# SCH_PSG4-v0_52_2026-07-15.net
KiCad netlist of a schematic drawn in EasyEDA
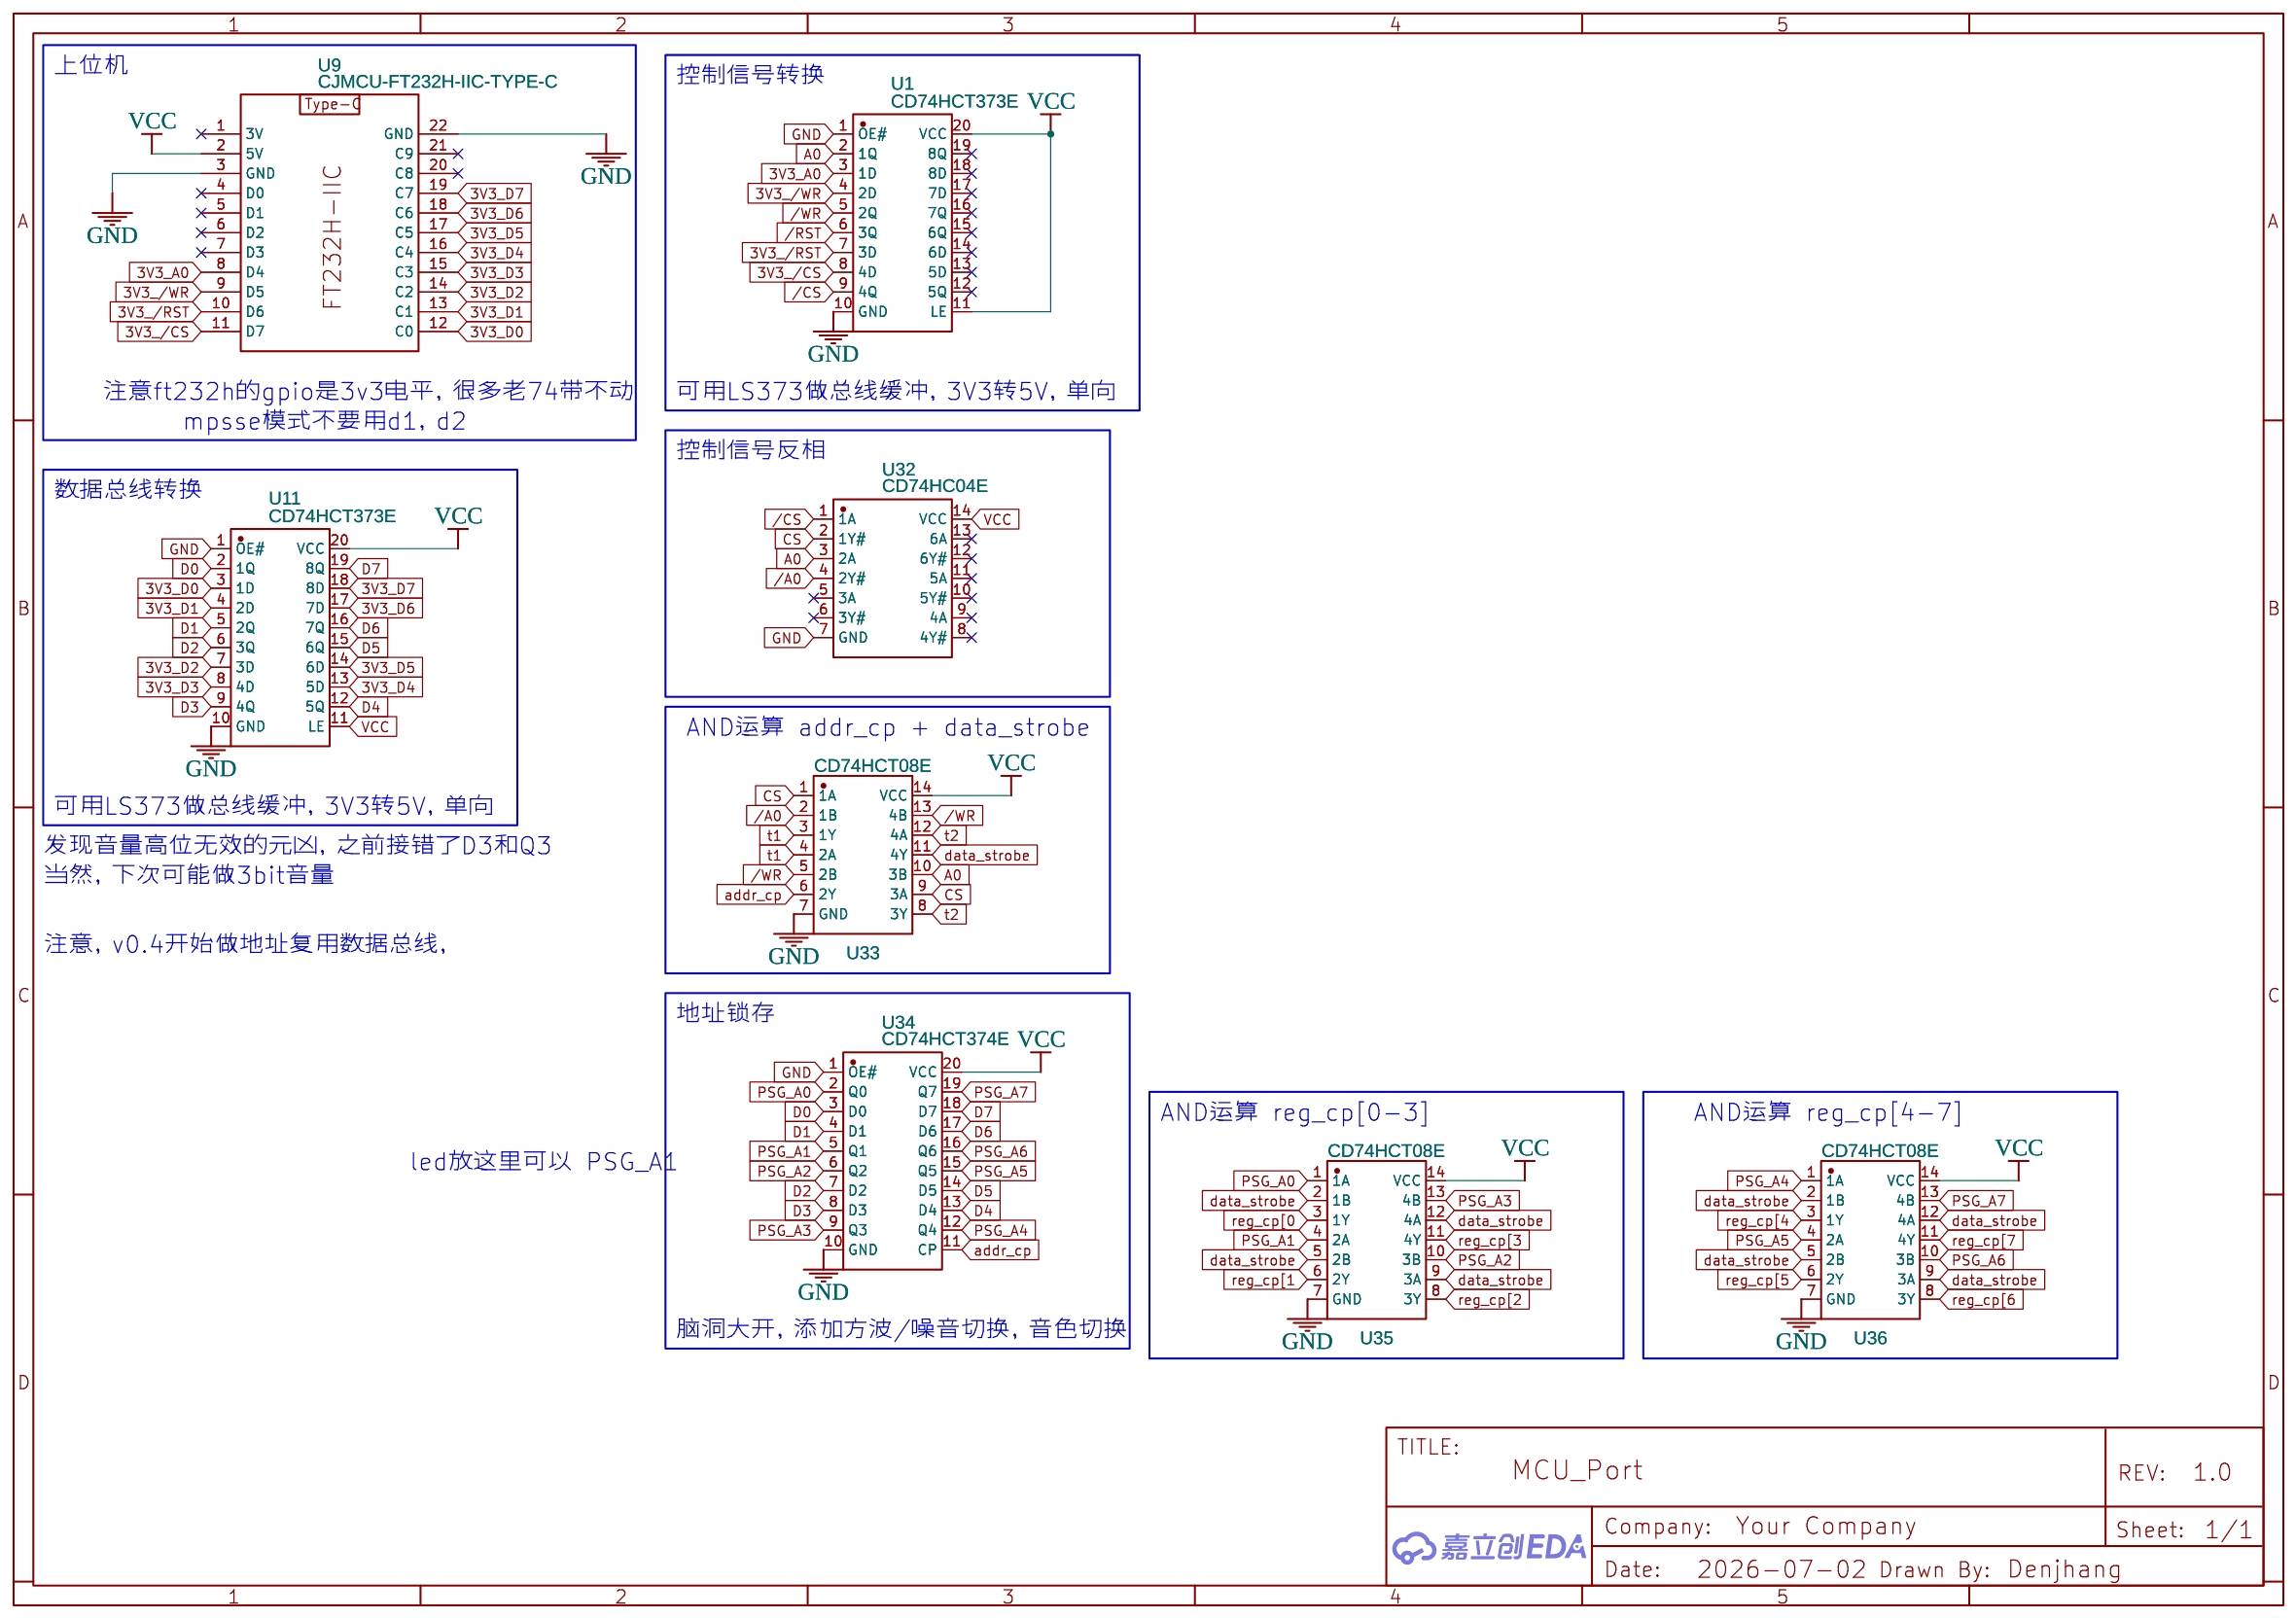
[diagram p0: MCU_Port]
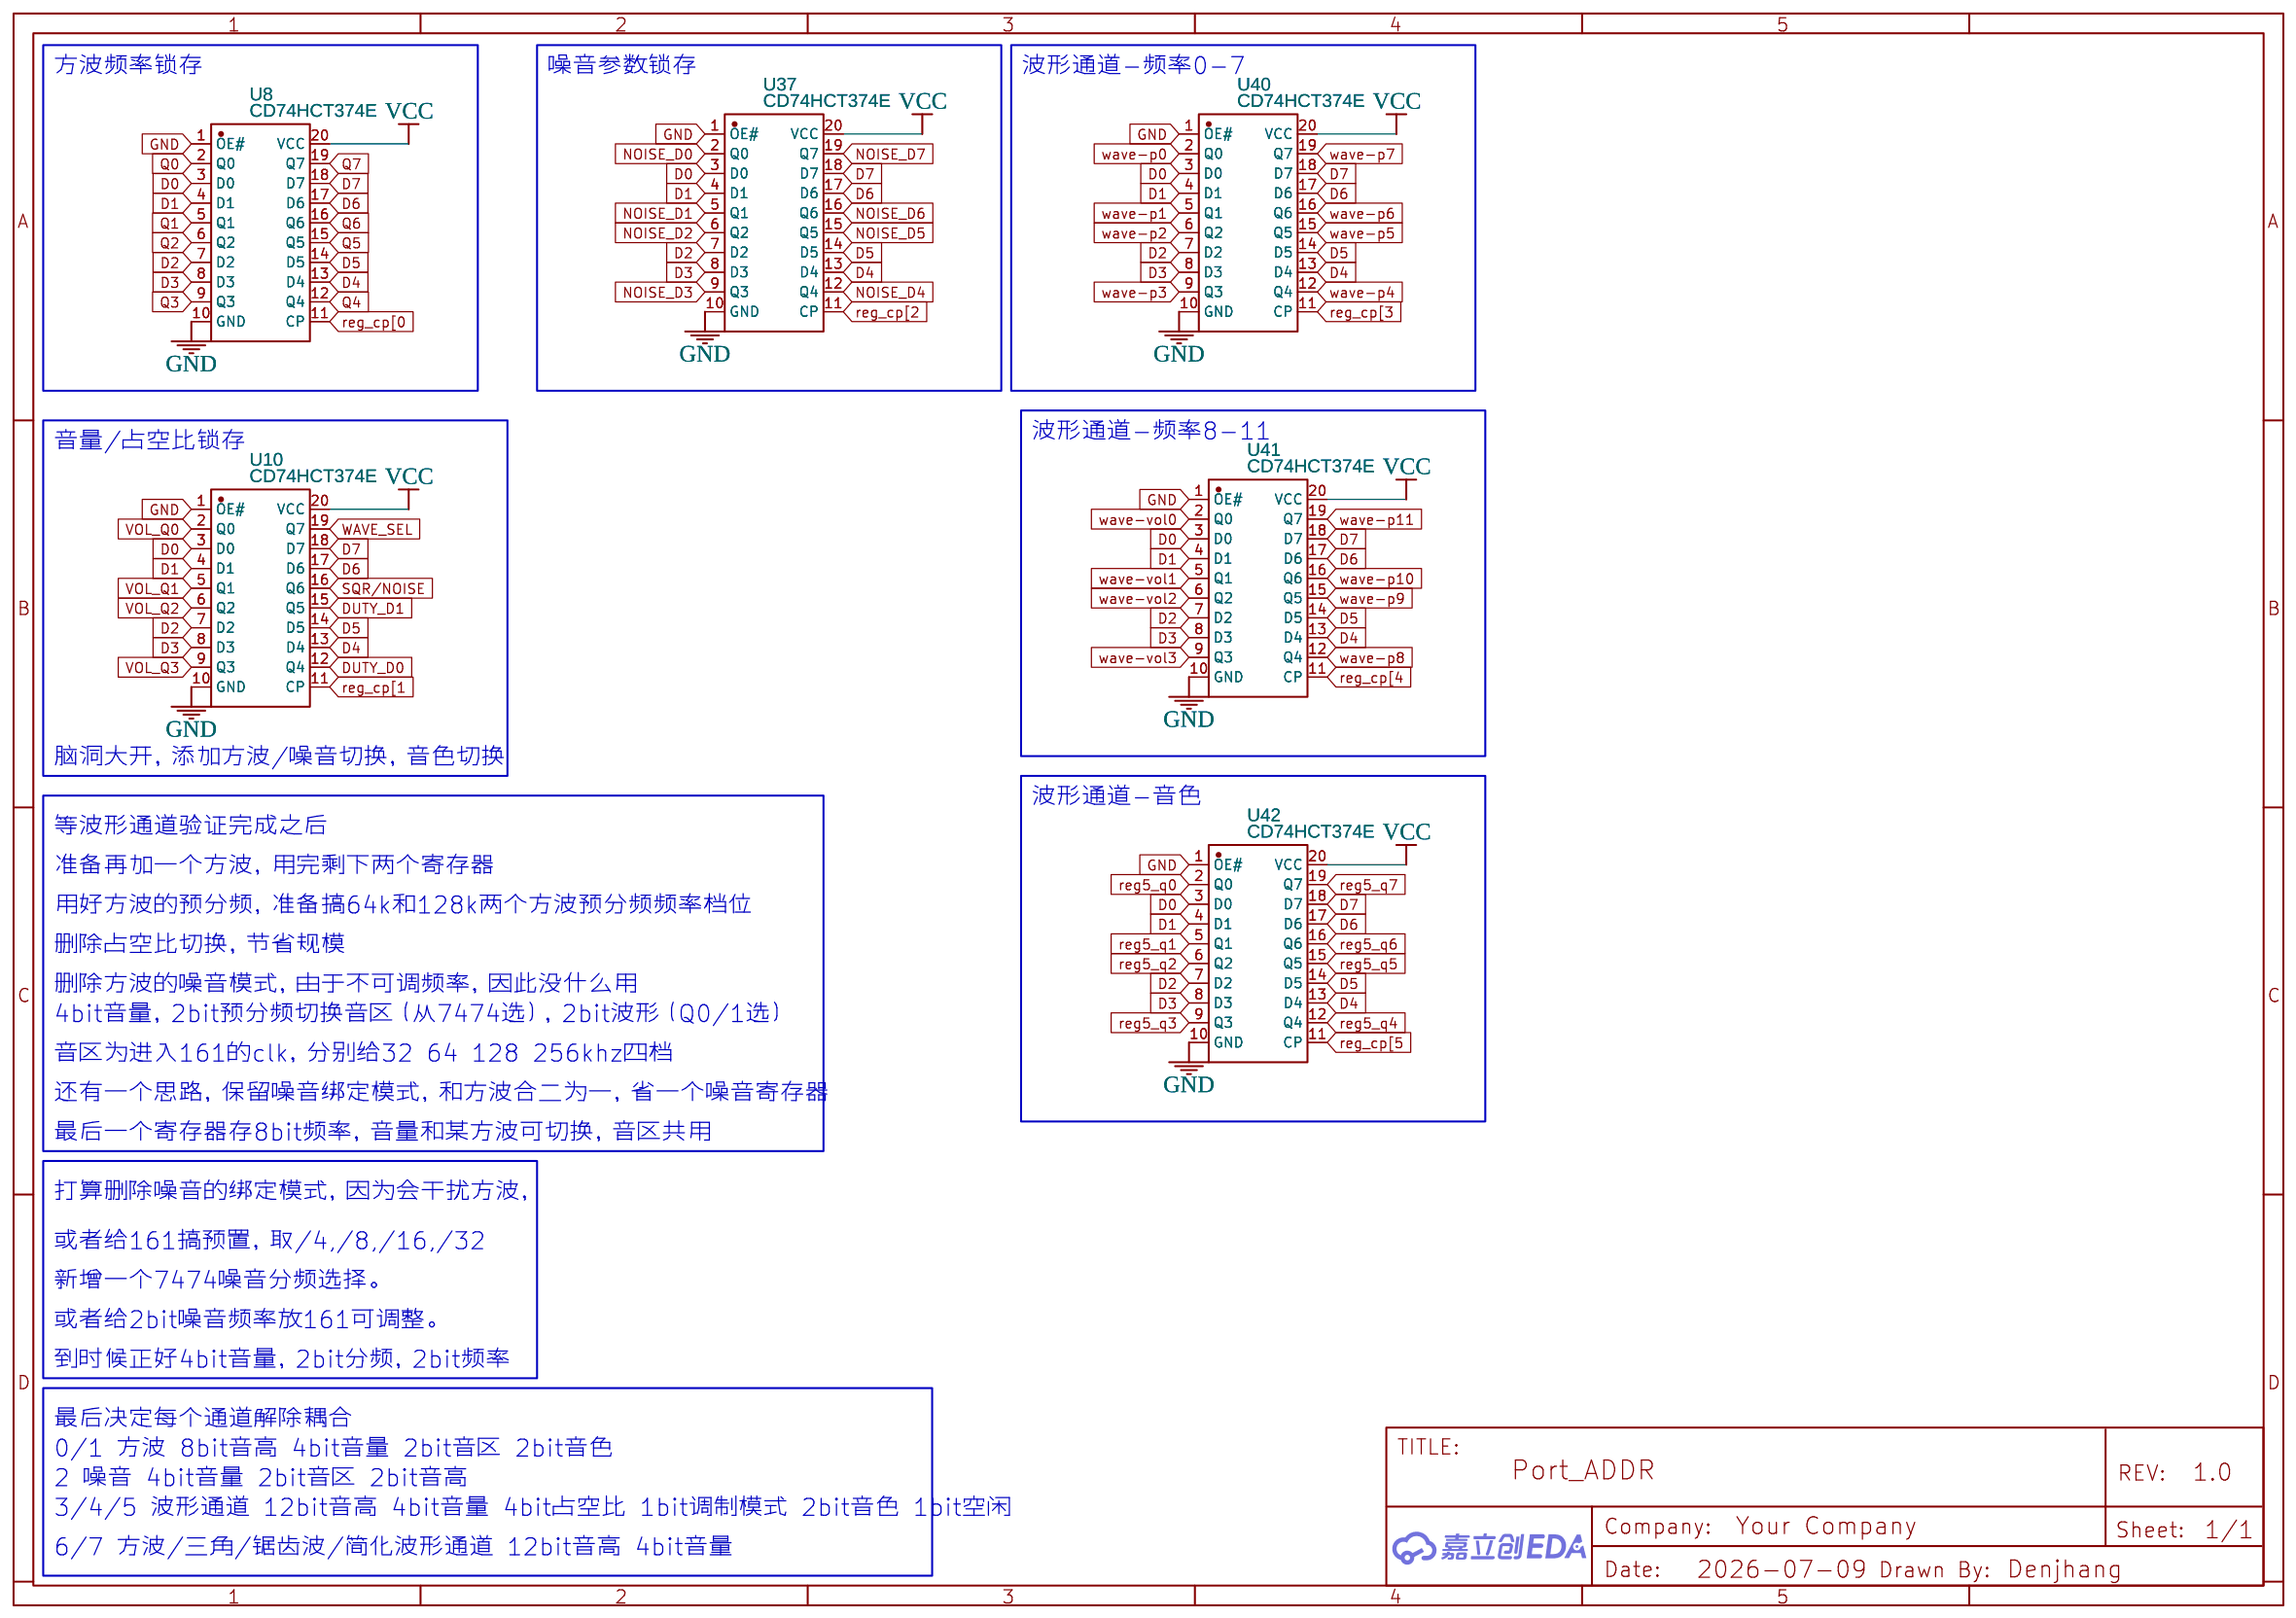
[diagram p1: Port_ADDR]
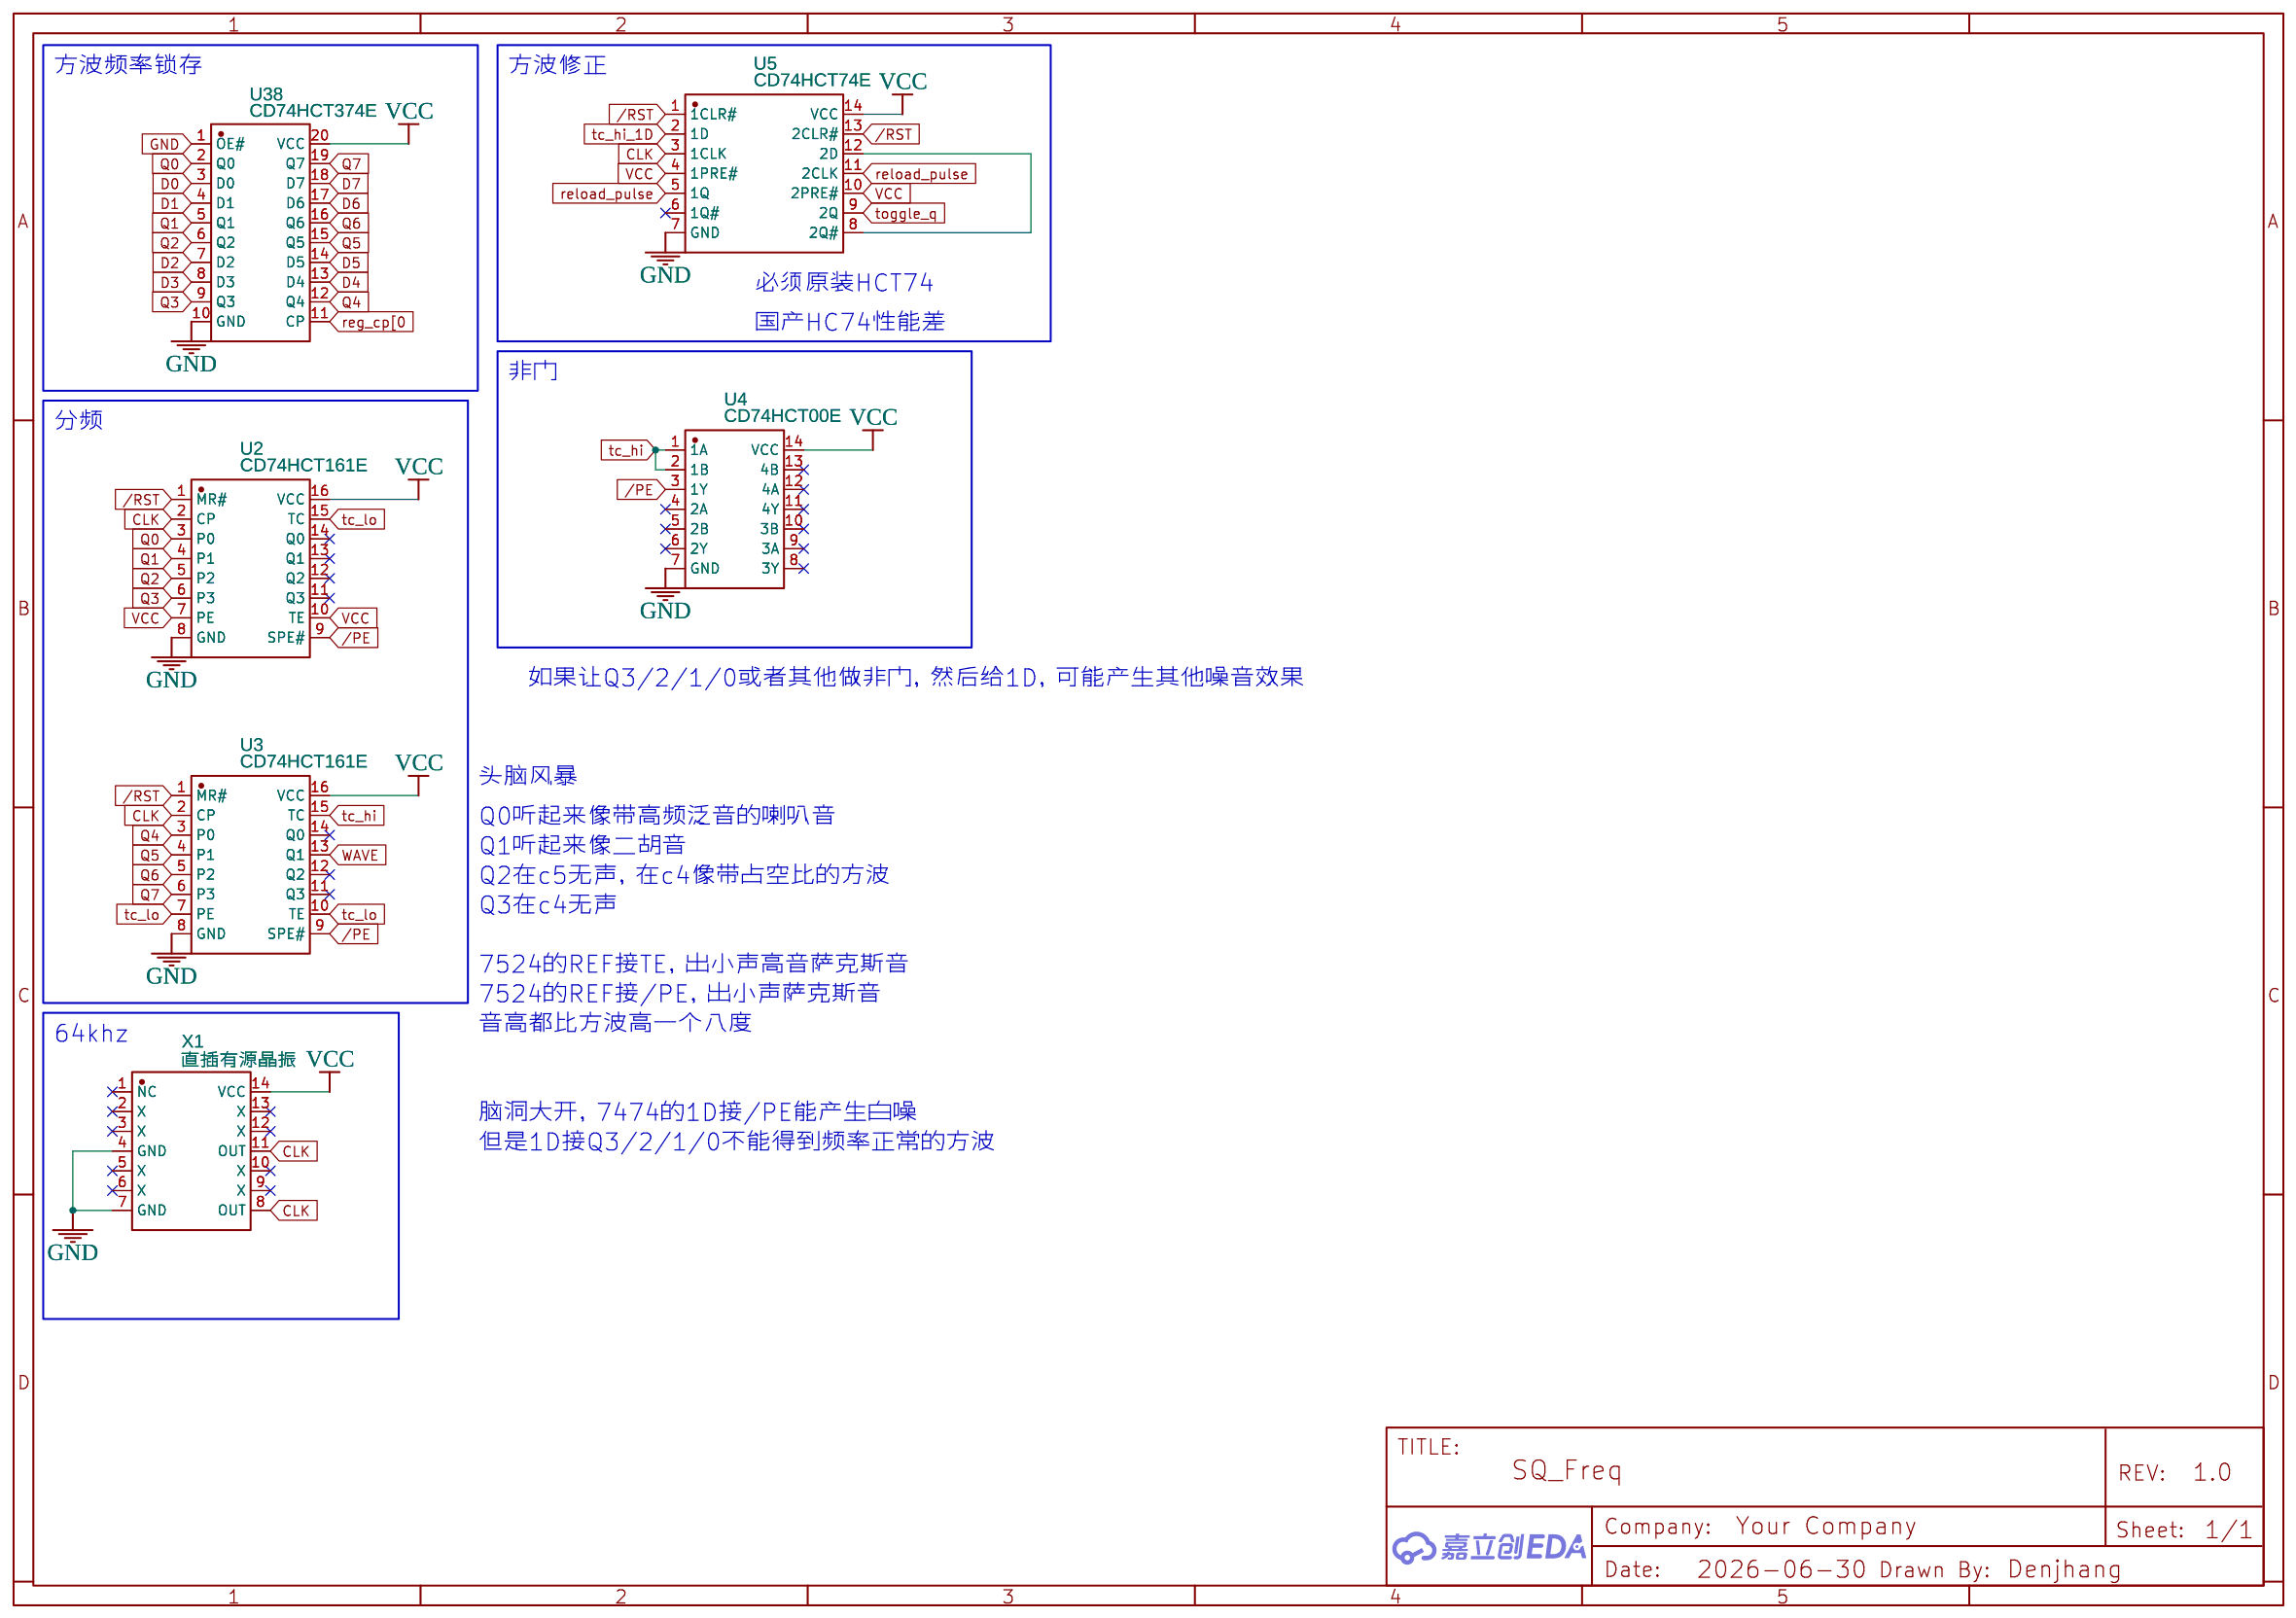
[diagram p2: SQ_Ferq]
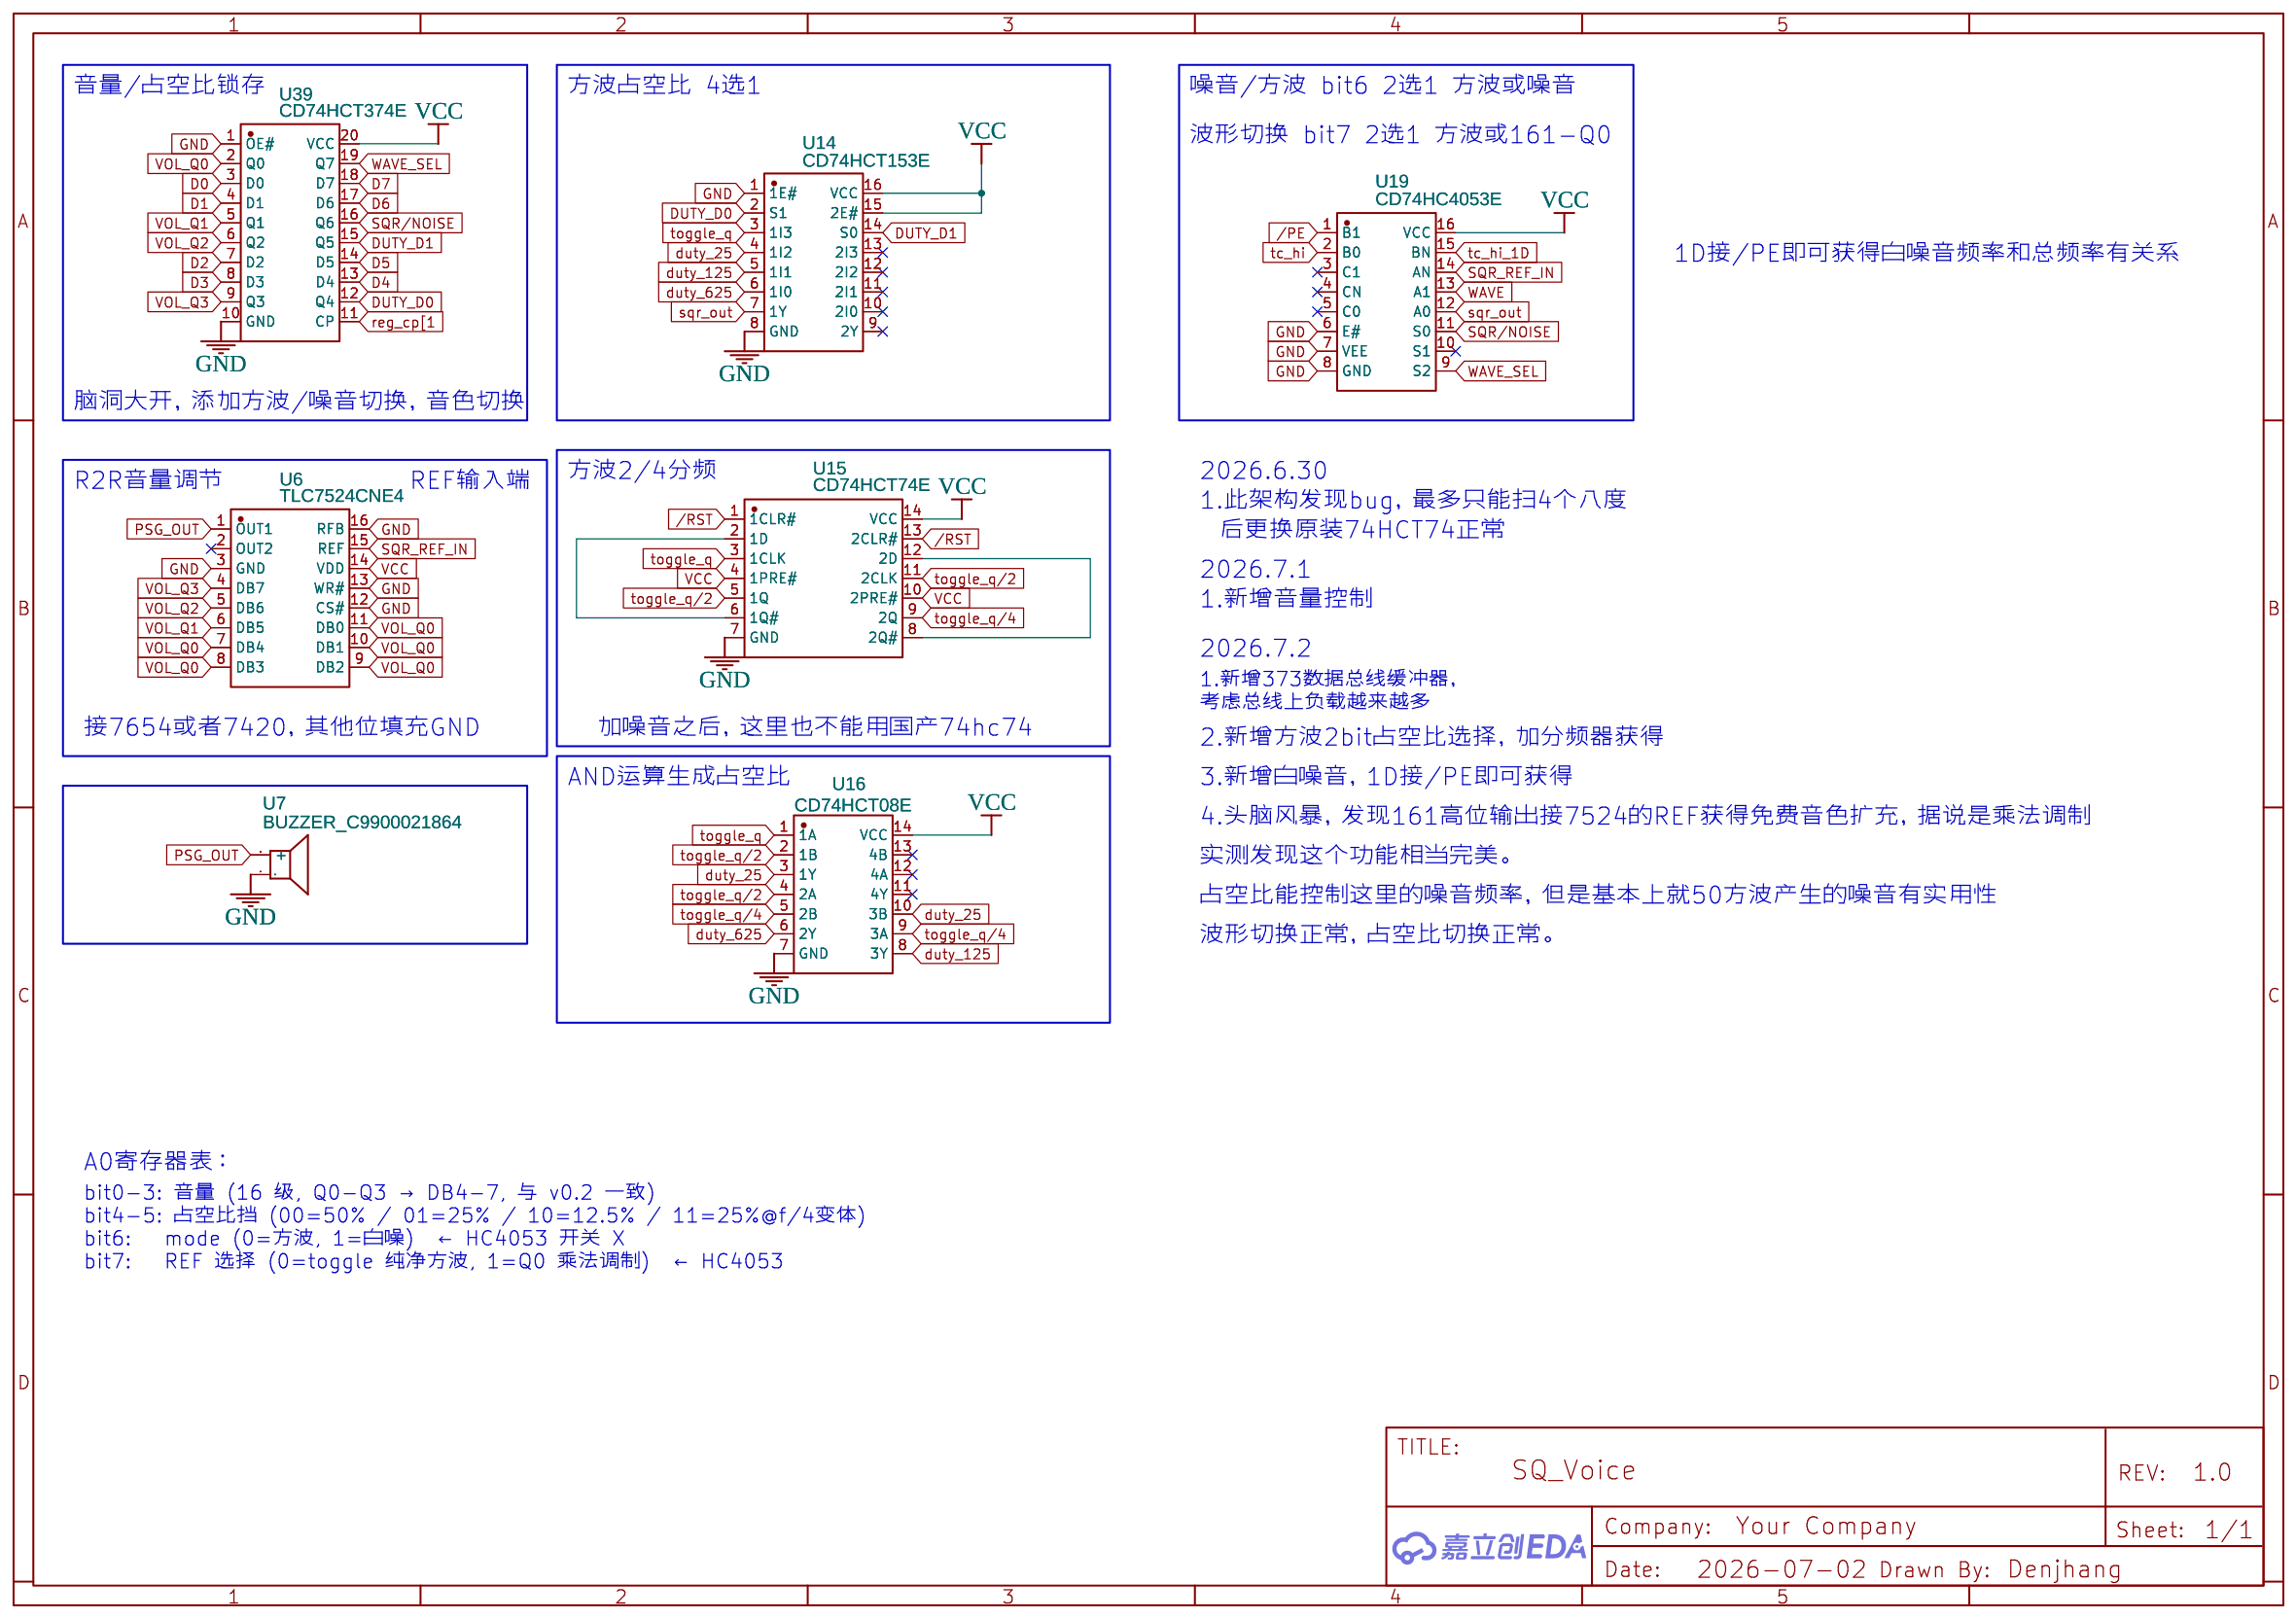
[diagram p3: SQ_Voice]
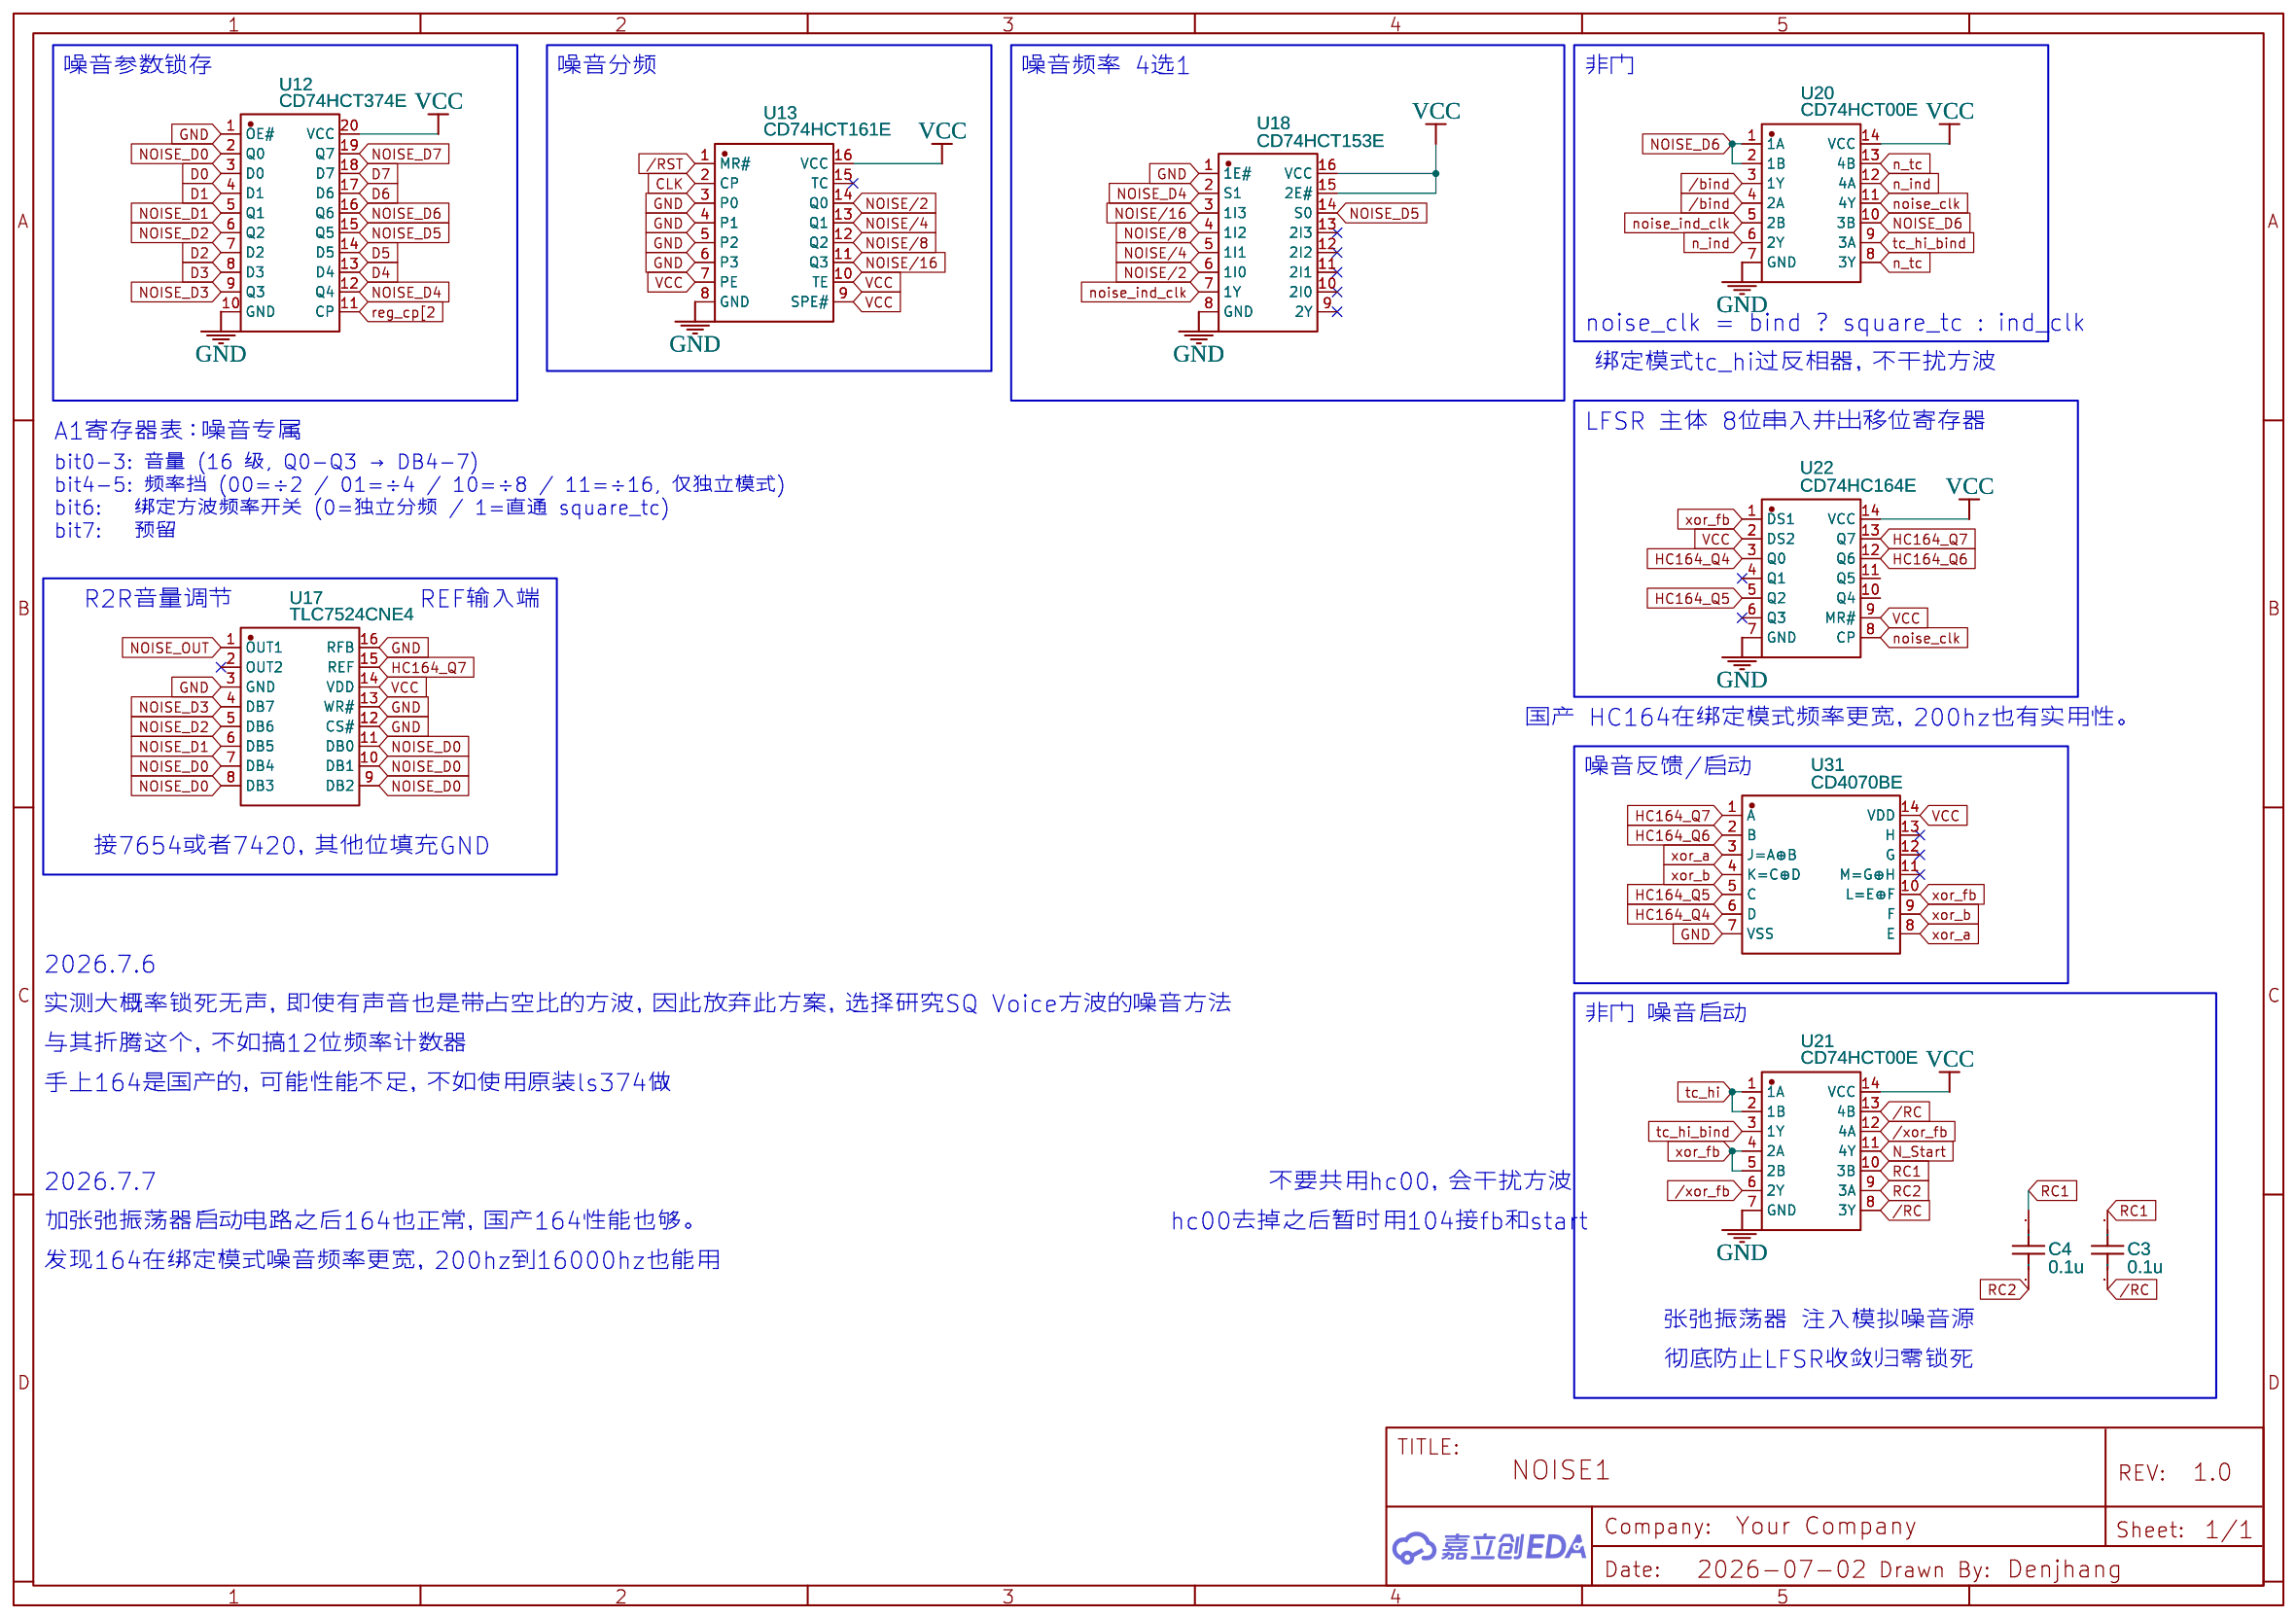
[diagram p4: Noise]
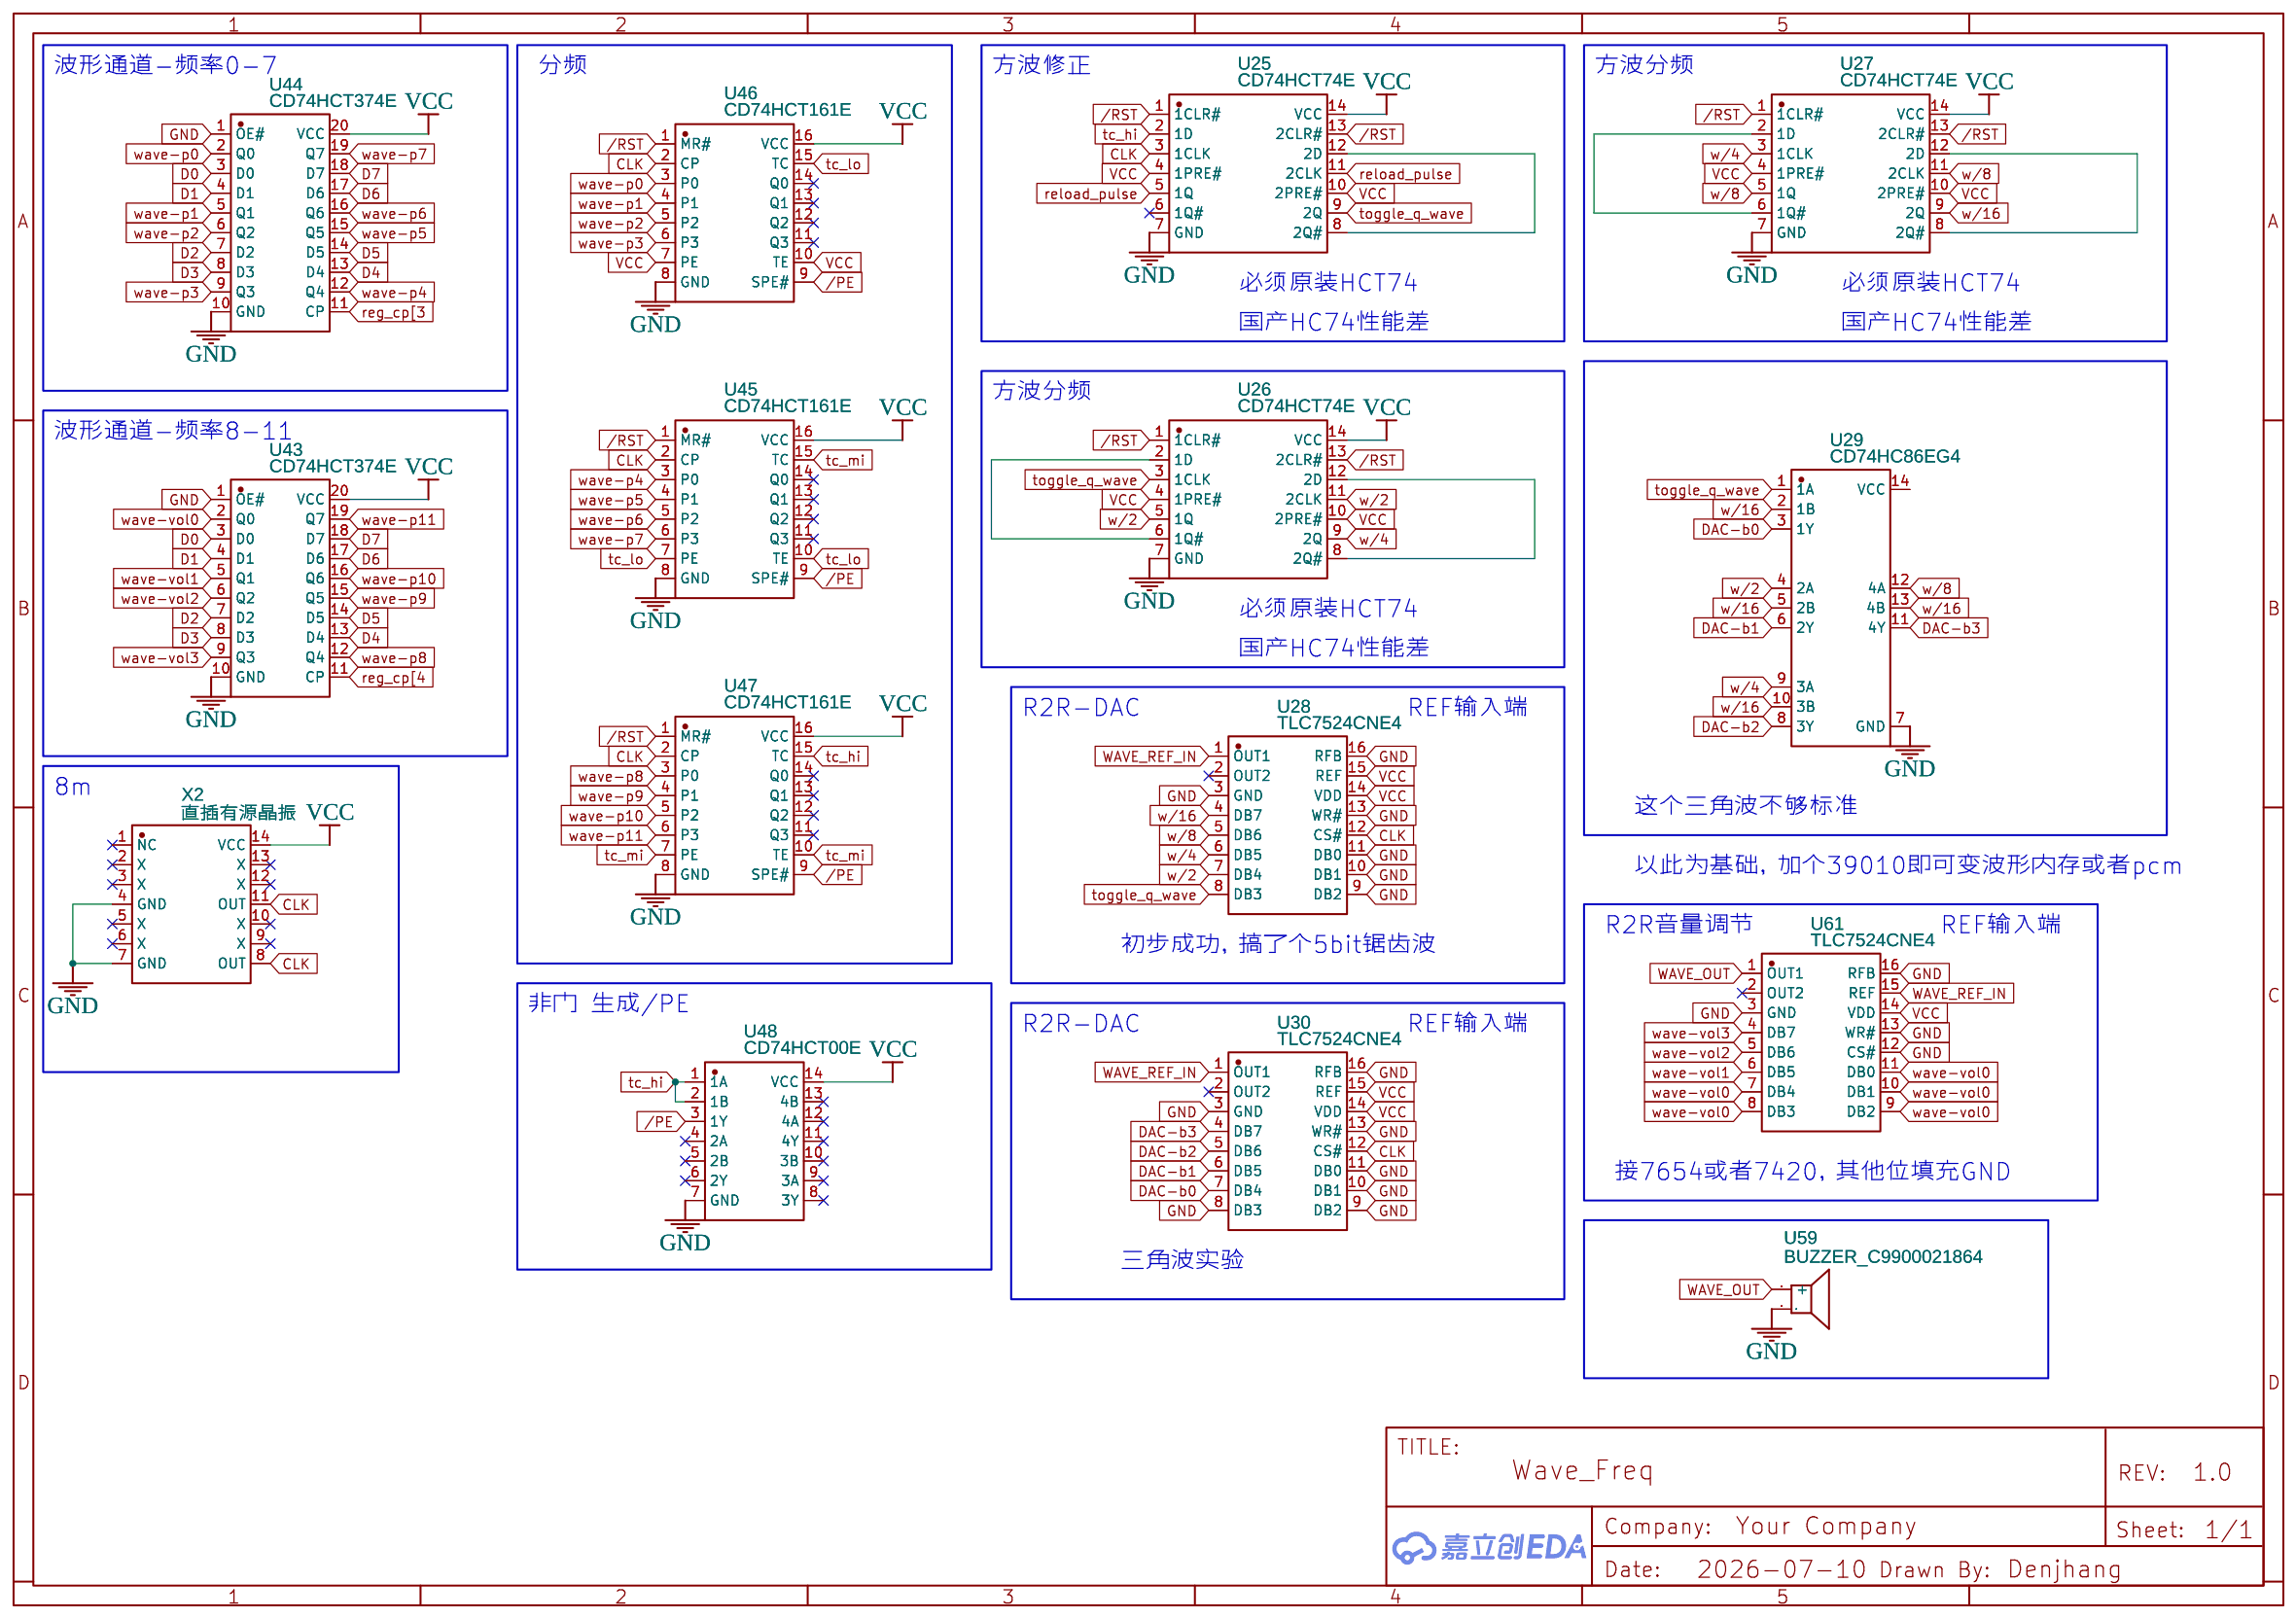
[diagram p5: Wave_Freq]
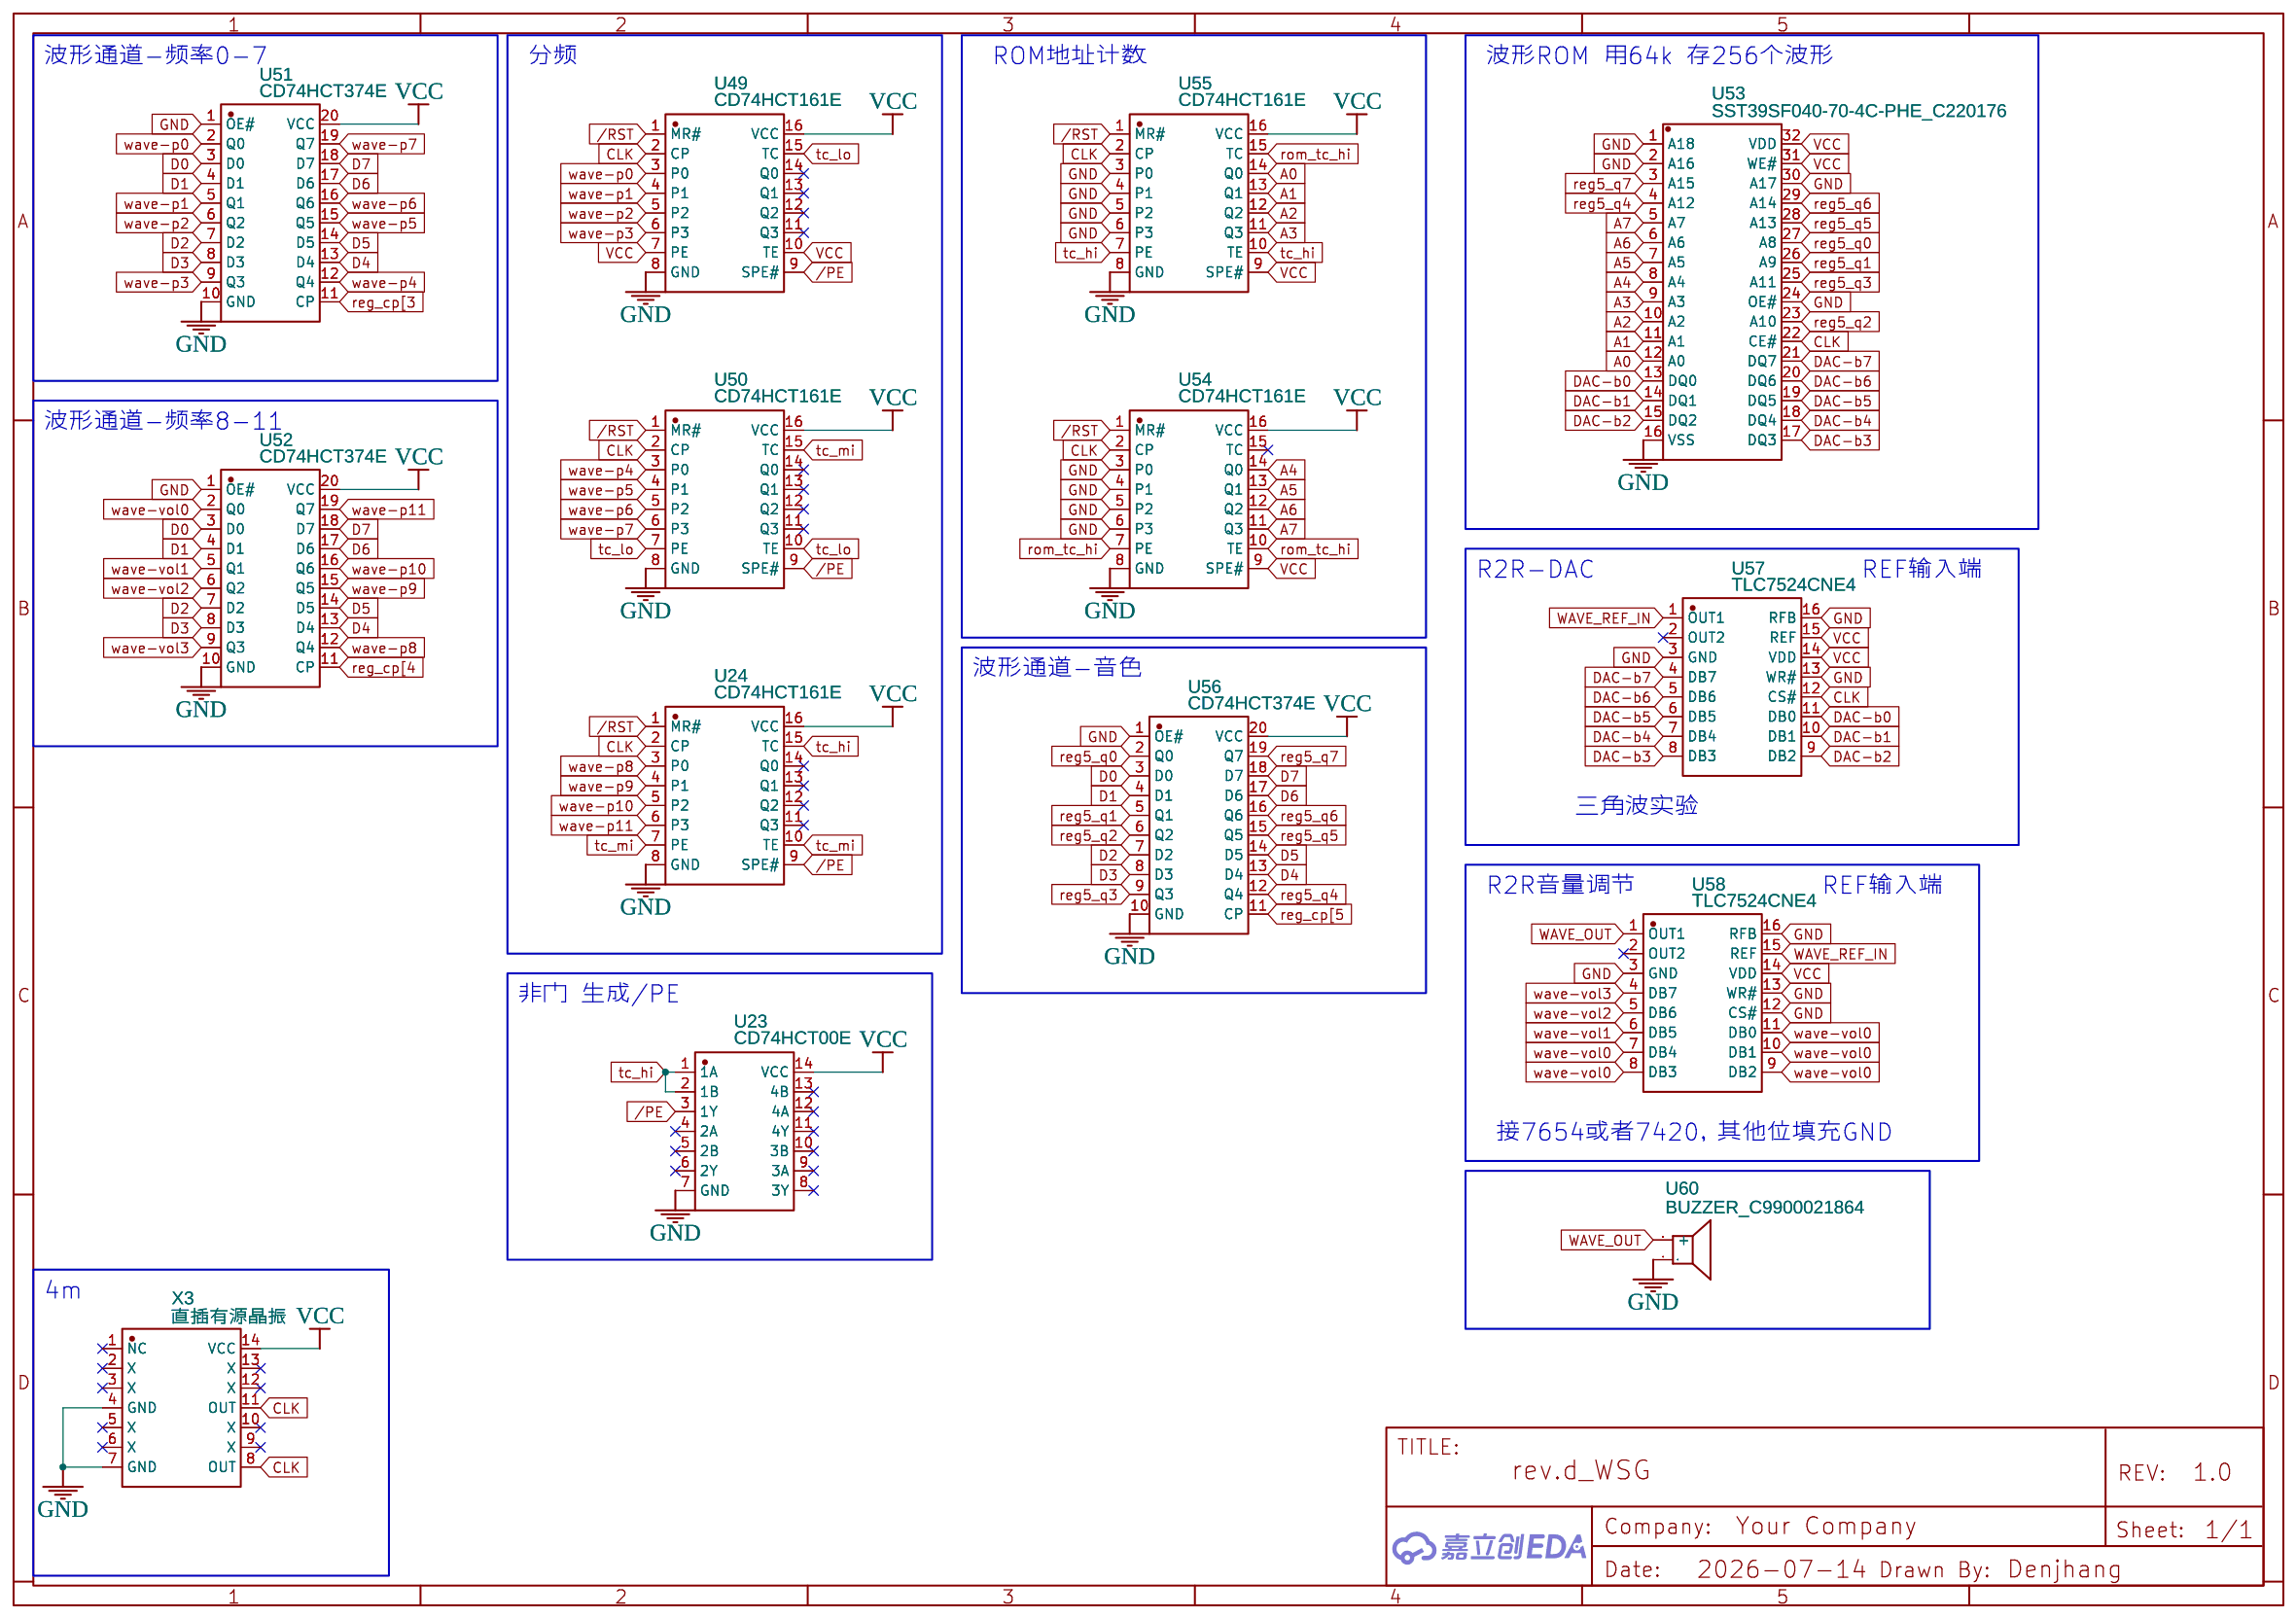
[diagram p6: rev.d_WSG]
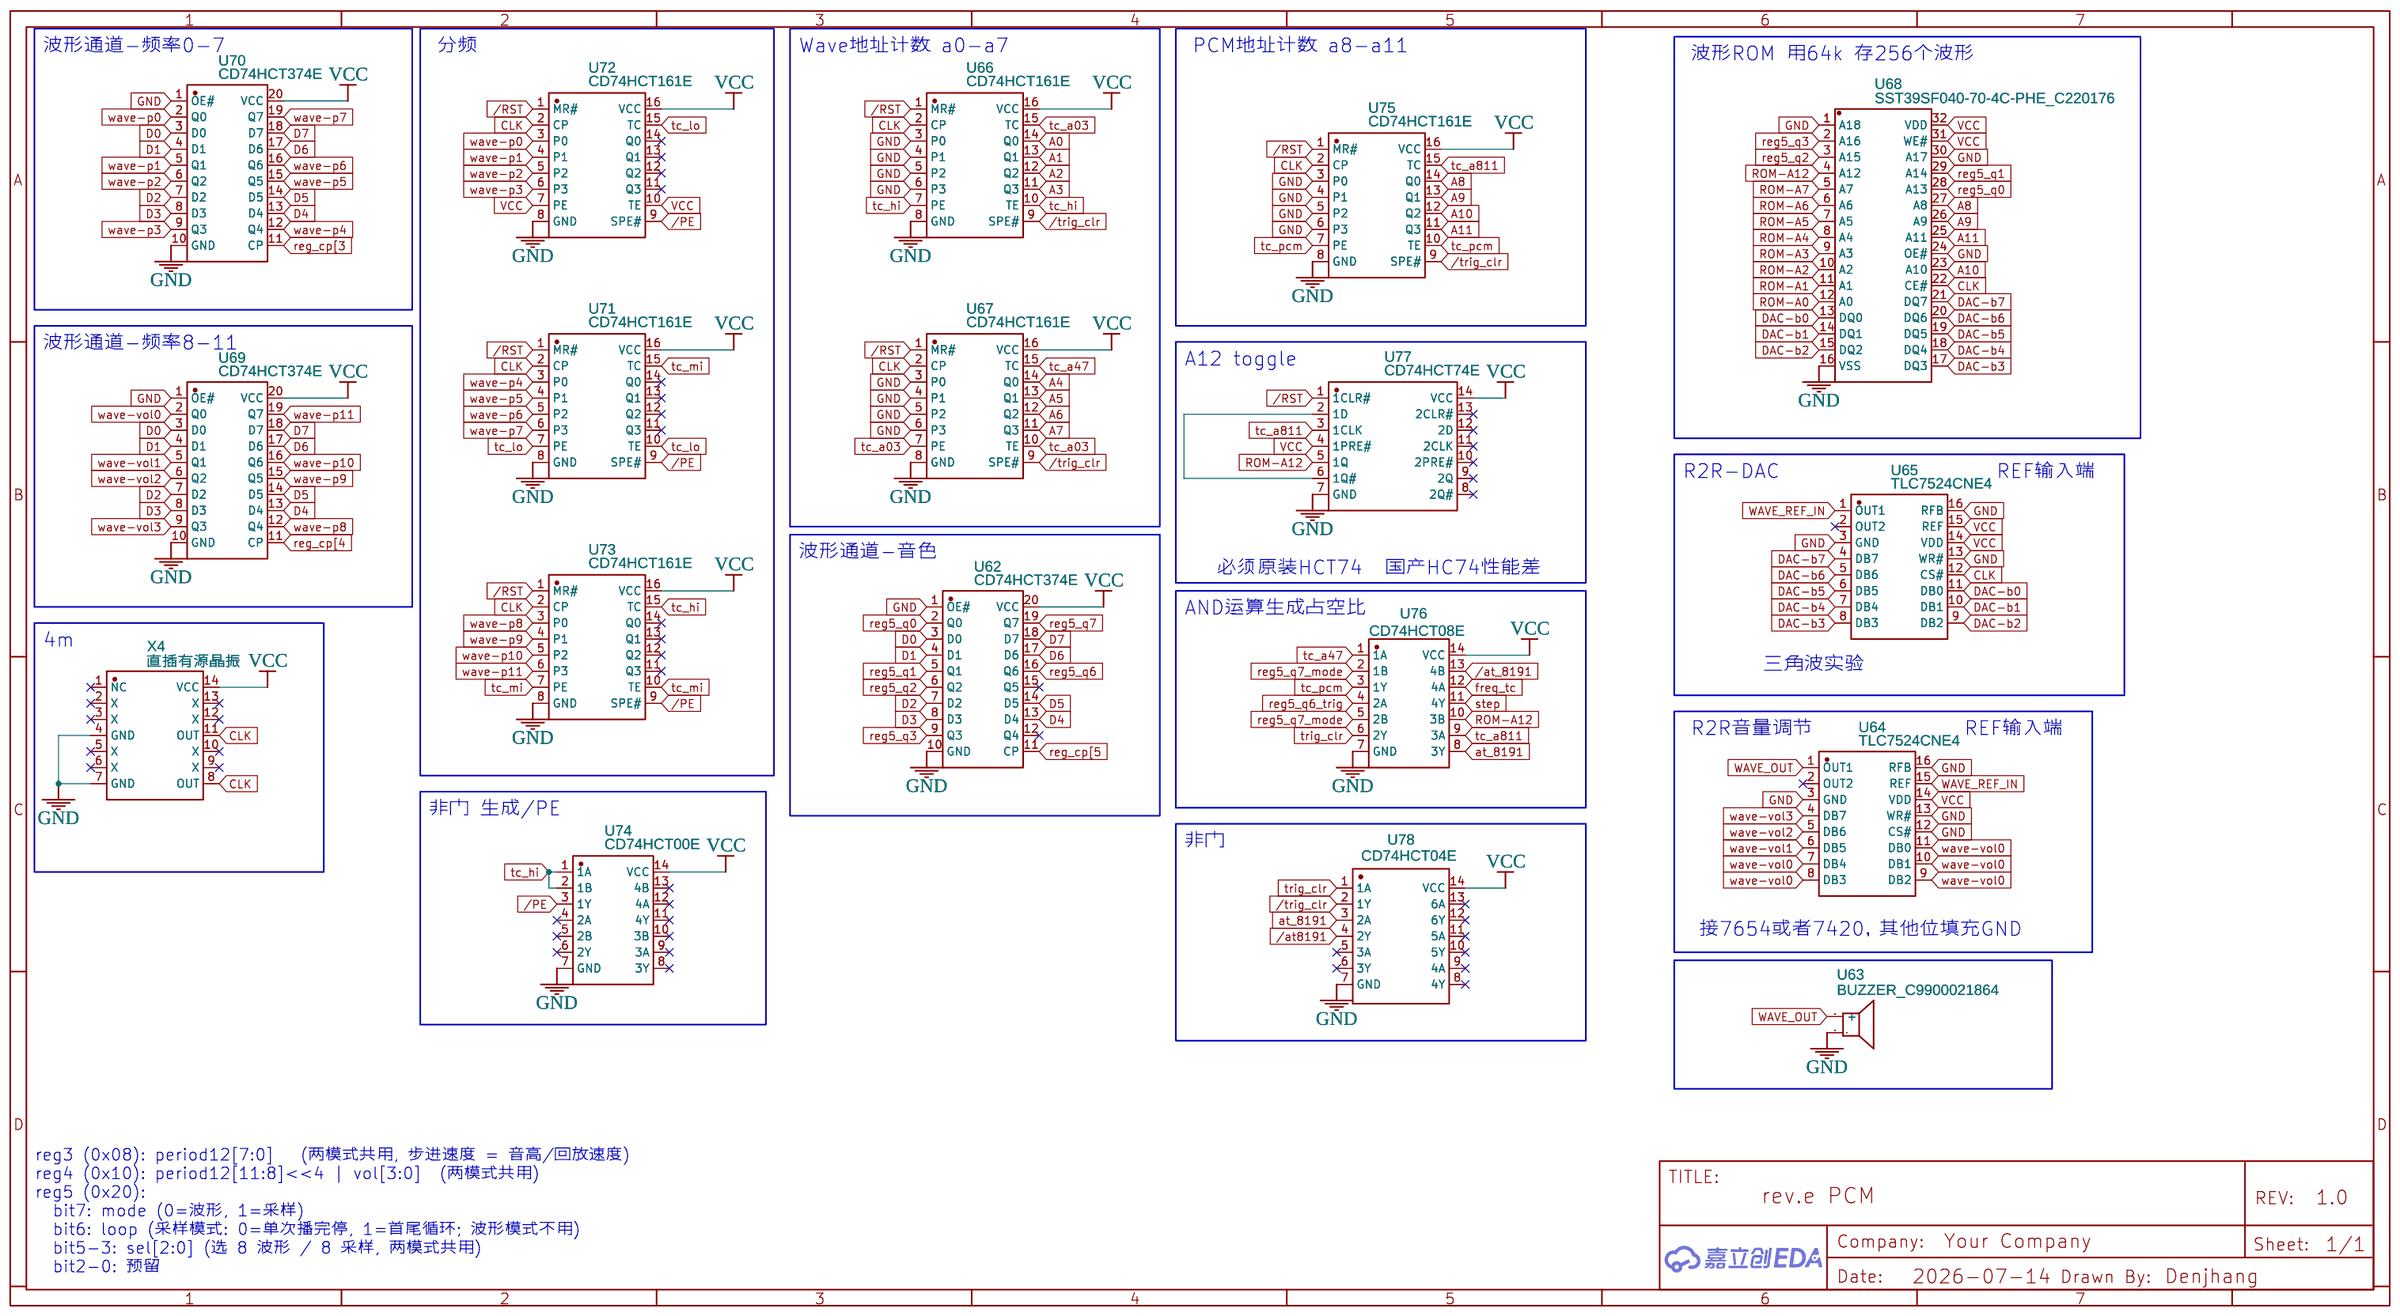
[diagram p7: rev.e PCM]

(export (version "E")
  (design (tool "Eeschema 10.0.6"))
  (components
    (comp (ref "U1")
      (value "CD74HCT373E")
      (fields (field (name "Manufacturer") "TI(德州仪器)"))
      (libsource (lib "") (part "CD74HCT373E"))
    )
    (comp (ref "U9") (value "CJMCU-FT232H-IIC-TYPE-C") (libsource (lib "") (part "CJMCU-FT232H-IIC-TYPE-C")))
    (comp (ref "U11")
      (value "CD74HCT373E")
      (fields (field (name "Manufacturer") "TI(德州仪器)"))
      (libsource (lib "") (part "CD74HCT373E"))
    )
    (comp (ref "U32")
      (value "CD74HC04E")
      (fields (field (name "Manufacturer") "TI(德州仪器)"))
      (libsource (lib "") (part "CD74HC04E"))
    )
    (comp (ref "U33")
      (value "CD74HCT08E")
      (fields (field (name "Manufacturer") "TI(德州仪器)"))
      (libsource (lib "") (part "CD74HCT08E"))
    )
    (comp (ref "U34")
      (value "CD74HCT374E")
      (fields (field (name "Manufacturer") "TI(德州仪器)"))
      (libsource (lib "") (part "CD74HCT374E"))
    )
    (comp (ref "U35")
      (value "CD74HCT08E")
      (fields (field (name "Manufacturer") "TI(德州仪器)"))
      (libsource (lib "") (part "CD74HCT08E"))
    )
    (comp (ref "U36")
      (value "CD74HCT08E")
      (fields (field (name "Manufacturer") "TI(德州仪器)"))
      (libsource (lib "") (part "CD74HCT08E"))
    )
    (comp (ref "U8")
      (value "CD74HCT374E")
      (fields (field (name "Manufacturer") "TI(德州仪器)"))
      (libsource (lib "") (part "CD74HCT374E"))
    )
    (comp (ref "U10")
      (value "CD74HCT374E")
      (fields (field (name "Manufacturer") "TI(德州仪器)"))
      (libsource (lib "") (part "CD74HCT374E"))
    )
    (comp (ref "U37")
      (value "CD74HCT374E")
      (fields (field (name "Manufacturer") "TI(德州仪器)"))
      (libsource (lib "") (part "CD74HCT374E"))
    )
    (comp (ref "U40")
      (value "CD74HCT374E")
      (fields (field (name "Manufacturer") "TI(德州仪器)"))
      (libsource (lib "") (part "CD74HCT374E"))
    )
    (comp (ref "U41")
      (value "CD74HCT374E")
      (fields (field (name "Manufacturer") "TI(德州仪器)"))
      (libsource (lib "") (part "CD74HCT374E"))
    )
    (comp (ref "U42")
      (value "CD74HCT374E")
      (fields (field (name "Manufacturer") "TI(德州仪器)"))
      (libsource (lib "") (part "CD74HCT374E"))
    )
    (comp (ref "U2")
      (value "CD74HCT161E")
      (fields (field (name "Manufacturer") "TI(德州仪器)"))
      (libsource (lib "") (part "CD74HCT161E"))
    )
    (comp (ref "U3")
      (value "CD74HCT161E")
      (fields (field (name "Manufacturer") "TI(德州仪器)"))
      (libsource (lib "") (part "CD74HCT161E"))
    )
    (comp (ref "U4")
      (value "CD74HCT00E")
      (fields (field (name "Manufacturer") "TI(德州仪器)"))
      (libsource (lib "") (part "CD74HCT00E"))
    )
    (comp (ref "U5")
      (value "CD74HCT74E")
      (fields (field (name "Manufacturer") "TI(德州仪器)"))
      (libsource (lib "") (part "CD74HCT74E"))
    )
    (comp (ref "U38")
      (value "CD74HCT374E")
      (fields (field (name "Manufacturer") "TI(德州仪器)"))
      (libsource (lib "") (part "CD74HCT374E"))
    )
    (comp (ref "X1") (value "直插有源晶振") (libsource (lib "") (part "直插有源晶振")))
    (comp (ref "U6")
      (value "TLC7524CNE4")
      (fields (field (name "Manufacturer") "TI(德州仪器)"))
      (libsource (lib "") (part "TLC7524CNE4"))
    )
    (comp (ref "U7")
      (value "BUZZER_C9900021864")
      (fields (field (name "Manufacturer Part") "BUZZER"))
      (libsource (lib "") (part "BUZZER_C9900021864"))
    )
    (comp (ref "U14")
      (value "CD74HCT153E")
      (fields (field (name "Manufacturer") "TI(德州仪器)"))
      (libsource (lib "") (part "CD74HCT153E"))
    )
    (comp (ref "U15")
      (value "CD74HCT74E")
      (fields (field (name "Manufacturer") "TI(德州仪器)"))
      (libsource (lib "") (part "CD74HCT74E"))
    )
    (comp (ref "U16")
      (value "CD74HCT08E")
      (fields (field (name "Manufacturer") "TI(德州仪器)"))
      (libsource (lib "") (part "CD74HCT08E"))
    )
    (comp (ref "U19")
      (value "CD74HC4053E")
      (fields (field (name "Manufacturer") "TI(德州仪器)"))
      (libsource (lib "") (part "CD74HC4053E"))
    )
    (comp (ref "U39")
      (value "CD74HCT374E")
      (fields (field (name "Manufacturer") "TI(德州仪器)"))
      (libsource (lib "") (part "CD74HCT374E"))
    )
    (comp (ref "C3") (value "0.1u") (libsource (lib "") (part "C_0603_US")))
    (comp (ref "C4") (value "0.1u") (libsource (lib "") (part "C_0603_US")))
    (comp (ref "U12")
      (value "CD74HCT374E")
      (fields (field (name "Manufacturer") "TI(德州仪器)"))
      (libsource (lib "") (part "CD74HCT374E"))
    )
    (comp (ref "U13")
      (value "CD74HCT161E")
      (fields (field (name "Manufacturer") "TI(德州仪器)"))
      (libsource (lib "") (part "CD74HCT161E"))
    )
    (comp (ref "U17")
      (value "TLC7524CNE4")
      (fields (field (name "Manufacturer") "TI(德州仪器)"))
      (libsource (lib "") (part "TLC7524CNE4"))
    )
    (comp (ref "U18")
      (value "CD74HCT153E")
      (fields (field (name "Manufacturer") "TI(德州仪器)"))
      (libsource (lib "") (part "CD74HCT153E"))
    )
    (comp (ref "U20")
      (value "CD74HCT00E")
      (fields (field (name "Manufacturer") "TI(德州仪器)"))
      (libsource (lib "") (part "CD74HCT00E"))
    )
    (comp (ref "U21")
      (value "CD74HCT00E")
      (fields (field (name "Manufacturer") "TI(德州仪器)"))
      (libsource (lib "") (part "CD74HCT00E"))
    )
    (comp (ref "U22")
      (value "CD74HC164E")
      (fields (field (name "Manufacturer") "TI(德州仪器)"))
      (libsource (lib "") (part "CD74HC164E"))
    )
    (comp (ref "U31")
      (value "CD4070BE")
      (fields (field (name "Manufacturer") "HGSEMI(华冠)"))
      (libsource (lib "") (part "CD4070BE"))
    )
    (comp (ref "U25")
      (value "CD74HCT74E")
      (fields (field (name "Manufacturer") "TI(德州仪器)"))
      (libsource (lib "") (part "CD74HCT74E"))
    )
    (comp (ref "U26")
      (value "CD74HCT74E")
      (fields (field (name "Manufacturer") "TI(德州仪器)"))
      (libsource (lib "") (part "CD74HCT74E"))
    )
    (comp (ref "U27")
      (value "CD74HCT74E")
      (fields (field (name "Manufacturer") "TI(德州仪器)"))
      (libsource (lib "") (part "CD74HCT74E"))
    )
    (comp (ref "U28")
      (value "TLC7524CNE4")
      (fields (field (name "Manufacturer") "TI(德州仪器)"))
      (libsource (lib "") (part "TLC7524CNE4"))
    )
    (comp (ref "U29") (value "CD74HC86EG4") (libsource (lib "") (part "CD74HC86EG4")))
    (comp (ref "U30")
      (value "TLC7524CNE4")
      (fields (field (name "Manufacturer") "TI(德州仪器)"))
      (libsource (lib "") (part "TLC7524CNE4"))
    )
    (comp (ref "U43")
      (value "CD74HCT374E")
      (fields (field (name "Manufacturer") "TI(德州仪器)"))
      (libsource (lib "") (part "CD74HCT374E"))
    )
    (comp (ref "U44")
      (value "CD74HCT374E")
      (fields (field (name "Manufacturer") "TI(德州仪器)"))
      (libsource (lib "") (part "CD74HCT374E"))
    )
    (comp (ref "U45")
      (value "CD74HCT161E")
      (fields (field (name "Manufacturer") "TI(德州仪器)"))
      (libsource (lib "") (part "CD74HCT161E"))
    )
    (comp (ref "U46")
      (value "CD74HCT161E")
      (fields (field (name "Manufacturer") "TI(德州仪器)"))
      (libsource (lib "") (part "CD74HCT161E"))
    )
    (comp (ref "U47")
      (value "CD74HCT161E")
      (fields (field (name "Manufacturer") "TI(德州仪器)"))
      (libsource (lib "") (part "CD74HCT161E"))
    )
    (comp (ref "U48")
      (value "CD74HCT00E")
      (fields (field (name "Manufacturer") "TI(德州仪器)"))
      (libsource (lib "") (part "CD74HCT00E"))
    )
    (comp (ref "U59")
      (value "BUZZER_C9900021864")
      (fields (field (name "Manufacturer Part") "BUZZER"))
      (libsource (lib "") (part "BUZZER_C9900021864"))
    )
    (comp (ref "U61")
      (value "TLC7524CNE4")
      (fields (field (name "Manufacturer") "TI(德州仪器)"))
      (libsource (lib "") (part "TLC7524CNE4"))
    )
    (comp (ref "X2") (value "直插有源晶振") (libsource (lib "") (part "直插有源晶振")))
    (comp (ref "U23")
      (value "CD74HCT00E")
      (fields (field (name "Manufacturer") "TI(德州仪器)"))
      (libsource (lib "") (part "CD74HCT00E"))
    )
    (comp (ref "U24")
      (value "CD74HCT161E")
      (fields (field (name "Manufacturer") "TI(德州仪器)"))
      (libsource (lib "") (part "CD74HCT161E"))
    )
    (comp (ref "U49")
      (value "CD74HCT161E")
      (fields (field (name "Manufacturer") "TI(德州仪器)"))
      (libsource (lib "") (part "CD74HCT161E"))
    )
    (comp (ref "U50")
      (value "CD74HCT161E")
      (fields (field (name "Manufacturer") "TI(德州仪器)"))
      (libsource (lib "") (part "CD74HCT161E"))
    )
    (comp (ref "U51")
      (value "CD74HCT374E")
      (fields (field (name "Manufacturer") "TI(德州仪器)"))
      (libsource (lib "") (part "CD74HCT374E"))
    )
    (comp (ref "U52")
      (value "CD74HCT374E")
      (fields (field (name "Manufacturer") "TI(德州仪器)"))
      (libsource (lib "") (part "CD74HCT374E"))
    )
    (comp (ref "U53")
      (value "SST39SF040-70-4C-PHE_C220176")
      (fields
        (field (name "Manufacturer Part") "SST39SF040-70-4C-PHE")
        (field (name "Manufacturer") "MICROCHIP(美国微芯)")
      )
      (libsource (lib "") (part "SST39SF040-70-4C-PHE_C220176"))
    )
    (comp (ref "U54")
      (value "CD74HCT161E")
      (fields (field (name "Manufacturer") "TI(德州仪器)"))
      (libsource (lib "") (part "CD74HCT161E"))
    )
    (comp (ref "U55")
      (value "CD74HCT161E")
      (fields (field (name "Manufacturer") "TI(德州仪器)"))
      (libsource (lib "") (part "CD74HCT161E"))
    )
    (comp (ref "U56")
      (value "CD74HCT374E")
      (fields (field (name "Manufacturer") "TI(德州仪器)"))
      (libsource (lib "") (part "CD74HCT374E"))
    )
    (comp (ref "U57")
      (value "TLC7524CNE4")
      (fields (field (name "Manufacturer") "TI(德州仪器)"))
      (libsource (lib "") (part "TLC7524CNE4"))
    )
    (comp (ref "U58")
      (value "TLC7524CNE4")
      (fields (field (name "Manufacturer") "TI(德州仪器)"))
      (libsource (lib "") (part "TLC7524CNE4"))
    )
    (comp (ref "U60")
      (value "BUZZER_C9900021864")
      (fields (field (name "Manufacturer Part") "BUZZER"))
      (libsource (lib "") (part "BUZZER_C9900021864"))
    )
    (comp (ref "X3") (value "直插有源晶振") (libsource (lib "") (part "直插有源晶振")))
    (comp (ref "U62")
      (value "CD74HCT374E")
      (fields (field (name "Manufacturer") "TI(德州仪器)"))
      (libsource (lib "") (part "CD74HCT374E"))
    )
    (comp (ref "U63")
      (value "BUZZER_C9900021864")
      (fields (field (name "Manufacturer Part") "BUZZER"))
      (libsource (lib "") (part "BUZZER_C9900021864"))
    )
    (comp (ref "U64")
      (value "TLC7524CNE4")
      (fields (field (name "Manufacturer") "TI(德州仪器)"))
      (libsource (lib "") (part "TLC7524CNE4"))
    )
    (comp (ref "U65")
      (value "TLC7524CNE4")
      (fields (field (name "Manufacturer") "TI(德州仪器)"))
      (libsource (lib "") (part "TLC7524CNE4"))
    )
    (comp (ref "U66")
      (value "CD74HCT161E")
      (fields (field (name "Manufacturer") "TI(德州仪器)"))
      (libsource (lib "") (part "CD74HCT161E"))
    )
    (comp (ref "U67")
      (value "CD74HCT161E")
      (fields (field (name "Manufacturer") "TI(德州仪器)"))
      (libsource (lib "") (part "CD74HCT161E"))
    )
    (comp (ref "U68")
      (value "SST39SF040-70-4C-PHE_C220176")
      (fields
        (field (name "Manufacturer Part") "SST39SF040-70-4C-PHE")
        (field (name "Manufacturer") "MICROCHIP(美国微芯)")
      )
      (libsource (lib "") (part "SST39SF040-70-4C-PHE_C220176"))
    )
    (comp (ref "U69")
      (value "CD74HCT374E")
      (fields (field (name "Manufacturer") "TI(德州仪器)"))
      (libsource (lib "") (part "CD74HCT374E"))
    )
    (comp (ref "U70")
      (value "CD74HCT374E")
      (fields (field (name "Manufacturer") "TI(德州仪器)"))
      (libsource (lib "") (part "CD74HCT374E"))
    )
    (comp (ref "U71")
      (value "CD74HCT161E")
      (fields (field (name "Manufacturer") "TI(德州仪器)"))
      (libsource (lib "") (part "CD74HCT161E"))
    )
    (comp (ref "U72")
      (value "CD74HCT161E")
      (fields (field (name "Manufacturer") "TI(德州仪器)"))
      (libsource (lib "") (part "CD74HCT161E"))
    )
    (comp (ref "U73")
      (value "CD74HCT161E")
      (fields (field (name "Manufacturer") "TI(德州仪器)"))
      (libsource (lib "") (part "CD74HCT161E"))
    )
    (comp (ref "U74")
      (value "CD74HCT00E")
      (fields (field (name "Manufacturer") "TI(德州仪器)"))
      (libsource (lib "") (part "CD74HCT00E"))
    )
    (comp (ref "U75")
      (value "CD74HCT161E")
      (fields (field (name "Manufacturer") "TI(德州仪器)"))
      (libsource (lib "") (part "CD74HCT161E"))
    )
    (comp (ref "U76")
      (value "CD74HCT08E")
      (fields (field (name "Manufacturer") "TI(德州仪器)"))
      (libsource (lib "") (part "CD74HCT08E"))
    )
    (comp (ref "U77")
      (value "CD74HCT74E")
      (fields (field (name "Manufacturer") "TI(德州仪器)"))
      (libsource (lib "") (part "CD74HCT74E"))
    )
    (comp (ref "U78") (value "CD74HCT04E") (libsource (lib "") (part "CD74HCT04E")))
    (comp (ref "X4") (value "直插有源晶振") (libsource (lib "") (part "直插有源晶振")))
  )
  (nets
    (net (code "1") (name "3V3_A0") (class "Default")
      (node (ref "U1") (pin "3") (pinfunction "1D_3") (pintype "unspecified"))
      (node (ref "U9") (pin "8") (pinfunction "D4_8") (pintype "unspecified"))
    )
    (net (code "2") (name "3V3_D0") (class "Default")
      (node (ref "U11") (pin "3") (pinfunction "1D_3") (pintype "unspecified"))
      (node (ref "U9") (pin "12") (pinfunction "C0_12") (pintype "unspecified"))
    )
    (net (code "3") (name "3V3_D1") (class "Default")
      (node (ref "U11") (pin "4") (pinfunction "2D_4") (pintype "unspecified"))
      (node (ref "U9") (pin "13") (pinfunction "C1_13") (pintype "unspecified"))
    )
    (net (code "4") (name "3V3_D2") (class "Default")
      (node (ref "U11") (pin "7") (pinfunction "3D_7") (pintype "unspecified"))
      (node (ref "U9") (pin "14") (pinfunction "C2_14") (pintype "unspecified"))
    )
    (net (code "5") (name "3V3_D3") (class "Default")
      (node (ref "U11") (pin "8") (pinfunction "4D_8") (pintype "unspecified"))
      (node (ref "U9") (pin "15") (pinfunction "C3_15") (pintype "unspecified"))
    )
    (net (code "6") (name "3V3_D4") (class "Default")
      (node (ref "U11") (pin "13") (pinfunction "5D_13") (pintype "unspecified"))
      (node (ref "U9") (pin "16") (pinfunction "C4_16") (pintype "unspecified"))
    )
    (net (code "7") (name "3V3_D5") (class "Default")
      (node (ref "U11") (pin "14") (pinfunction "6D_14") (pintype "unspecified"))
      (node (ref "U9") (pin "17") (pinfunction "C5_17") (pintype "unspecified"))
    )
    (net (code "8") (name "3V3_D6") (class "Default")
      (node (ref "U11") (pin "17") (pinfunction "7D_17") (pintype "unspecified"))
      (node (ref "U9") (pin "18") (pinfunction "C6_18") (pintype "unspecified"))
    )
    (net (code "9") (name "3V3_D7") (class "Default")
      (node (ref "U11") (pin "18") (pinfunction "8D_18") (pintype "unspecified"))
      (node (ref "U9") (pin "19") (pinfunction "C7_19") (pintype "unspecified"))
    )
    (net (code "10") (name "3V3_{slash}CS") (class "Default")
      (node (ref "U1") (pin "8") (pinfunction "4D_8") (pintype "unspecified"))
      (node (ref "U9") (pin "11") (pinfunction "D7_11") (pintype "unspecified"))
    )
    (net (code "11") (name "3V3_{slash}RST") (class "Default")
      (node (ref "U1") (pin "7") (pinfunction "3D_7") (pintype "unspecified"))
      (node (ref "U9") (pin "10") (pinfunction "D6_10") (pintype "unspecified"))
    )
    (net (code "12") (name "3V3_{slash}WR") (class "Default")
      (node (ref "U1") (pin "4") (pinfunction "2D_4") (pintype "unspecified"))
      (node (ref "U9") (pin "9") (pinfunction "D5_9") (pintype "unspecified"))
    )
    (net (code "13") (name "A0") (class "Default")
      (node (ref "U1") (pin "2") (pinfunction "1Q_2") (pintype "unspecified"))
      (node (ref "U32") (pin "3") (pinfunction "2A_3") (pintype "unspecified"))
      (node (ref "U33") (pin "10") (pinfunction "3B_10") (pintype "unspecified"))
      (node (ref "U53") (pin "12") (pinfunction "A0_12") (pintype "unspecified"))
      (node (ref "U55") (pin "14") (pinfunction "Q0_14") (pintype "unspecified"))
      (node (ref "U66") (pin "14") (pinfunction "Q0_14") (pintype "unspecified"))
    )
    (net (code "14") (name "A1") (class "Default")
      (node (ref "U53") (pin "11") (pinfunction "A1_11") (pintype "unspecified"))
      (node (ref "U55") (pin "13") (pinfunction "Q1_13") (pintype "unspecified"))
      (node (ref "U66") (pin "13") (pinfunction "Q1_13") (pintype "unspecified"))
    )
    (net (code "15") (name "A2") (class "Default")
      (node (ref "U53") (pin "10") (pinfunction "A2_10") (pintype "unspecified"))
      (node (ref "U55") (pin "12") (pinfunction "Q2_12") (pintype "unspecified"))
      (node (ref "U66") (pin "12") (pinfunction "Q2_12") (pintype "unspecified"))
    )
    (net (code "16") (name "A3") (class "Default")
      (node (ref "U53") (pin "9") (pinfunction "A3_9") (pintype "unspecified"))
      (node (ref "U55") (pin "11") (pinfunction "Q3_11") (pintype "unspecified"))
      (node (ref "U66") (pin "11") (pinfunction "Q3_11") (pintype "unspecified"))
    )
    (net (code "17") (name "A4") (class "Default")
      (node (ref "U53") (pin "8") (pinfunction "A4_8") (pintype "unspecified"))
      (node (ref "U54") (pin "14") (pinfunction "Q0_14") (pintype "unspecified"))
      (node (ref "U67") (pin "14") (pinfunction "Q0_14") (pintype "unspecified"))
    )
    (net (code "18") (name "A5") (class "Default")
      (node (ref "U53") (pin "7") (pinfunction "A5_7") (pintype "unspecified"))
      (node (ref "U54") (pin "13") (pinfunction "Q1_13") (pintype "unspecified"))
      (node (ref "U67") (pin "13") (pinfunction "Q1_13") (pintype "unspecified"))
    )
    (net (code "19") (name "A6") (class "Default")
      (node (ref "U53") (pin "6") (pinfunction "A6_6") (pintype "unspecified"))
      (node (ref "U54") (pin "12") (pinfunction "Q2_12") (pintype "unspecified"))
      (node (ref "U67") (pin "12") (pinfunction "Q2_12") (pintype "unspecified"))
    )
    (net (code "20") (name "A7") (class "Default")
      (node (ref "U53") (pin "5") (pinfunction "A7_5") (pintype "unspecified"))
      (node (ref "U54") (pin "11") (pinfunction "Q3_11") (pintype "unspecified"))
      (node (ref "U67") (pin "11") (pinfunction "Q3_11") (pintype "unspecified"))
    )
    (net (code "21") (name "A8") (class "Default")
      (node (ref "U68") (pin "27") (pinfunction "A8_27") (pintype "unspecified"))
      (node (ref "U75") (pin "14") (pinfunction "Q0_14") (pintype "unspecified"))
    )
    (net (code "22") (name "A9") (class "Default")
      (node (ref "U68") (pin "26") (pinfunction "A9_26") (pintype "unspecified"))
      (node (ref "U75") (pin "13") (pinfunction "Q1_13") (pintype "unspecified"))
    )
    (net (code "23") (name "A10") (class "Default")
      (node (ref "U68") (pin "23") (pinfunction "A10_23") (pintype "unspecified"))
      (node (ref "U75") (pin "12") (pinfunction "Q2_12") (pintype "unspecified"))
    )
    (net (code "24") (name "A11") (class "Default")
      (node (ref "U68") (pin "25") (pinfunction "A11_25") (pintype "unspecified"))
      (node (ref "U75") (pin "11") (pinfunction "Q3_11") (pintype "unspecified"))
    )
    (net (code "25") (name "CLK") (class "Default")
      (node (ref "U13") (pin "2") (pinfunction "CP_2") (pintype "unspecified"))
      (node (ref "U2") (pin "2") (pinfunction "CP_2") (pintype "unspecified"))
      (node (ref "U24") (pin "2") (pinfunction "CP_2") (pintype "unspecified"))
      (node (ref "U25") (pin "3") (pinfunction "1CLK_3") (pintype "unspecified"))
      (node (ref "U28") (pin "12") (pinfunction "CS#_12") (pintype "unspecified"))
      (node (ref "U3") (pin "2") (pinfunction "CP_2") (pintype "unspecified"))
      (node (ref "U30") (pin "12") (pinfunction "CS#_12") (pintype "unspecified"))
      (node (ref "U45") (pin "2") (pinfunction "CP_2") (pintype "unspecified"))
      (node (ref "U46") (pin "2") (pinfunction "CP_2") (pintype "unspecified"))
      (node (ref "U47") (pin "2") (pinfunction "CP_2") (pintype "unspecified"))
      (node (ref "U49") (pin "2") (pinfunction "CP_2") (pintype "unspecified"))
      (node (ref "U5") (pin "3") (pinfunction "1CLK_3") (pintype "unspecified"))
      (node (ref "U50") (pin "2") (pinfunction "CP_2") (pintype "unspecified"))
      (node (ref "U53") (pin "22") (pinfunction "CE#_22") (pintype "unspecified"))
      (node (ref "U54") (pin "2") (pinfunction "CP_2") (pintype "unspecified"))
      (node (ref "U55") (pin "2") (pinfunction "CP_2") (pintype "unspecified"))
      (node (ref "U57") (pin "12") (pinfunction "CS#_12") (pintype "unspecified"))
      (node (ref "U65") (pin "12") (pinfunction "CS#_12") (pintype "unspecified"))
      (node (ref "U66") (pin "2") (pinfunction "CP_2") (pintype "unspecified"))
      (node (ref "U67") (pin "2") (pinfunction "CP_2") (pintype "unspecified"))
      (node (ref "U68") (pin "22") (pinfunction "CE#_22") (pintype "unspecified"))
      (node (ref "U71") (pin "2") (pinfunction "CP_2") (pintype "unspecified"))
      (node (ref "U72") (pin "2") (pinfunction "CP_2") (pintype "unspecified"))
      (node (ref "U73") (pin "2") (pinfunction "CP_2") (pintype "unspecified"))
      (node (ref "U75") (pin "2") (pinfunction "CP_2") (pintype "unspecified"))
      (node (ref "X1") (pin "11") (pinfunction "OUT_11") (pintype "unspecified"))
      (node (ref "X1") (pin "8") (pinfunction "OUT_8") (pintype "unspecified"))
      (node (ref "X2") (pin "11") (pinfunction "OUT_11") (pintype "unspecified"))
      (node (ref "X2") (pin "8") (pinfunction "OUT_8") (pintype "unspecified"))
      (node (ref "X3") (pin "11") (pinfunction "OUT_11") (pintype "unspecified"))
      (node (ref "X3") (pin "8") (pinfunction "OUT_8") (pintype "unspecified"))
      (node (ref "X4") (pin "11") (pinfunction "OUT_11") (pintype "unspecified"))
      (node (ref "X4") (pin "8") (pinfunction "OUT_8") (pintype "unspecified"))
    )
    (net (code "26") (name "CS") (class "Default")
      (node (ref "U32") (pin "2") (pinfunction "1Y#_2") (pintype "unspecified"))
      (node (ref "U33") (pin "1") (pinfunction "1A_1") (pintype "unspecified"))
      (node (ref "U33") (pin "9") (pinfunction "3A_9") (pintype "unspecified"))
    )
    (net (code "27") (name "D0") (class "Default")
      (node (ref "U10") (pin "3") (pinfunction "D0_3") (pintype "unspecified"))
      (node (ref "U11") (pin "2") (pinfunction "1Q_2") (pintype "unspecified"))
      (node (ref "U12") (pin "3") (pinfunction "D0_3") (pintype "unspecified"))
      (node (ref "U34") (pin "3") (pinfunction "D0_3") (pintype "unspecified"))
      (node (ref "U37") (pin "3") (pinfunction "D0_3") (pintype "unspecified"))
      (node (ref "U38") (pin "3") (pinfunction "D0_3") (pintype "unspecified"))
      (node (ref "U39") (pin "3") (pinfunction "D0_3") (pintype "unspecified"))
      (node (ref "U40") (pin "3") (pinfunction "D0_3") (pintype "unspecified"))
      (node (ref "U41") (pin "3") (pinfunction "D0_3") (pintype "unspecified"))
      (node (ref "U42") (pin "3") (pinfunction "D0_3") (pintype "unspecified"))
      (node (ref "U43") (pin "3") (pinfunction "D0_3") (pintype "unspecified"))
      (node (ref "U44") (pin "3") (pinfunction "D0_3") (pintype "unspecified"))
      (node (ref "U51") (pin "3") (pinfunction "D0_3") (pintype "unspecified"))
      (node (ref "U52") (pin "3") (pinfunction "D0_3") (pintype "unspecified"))
      (node (ref "U56") (pin "3") (pinfunction "D0_3") (pintype "unspecified"))
      (node (ref "U62") (pin "3") (pinfunction "D0_3") (pintype "unspecified"))
      (node (ref "U69") (pin "3") (pinfunction "D0_3") (pintype "unspecified"))
      (node (ref "U70") (pin "3") (pinfunction "D0_3") (pintype "unspecified"))
      (node (ref "U8") (pin "3") (pinfunction "D0_3") (pintype "unspecified"))
    )
    (net (code "28") (name "D1") (class "Default")
      (node (ref "U10") (pin "4") (pinfunction "D1_4") (pintype "unspecified"))
      (node (ref "U11") (pin "5") (pinfunction "2Q_5") (pintype "unspecified"))
      (node (ref "U12") (pin "4") (pinfunction "D1_4") (pintype "unspecified"))
      (node (ref "U34") (pin "4") (pinfunction "D1_4") (pintype "unspecified"))
      (node (ref "U37") (pin "4") (pinfunction "D1_4") (pintype "unspecified"))
      (node (ref "U38") (pin "4") (pinfunction "D1_4") (pintype "unspecified"))
      (node (ref "U39") (pin "4") (pinfunction "D1_4") (pintype "unspecified"))
      (node (ref "U40") (pin "4") (pinfunction "D1_4") (pintype "unspecified"))
      (node (ref "U41") (pin "4") (pinfunction "D1_4") (pintype "unspecified"))
      (node (ref "U42") (pin "4") (pinfunction "D1_4") (pintype "unspecified"))
      (node (ref "U43") (pin "4") (pinfunction "D1_4") (pintype "unspecified"))
      (node (ref "U44") (pin "4") (pinfunction "D1_4") (pintype "unspecified"))
      (node (ref "U51") (pin "4") (pinfunction "D1_4") (pintype "unspecified"))
      (node (ref "U52") (pin "4") (pinfunction "D1_4") (pintype "unspecified"))
      (node (ref "U56") (pin "4") (pinfunction "D1_4") (pintype "unspecified"))
      (node (ref "U62") (pin "4") (pinfunction "D1_4") (pintype "unspecified"))
      (node (ref "U69") (pin "4") (pinfunction "D1_4") (pintype "unspecified"))
      (node (ref "U70") (pin "4") (pinfunction "D1_4") (pintype "unspecified"))
      (node (ref "U8") (pin "4") (pinfunction "D1_4") (pintype "unspecified"))
    )
    (net (code "29") (name "D2") (class "Default")
      (node (ref "U10") (pin "7") (pinfunction "D2_7") (pintype "unspecified"))
      (node (ref "U11") (pin "6") (pinfunction "3Q_6") (pintype "unspecified"))
      (node (ref "U12") (pin "7") (pinfunction "D2_7") (pintype "unspecified"))
      (node (ref "U34") (pin "7") (pinfunction "D2_7") (pintype "unspecified"))
      (node (ref "U37") (pin "7") (pinfunction "D2_7") (pintype "unspecified"))
      (node (ref "U38") (pin "7") (pinfunction "D2_7") (pintype "unspecified"))
      (node (ref "U39") (pin "7") (pinfunction "D2_7") (pintype "unspecified"))
      (node (ref "U40") (pin "7") (pinfunction "D2_7") (pintype "unspecified"))
      (node (ref "U41") (pin "7") (pinfunction "D2_7") (pintype "unspecified"))
      (node (ref "U42") (pin "7") (pinfunction "D2_7") (pintype "unspecified"))
      (node (ref "U43") (pin "7") (pinfunction "D2_7") (pintype "unspecified"))
      (node (ref "U44") (pin "7") (pinfunction "D2_7") (pintype "unspecified"))
      (node (ref "U51") (pin "7") (pinfunction "D2_7") (pintype "unspecified"))
      (node (ref "U52") (pin "7") (pinfunction "D2_7") (pintype "unspecified"))
      (node (ref "U56") (pin "7") (pinfunction "D2_7") (pintype "unspecified"))
      (node (ref "U62") (pin "7") (pinfunction "D2_7") (pintype "unspecified"))
      (node (ref "U69") (pin "7") (pinfunction "D2_7") (pintype "unspecified"))
      (node (ref "U70") (pin "7") (pinfunction "D2_7") (pintype "unspecified"))
      (node (ref "U8") (pin "7") (pinfunction "D2_7") (pintype "unspecified"))
    )
    (net (code "30") (name "D3") (class "Default")
      (node (ref "U10") (pin "8") (pinfunction "D3_8") (pintype "unspecified"))
      (node (ref "U11") (pin "9") (pinfunction "4Q_9") (pintype "unspecified"))
      (node (ref "U12") (pin "8") (pinfunction "D3_8") (pintype "unspecified"))
      (node (ref "U34") (pin "8") (pinfunction "D3_8") (pintype "unspecified"))
      (node (ref "U37") (pin "8") (pinfunction "D3_8") (pintype "unspecified"))
      (node (ref "U38") (pin "8") (pinfunction "D3_8") (pintype "unspecified"))
      (node (ref "U39") (pin "8") (pinfunction "D3_8") (pintype "unspecified"))
      (node (ref "U40") (pin "8") (pinfunction "D3_8") (pintype "unspecified"))
      (node (ref "U41") (pin "8") (pinfunction "D3_8") (pintype "unspecified"))
      (node (ref "U42") (pin "8") (pinfunction "D3_8") (pintype "unspecified"))
      (node (ref "U43") (pin "8") (pinfunction "D3_8") (pintype "unspecified"))
      (node (ref "U44") (pin "8") (pinfunction "D3_8") (pintype "unspecified"))
      (node (ref "U51") (pin "8") (pinfunction "D3_8") (pintype "unspecified"))
      (node (ref "U52") (pin "8") (pinfunction "D3_8") (pintype "unspecified"))
      (node (ref "U56") (pin "8") (pinfunction "D3_8") (pintype "unspecified"))
      (node (ref "U62") (pin "8") (pinfunction "D3_8") (pintype "unspecified"))
      (node (ref "U69") (pin "8") (pinfunction "D3_8") (pintype "unspecified"))
      (node (ref "U70") (pin "8") (pinfunction "D3_8") (pintype "unspecified"))
      (node (ref "U8") (pin "8") (pinfunction "D3_8") (pintype "unspecified"))
    )
    (net (code "31") (name "D4") (class "Default")
      (node (ref "U10") (pin "13") (pinfunction "D4_13") (pintype "unspecified"))
      (node (ref "U11") (pin "12") (pinfunction "5Q_12") (pintype "unspecified"))
      (node (ref "U12") (pin "13") (pinfunction "D4_13") (pintype "unspecified"))
      (node (ref "U34") (pin "13") (pinfunction "D4_13") (pintype "unspecified"))
      (node (ref "U37") (pin "13") (pinfunction "D4_13") (pintype "unspecified"))
      (node (ref "U38") (pin "13") (pinfunction "D4_13") (pintype "unspecified"))
      (node (ref "U39") (pin "13") (pinfunction "D4_13") (pintype "unspecified"))
      (node (ref "U40") (pin "13") (pinfunction "D4_13") (pintype "unspecified"))
      (node (ref "U41") (pin "13") (pinfunction "D4_13") (pintype "unspecified"))
      (node (ref "U42") (pin "13") (pinfunction "D4_13") (pintype "unspecified"))
      (node (ref "U43") (pin "13") (pinfunction "D4_13") (pintype "unspecified"))
      (node (ref "U44") (pin "13") (pinfunction "D4_13") (pintype "unspecified"))
      (node (ref "U51") (pin "13") (pinfunction "D4_13") (pintype "unspecified"))
      (node (ref "U52") (pin "13") (pinfunction "D4_13") (pintype "unspecified"))
      (node (ref "U56") (pin "13") (pinfunction "D4_13") (pintype "unspecified"))
      (node (ref "U62") (pin "13") (pinfunction "D4_13") (pintype "unspecified"))
      (node (ref "U69") (pin "13") (pinfunction "D4_13") (pintype "unspecified"))
      (node (ref "U70") (pin "13") (pinfunction "D4_13") (pintype "unspecified"))
      (node (ref "U8") (pin "13") (pinfunction "D4_13") (pintype "unspecified"))
    )
    (net (code "32") (name "D5") (class "Default")
      (node (ref "U10") (pin "14") (pinfunction "D5_14") (pintype "unspecified"))
      (node (ref "U11") (pin "15") (pinfunction "6Q_15") (pintype "unspecified"))
      (node (ref "U12") (pin "14") (pinfunction "D5_14") (pintype "unspecified"))
      (node (ref "U34") (pin "14") (pinfunction "D5_14") (pintype "unspecified"))
      (node (ref "U37") (pin "14") (pinfunction "D5_14") (pintype "unspecified"))
      (node (ref "U38") (pin "14") (pinfunction "D5_14") (pintype "unspecified"))
      (node (ref "U39") (pin "14") (pinfunction "D5_14") (pintype "unspecified"))
      (node (ref "U40") (pin "14") (pinfunction "D5_14") (pintype "unspecified"))
      (node (ref "U41") (pin "14") (pinfunction "D5_14") (pintype "unspecified"))
      (node (ref "U42") (pin "14") (pinfunction "D5_14") (pintype "unspecified"))
      (node (ref "U43") (pin "14") (pinfunction "D5_14") (pintype "unspecified"))
      (node (ref "U44") (pin "14") (pinfunction "D5_14") (pintype "unspecified"))
      (node (ref "U51") (pin "14") (pinfunction "D5_14") (pintype "unspecified"))
      (node (ref "U52") (pin "14") (pinfunction "D5_14") (pintype "unspecified"))
      (node (ref "U56") (pin "14") (pinfunction "D5_14") (pintype "unspecified"))
      (node (ref "U62") (pin "14") (pinfunction "D5_14") (pintype "unspecified"))
      (node (ref "U69") (pin "14") (pinfunction "D5_14") (pintype "unspecified"))
      (node (ref "U70") (pin "14") (pinfunction "D5_14") (pintype "unspecified"))
      (node (ref "U8") (pin "14") (pinfunction "D5_14") (pintype "unspecified"))
    )
    (net (code "33") (name "D6") (class "Default")
      (node (ref "U10") (pin "17") (pinfunction "D6_17") (pintype "unspecified"))
      (node (ref "U11") (pin "16") (pinfunction "7Q_16") (pintype "unspecified"))
      (node (ref "U12") (pin "17") (pinfunction "D6_17") (pintype "unspecified"))
      (node (ref "U34") (pin "17") (pinfunction "D6_17") (pintype "unspecified"))
      (node (ref "U37") (pin "17") (pinfunction "D6_17") (pintype "unspecified"))
      (node (ref "U38") (pin "17") (pinfunction "D6_17") (pintype "unspecified"))
      (node (ref "U39") (pin "17") (pinfunction "D6_17") (pintype "unspecified"))
      (node (ref "U40") (pin "17") (pinfunction "D6_17") (pintype "unspecified"))
      (node (ref "U41") (pin "17") (pinfunction "D6_17") (pintype "unspecified"))
      (node (ref "U42") (pin "17") (pinfunction "D6_17") (pintype "unspecified"))
      (node (ref "U43") (pin "17") (pinfunction "D6_17") (pintype "unspecified"))
      (node (ref "U44") (pin "17") (pinfunction "D6_17") (pintype "unspecified"))
      (node (ref "U51") (pin "17") (pinfunction "D6_17") (pintype "unspecified"))
      (node (ref "U52") (pin "17") (pinfunction "D6_17") (pintype "unspecified"))
      (node (ref "U56") (pin "17") (pinfunction "D6_17") (pintype "unspecified"))
      (node (ref "U62") (pin "17") (pinfunction "D6_17") (pintype "unspecified"))
      (node (ref "U69") (pin "17") (pinfunction "D6_17") (pintype "unspecified"))
      (node (ref "U70") (pin "17") (pinfunction "D6_17") (pintype "unspecified"))
      (node (ref "U8") (pin "17") (pinfunction "D6_17") (pintype "unspecified"))
    )
    (net (code "34") (name "D7") (class "Default")
      (node (ref "U10") (pin "18") (pinfunction "D7_18") (pintype "unspecified"))
      (node (ref "U11") (pin "19") (pinfunction "8Q_19") (pintype "unspecified"))
      (node (ref "U12") (pin "18") (pinfunction "D7_18") (pintype "unspecified"))
      (node (ref "U34") (pin "18") (pinfunction "D7_18") (pintype "unspecified"))
      (node (ref "U37") (pin "18") (pinfunction "D7_18") (pintype "unspecified"))
      (node (ref "U38") (pin "18") (pinfunction "D7_18") (pintype "unspecified"))
      (node (ref "U39") (pin "18") (pinfunction "D7_18") (pintype "unspecified"))
      (node (ref "U40") (pin "18") (pinfunction "D7_18") (pintype "unspecified"))
      (node (ref "U41") (pin "18") (pinfunction "D7_18") (pintype "unspecified"))
      (node (ref "U42") (pin "18") (pinfunction "D7_18") (pintype "unspecified"))
      (node (ref "U43") (pin "18") (pinfunction "D7_18") (pintype "unspecified"))
      (node (ref "U44") (pin "18") (pinfunction "D7_18") (pintype "unspecified"))
      (node (ref "U51") (pin "18") (pinfunction "D7_18") (pintype "unspecified"))
      (node (ref "U52") (pin "18") (pinfunction "D7_18") (pintype "unspecified"))
      (node (ref "U56") (pin "18") (pinfunction "D7_18") (pintype "unspecified"))
      (node (ref "U62") (pin "18") (pinfunction "D7_18") (pintype "unspecified"))
      (node (ref "U69") (pin "18") (pinfunction "D7_18") (pintype "unspecified"))
      (node (ref "U70") (pin "18") (pinfunction "D7_18") (pintype "unspecified"))
      (node (ref "U8") (pin "18") (pinfunction "D7_18") (pintype "unspecified"))
    )
    (net (code "35") (name "DAC-b0") (class "Default")
      (node (ref "U29") (pin "3") (pinfunction "1Y_3") (pintype "unspecified"))
      (node (ref "U30") (pin "7") (pinfunction "DB4_7") (pintype "unspecified"))
      (node (ref "U53") (pin "13") (pinfunction "DQ0_13") (pintype "unspecified"))
      (node (ref "U57") (pin "11") (pinfunction "DB0_11") (pintype "unspecified"))
      (node (ref "U65") (pin "11") (pinfunction "DB0_11") (pintype "unspecified"))
      (node (ref "U68") (pin "13") (pinfunction "DQ0_13") (pintype "unspecified"))
    )
    (net (code "36") (name "DAC-b1") (class "Default")
      (node (ref "U29") (pin "6") (pinfunction "2Y_6") (pintype "unspecified"))
      (node (ref "U30") (pin "6") (pinfunction "DB5_6") (pintype "unspecified"))
      (node (ref "U53") (pin "14") (pinfunction "DQ1_14") (pintype "unspecified"))
      (node (ref "U57") (pin "10") (pinfunction "DB1_10") (pintype "unspecified"))
      (node (ref "U65") (pin "10") (pinfunction "DB1_10") (pintype "unspecified"))
      (node (ref "U68") (pin "14") (pinfunction "DQ1_14") (pintype "unspecified"))
    )
    (net (code "37") (name "DAC-b2") (class "Default")
      (node (ref "U29") (pin "8") (pinfunction "3Y_8") (pintype "unspecified"))
      (node (ref "U30") (pin "5") (pinfunction "DB6_5") (pintype "unspecified"))
      (node (ref "U53") (pin "15") (pinfunction "DQ2_15") (pintype "unspecified"))
      (node (ref "U57") (pin "9") (pinfunction "DB2_9") (pintype "unspecified"))
      (node (ref "U65") (pin "9") (pinfunction "DB2_9") (pintype "unspecified"))
      (node (ref "U68") (pin "15") (pinfunction "DQ2_15") (pintype "unspecified"))
    )
    (net (code "38") (name "DAC-b3") (class "Default")
      (node (ref "U29") (pin "11") (pinfunction "4Y_11") (pintype "unspecified"))
      (node (ref "U30") (pin "4") (pinfunction "DB7_4") (pintype "unspecified"))
      (node (ref "U53") (pin "17") (pinfunction "DQ3_17") (pintype "unspecified"))
      (node (ref "U57") (pin "8") (pinfunction "DB3_8") (pintype "unspecified"))
      (node (ref "U65") (pin "8") (pinfunction "DB3_8") (pintype "unspecified"))
      (node (ref "U68") (pin "17") (pinfunction "DQ3_17") (pintype "unspecified"))
    )
    (net (code "39") (name "DAC-b4") (class "Default")
      (node (ref "U53") (pin "18") (pinfunction "DQ4_18") (pintype "unspecified"))
      (node (ref "U57") (pin "7") (pinfunction "DB4_7") (pintype "unspecified"))
      (node (ref "U65") (pin "7") (pinfunction "DB4_7") (pintype "unspecified"))
      (node (ref "U68") (pin "18") (pinfunction "DQ4_18") (pintype "unspecified"))
    )
    (net (code "40") (name "DAC-b5") (class "Default")
      (node (ref "U53") (pin "19") (pinfunction "DQ5_19") (pintype "unspecified"))
      (node (ref "U57") (pin "6") (pinfunction "DB5_6") (pintype "unspecified"))
      (node (ref "U65") (pin "6") (pinfunction "DB5_6") (pintype "unspecified"))
      (node (ref "U68") (pin "19") (pinfunction "DQ5_19") (pintype "unspecified"))
    )
    (net (code "41") (name "DAC-b6") (class "Default")
      (node (ref "U53") (pin "20") (pinfunction "DQ6_20") (pintype "unspecified"))
      (node (ref "U57") (pin "5") (pinfunction "DB6_5") (pintype "unspecified"))
      (node (ref "U65") (pin "5") (pinfunction "DB6_5") (pintype "unspecified"))
      (node (ref "U68") (pin "20") (pinfunction "DQ6_20") (pintype "unspecified"))
    )
    (net (code "42") (name "DAC-b7") (class "Default")
      (node (ref "U53") (pin "21") (pinfunction "DQ7_21") (pintype "unspecified"))
      (node (ref "U57") (pin "4") (pinfunction "DB7_4") (pintype "unspecified"))
      (node (ref "U65") (pin "4") (pinfunction "DB7_4") (pintype "unspecified"))
      (node (ref "U68") (pin "21") (pinfunction "DQ7_21") (pintype "unspecified"))
    )
    (net (code "43") (name "DUTY_D0") (class "Default")
      (node (ref "U10") (pin "12") (pinfunction "Q4_12") (pintype "unspecified"))
      (node (ref "U14") (pin "2") (pinfunction "S1_2") (pintype "unspecified"))
      (node (ref "U39") (pin "12") (pinfunction "Q4_12") (pintype "unspecified"))
    )
    (net (code "44") (name "DUTY_D1") (class "Default")
      (node (ref "U10") (pin "15") (pinfunction "Q5_15") (pintype "unspecified"))
      (node (ref "U14") (pin "14") (pinfunction "S0_14") (pintype "unspecified"))
      (node (ref "U39") (pin "15") (pinfunction "Q5_15") (pintype "unspecified"))
    )
    (net (code "45") (name "GND") (class "Default")
      (node (ref "U1") (pin "1") (pinfunction "OE#_1") (pintype "unspecified"))
      (node (ref "U1") (pin "10") (pinfunction "GND_10") (pintype "unspecified"))
      (node (ref "U10") (pin "1") (pinfunction "OE#_1") (pintype "unspecified"))
      (node (ref "U10") (pin "10") (pinfunction "GND_10") (pintype "unspecified"))
      (node (ref "U11") (pin "1") (pinfunction "OE#_1") (pintype "unspecified"))
      (node (ref "U11") (pin "10") (pinfunction "GND_10") (pintype "unspecified"))
      (node (ref "U12") (pin "1") (pinfunction "OE#_1") (pintype "unspecified"))
      (node (ref "U12") (pin "10") (pinfunction "GND_10") (pintype "unspecified"))
      (node (ref "U13") (pin "3") (pinfunction "P0_3") (pintype "unspecified"))
      (node (ref "U13") (pin "4") (pinfunction "P1_4") (pintype "unspecified"))
      (node (ref "U13") (pin "5") (pinfunction "P2_5") (pintype "unspecified"))
      (node (ref "U13") (pin "6") (pinfunction "P3_6") (pintype "unspecified"))
      (node (ref "U13") (pin "8") (pinfunction "GND_8") (pintype "unspecified"))
      (node (ref "U14") (pin "1") (pinfunction "1E#_1") (pintype "unspecified"))
      (node (ref "U14") (pin "8") (pinfunction "GND_8") (pintype "unspecified"))
      (node (ref "U15") (pin "7") (pinfunction "GND_7") (pintype "unspecified"))
      (node (ref "U16") (pin "7") (pinfunction "GND_7") (pintype "unspecified"))
      (node (ref "U17") (pin "12") (pinfunction "CS#_12") (pintype "unspecified"))
      (node (ref "U17") (pin "13") (pinfunction "WR#_13") (pintype "unspecified"))
      (node (ref "U17") (pin "16") (pinfunction "RFB_16") (pintype "unspecified"))
      (node (ref "U17") (pin "3") (pinfunction "GND_3") (pintype "unspecified"))
      (node (ref "U18") (pin "1") (pinfunction "1E#_1") (pintype "unspecified"))
      (node (ref "U18") (pin "8") (pinfunction "GND_8") (pintype "unspecified"))
      (node (ref "U19") (pin "6") (pinfunction "E#_6") (pintype "unspecified"))
      (node (ref "U19") (pin "7") (pinfunction "VEE_7") (pintype "unspecified"))
      (node (ref "U19") (pin "8") (pinfunction "GND_8") (pintype "unspecified"))
      (node (ref "U2") (pin "8") (pinfunction "GND_8") (pintype "unspecified"))
      (node (ref "U20") (pin "7") (pinfunction "GND_7") (pintype "unspecified"))
      (node (ref "U21") (pin "7") (pinfunction "GND_7") (pintype "unspecified"))
      (node (ref "U22") (pin "7") (pinfunction "GND_7") (pintype "unspecified"))
      (node (ref "U23") (pin "7") (pinfunction "GND_7") (pintype "unspecified"))
      (node (ref "U24") (pin "8") (pinfunction "GND_8") (pintype "unspecified"))
      (node (ref "U25") (pin "7") (pinfunction "GND_7") (pintype "unspecified"))
      (node (ref "U26") (pin "7") (pinfunction "GND_7") (pintype "unspecified"))
      (node (ref "U27") (pin "7") (pinfunction "GND_7") (pintype "unspecified"))
      (node (ref "U28") (pin "10") (pinfunction "DB1_10") (pintype "unspecified"))
      (node (ref "U28") (pin "11") (pinfunction "DB0_11") (pintype "unspecified"))
      (node (ref "U28") (pin "13") (pinfunction "WR#_13") (pintype "unspecified"))
      (node (ref "U28") (pin "16") (pinfunction "RFB_16") (pintype "unspecified"))
      (node (ref "U28") (pin "3") (pinfunction "GND_3") (pintype "unspecified"))
      (node (ref "U28") (pin "9") (pinfunction "DB2_9") (pintype "unspecified"))
      (node (ref "U29") (pin "7") (pinfunction "GND_7") (pintype "unspecified"))
      (node (ref "U3") (pin "8") (pinfunction "GND_8") (pintype "unspecified"))
      (node (ref "U30") (pin "10") (pinfunction "DB1_10") (pintype "unspecified"))
      (node (ref "U30") (pin "11") (pinfunction "DB0_11") (pintype "unspecified"))
      (node (ref "U30") (pin "13") (pinfunction "WR#_13") (pintype "unspecified"))
      (node (ref "U30") (pin "16") (pinfunction "RFB_16") (pintype "unspecified"))
      (node (ref "U30") (pin "3") (pinfunction "GND_3") (pintype "unspecified"))
      (node (ref "U30") (pin "8") (pinfunction "DB3_8") (pintype "unspecified"))
      (node (ref "U30") (pin "9") (pinfunction "DB2_9") (pintype "unspecified"))
      (node (ref "U31") (pin "7") (pinfunction "VSS_7") (pintype "unspecified"))
      (node (ref "U32") (pin "7") (pinfunction "GND_7") (pintype "unspecified"))
      (node (ref "U33") (pin "7") (pinfunction "GND_7") (pintype "unspecified"))
      (node (ref "U34") (pin "1") (pinfunction "OE#_1") (pintype "unspecified"))
      (node (ref "U34") (pin "10") (pinfunction "GND_10") (pintype "unspecified"))
      (node (ref "U35") (pin "7") (pinfunction "GND_7") (pintype "unspecified"))
      (node (ref "U36") (pin "7") (pinfunction "GND_7") (pintype "unspecified"))
      (node (ref "U37") (pin "1") (pinfunction "OE#_1") (pintype "unspecified"))
      (node (ref "U37") (pin "10") (pinfunction "GND_10") (pintype "unspecified"))
      (node (ref "U38") (pin "1") (pinfunction "OE#_1") (pintype "unspecified"))
      (node (ref "U38") (pin "10") (pinfunction "GND_10") (pintype "unspecified"))
      (node (ref "U39") (pin "1") (pinfunction "OE#_1") (pintype "unspecified"))
      (node (ref "U39") (pin "10") (pinfunction "GND_10") (pintype "unspecified"))
      (node (ref "U4") (pin "7") (pinfunction "GND_7") (pintype "unspecified"))
      (node (ref "U40") (pin "1") (pinfunction "OE#_1") (pintype "unspecified"))
      (node (ref "U40") (pin "10") (pinfunction "GND_10") (pintype "unspecified"))
      (node (ref "U41") (pin "1") (pinfunction "OE#_1") (pintype "unspecified"))
      (node (ref "U41") (pin "10") (pinfunction "GND_10") (pintype "unspecified"))
      (node (ref "U42") (pin "1") (pinfunction "OE#_1") (pintype "unspecified"))
      (node (ref "U42") (pin "10") (pinfunction "GND_10") (pintype "unspecified"))
      (node (ref "U43") (pin "1") (pinfunction "OE#_1") (pintype "unspecified"))
      (node (ref "U43") (pin "10") (pinfunction "GND_10") (pintype "unspecified"))
      (node (ref "U44") (pin "1") (pinfunction "OE#_1") (pintype "unspecified"))
      (node (ref "U44") (pin "10") (pinfunction "GND_10") (pintype "unspecified"))
      (node (ref "U45") (pin "8") (pinfunction "GND_8") (pintype "unspecified"))
      (node (ref "U46") (pin "8") (pinfunction "GND_8") (pintype "unspecified"))
      (node (ref "U47") (pin "8") (pinfunction "GND_8") (pintype "unspecified"))
      (node (ref "U48") (pin "7") (pinfunction "GND_7") (pintype "unspecified"))
      (node (ref "U49") (pin "8") (pinfunction "GND_8") (pintype "unspecified"))
      (node (ref "U5") (pin "7") (pinfunction "GND_7") (pintype "unspecified"))
      (node (ref "U50") (pin "8") (pinfunction "GND_8") (pintype "unspecified"))
      (node (ref "U51") (pin "1") (pinfunction "OE#_1") (pintype "unspecified"))
      (node (ref "U51") (pin "10") (pinfunction "GND_10") (pintype "unspecified"))
      (node (ref "U52") (pin "1") (pinfunction "OE#_1") (pintype "unspecified"))
      (node (ref "U52") (pin "10") (pinfunction "GND_10") (pintype "unspecified"))
      (node (ref "U53") (pin "1") (pinfunction "A18_1") (pintype "unspecified"))
      (node (ref "U53") (pin "16") (pinfunction "VSS_16") (pintype "unspecified"))
      (node (ref "U53") (pin "2") (pinfunction "A16_2") (pintype "unspecified"))
      (node (ref "U53") (pin "24") (pinfunction "OE#_24") (pintype "unspecified"))
      (node (ref "U53") (pin "30") (pinfunction "A17_30") (pintype "unspecified"))
      (node (ref "U54") (pin "3") (pinfunction "P0_3") (pintype "unspecified"))
      (node (ref "U54") (pin "4") (pinfunction "P1_4") (pintype "unspecified"))
      (node (ref "U54") (pin "5") (pinfunction "P2_5") (pintype "unspecified"))
      (node (ref "U54") (pin "6") (pinfunction "P3_6") (pintype "unspecified"))
      (node (ref "U54") (pin "8") (pinfunction "GND_8") (pintype "unspecified"))
      (node (ref "U55") (pin "3") (pinfunction "P0_3") (pintype "unspecified"))
      (node (ref "U55") (pin "4") (pinfunction "P1_4") (pintype "unspecified"))
      (node (ref "U55") (pin "5") (pinfunction "P2_5") (pintype "unspecified"))
      (node (ref "U55") (pin "6") (pinfunction "P3_6") (pintype "unspecified"))
      (node (ref "U55") (pin "8") (pinfunction "GND_8") (pintype "unspecified"))
      (node (ref "U56") (pin "1") (pinfunction "OE#_1") (pintype "unspecified"))
      (node (ref "U56") (pin "10") (pinfunction "GND_10") (pintype "unspecified"))
      (node (ref "U57") (pin "13") (pinfunction "WR#_13") (pintype "unspecified"))
      (node (ref "U57") (pin "16") (pinfunction "RFB_16") (pintype "unspecified"))
      (node (ref "U57") (pin "3") (pinfunction "GND_3") (pintype "unspecified"))
      (node (ref "U58") (pin "12") (pinfunction "CS#_12") (pintype "unspecified"))
      (node (ref "U58") (pin "13") (pinfunction "WR#_13") (pintype "unspecified"))
      (node (ref "U58") (pin "16") (pinfunction "RFB_16") (pintype "unspecified"))
      (node (ref "U58") (pin "3") (pinfunction "GND_3") (pintype "unspecified"))
      (node (ref "U59") (pin "1") (pinfunction "1_1") (pintype "unspecified"))
      (node (ref "U6") (pin "12") (pinfunction "CS#_12") (pintype "unspecified"))
      (node (ref "U6") (pin "13") (pinfunction "WR#_13") (pintype "unspecified"))
      (node (ref "U6") (pin "16") (pinfunction "RFB_16") (pintype "unspecified"))
      (node (ref "U6") (pin "3") (pinfunction "GND_3") (pintype "unspecified"))
      (node (ref "U60") (pin "1") (pinfunction "1_1") (pintype "unspecified"))
      (node (ref "U61") (pin "12") (pinfunction "CS#_12") (pintype "unspecified"))
      (node (ref "U61") (pin "13") (pinfunction "WR#_13") (pintype "unspecified"))
      (node (ref "U61") (pin "16") (pinfunction "RFB_16") (pintype "unspecified"))
      (node (ref "U61") (pin "3") (pinfunction "GND_3") (pintype "unspecified"))
      (node (ref "U62") (pin "1") (pinfunction "OE#_1") (pintype "unspecified"))
      (node (ref "U62") (pin "10") (pinfunction "GND_10") (pintype "unspecified"))
      (node (ref "U63") (pin "1") (pinfunction "1_1") (pintype "unspecified"))
      (node (ref "U64") (pin "12") (pinfunction "CS#_12") (pintype "unspecified"))
      (node (ref "U64") (pin "13") (pinfunction "WR#_13") (pintype "unspecified"))
      (node (ref "U64") (pin "16") (pinfunction "RFB_16") (pintype "unspecified"))
      (node (ref "U64") (pin "3") (pinfunction "GND_3") (pintype "unspecified"))
      (node (ref "U65") (pin "13") (pinfunction "WR#_13") (pintype "unspecified"))
      (node (ref "U65") (pin "16") (pinfunction "RFB_16") (pintype "unspecified"))
      (node (ref "U65") (pin "3") (pinfunction "GND_3") (pintype "unspecified"))
      (node (ref "U66") (pin "3") (pinfunction "P0_3") (pintype "unspecified"))
      (node (ref "U66") (pin "4") (pinfunction "P1_4") (pintype "unspecified"))
      (node (ref "U66") (pin "5") (pinfunction "P2_5") (pintype "unspecified"))
      (node (ref "U66") (pin "6") (pinfunction "P3_6") (pintype "unspecified"))
      (node (ref "U66") (pin "8") (pinfunction "GND_8") (pintype "unspecified"))
      (node (ref "U67") (pin "3") (pinfunction "P0_3") (pintype "unspecified"))
      (node (ref "U67") (pin "4") (pinfunction "P1_4") (pintype "unspecified"))
      (node (ref "U67") (pin "5") (pinfunction "P2_5") (pintype "unspecified"))
      (node (ref "U67") (pin "6") (pinfunction "P3_6") (pintype "unspecified"))
      (node (ref "U67") (pin "8") (pinfunction "GND_8") (pintype "unspecified"))
      (node (ref "U68") (pin "1") (pinfunction "A18_1") (pintype "unspecified"))
      (node (ref "U68") (pin "16") (pinfunction "VSS_16") (pintype "unspecified"))
      (node (ref "U68") (pin "24") (pinfunction "OE#_24") (pintype "unspecified"))
      (node (ref "U68") (pin "30") (pinfunction "A17_30") (pintype "unspecified"))
      (node (ref "U69") (pin "1") (pinfunction "OE#_1") (pintype "unspecified"))
      (node (ref "U69") (pin "10") (pinfunction "GND_10") (pintype "unspecified"))
      (node (ref "U7") (pin "1") (pinfunction "1_1") (pintype "unspecified"))
      (node (ref "U70") (pin "1") (pinfunction "OE#_1") (pintype "unspecified"))
      (node (ref "U70") (pin "10") (pinfunction "GND_10") (pintype "unspecified"))
      (node (ref "U71") (pin "8") (pinfunction "GND_8") (pintype "unspecified"))
      (node (ref "U72") (pin "8") (pinfunction "GND_8") (pintype "unspecified"))
      (node (ref "U73") (pin "8") (pinfunction "GND_8") (pintype "unspecified"))
      (node (ref "U74") (pin "7") (pinfunction "GND_7") (pintype "unspecified"))
      (node (ref "U75") (pin "3") (pinfunction "P0_3") (pintype "unspecified"))
      (node (ref "U75") (pin "4") (pinfunction "P1_4") (pintype "unspecified"))
      (node (ref "U75") (pin "5") (pinfunction "P2_5") (pintype "unspecified"))
      (node (ref "U75") (pin "6") (pinfunction "P3_6") (pintype "unspecified"))
      (node (ref "U75") (pin "8") (pinfunction "GND_8") (pintype "unspecified"))
      (node (ref "U76") (pin "7") (pinfunction "GND_7") (pintype "unspecified"))
      (node (ref "U77") (pin "7") (pinfunction "GND_7") (pintype "unspecified"))
      (node (ref "U78") (pin "7") (pinfunction "GND_7") (pintype "unspecified"))
      (node (ref "U8") (pin "1") (pinfunction "OE#_1") (pintype "unspecified"))
      (node (ref "U8") (pin "10") (pinfunction "GND_10") (pintype "unspecified"))
      (node (ref "U9") (pin "22") (pinfunction "GND_22") (pintype "unspecified"))
      (node (ref "U9") (pin "3") (pinfunction "GND_3") (pintype "unspecified"))
      (node (ref "X1") (pin "4") (pinfunction "GND_4") (pintype "unspecified"))
      (node (ref "X1") (pin "7") (pinfunction "GND_7") (pintype "unspecified"))
      (node (ref "X2") (pin "4") (pinfunction "GND_4") (pintype "unspecified"))
      (node (ref "X2") (pin "7") (pinfunction "GND_7") (pintype "unspecified"))
      (node (ref "X3") (pin "4") (pinfunction "GND_4") (pintype "unspecified"))
      (node (ref "X3") (pin "7") (pinfunction "GND_7") (pintype "unspecified"))
      (node (ref "X4") (pin "4") (pinfunction "GND_4") (pintype "unspecified"))
      (node (ref "X4") (pin "7") (pinfunction "GND_7") (pintype "unspecified"))
    )
    (net (code "46") (name "HC164_Q4") (class "Default")
      (node (ref "U22") (pin "3") (pinfunction "Q0_3") (pintype "unspecified"))
      (node (ref "U31") (pin "6") (pinfunction "D_6") (pintype "unspecified"))
    )
    (net (code "47") (name "HC164_Q5") (class "Default")
      (node (ref "U22") (pin "5") (pinfunction "Q2_5") (pintype "unspecified"))
      (node (ref "U31") (pin "5") (pinfunction "C_5") (pintype "unspecified"))
    )
    (net (code "48") (name "HC164_Q6") (class "Default")
      (node (ref "U22") (pin "12") (pinfunction "Q6_12") (pintype "unspecified"))
      (node (ref "U31") (pin "2") (pinfunction "B_2") (pintype "unspecified"))
    )
    (net (code "49") (name "HC164_Q7") (class "Default")
      (node (ref "U17") (pin "15") (pinfunction "REF_15") (pintype "unspecified"))
      (node (ref "U22") (pin "13") (pinfunction "Q7_13") (pintype "unspecified"))
      (node (ref "U31") (pin "1") (pinfunction "A_1") (pintype "unspecified"))
    )
    (net (code "50") (name "NOISE_D0") (class "Default")
      (node (ref "U12") (pin "2") (pinfunction "Q0_2") (pintype "unspecified"))
      (node (ref "U17") (pin "10") (pinfunction "DB1_10") (pintype "unspecified"))
      (node (ref "U17") (pin "11") (pinfunction "DB0_11") (pintype "unspecified"))
      (node (ref "U17") (pin "7") (pinfunction "DB4_7") (pintype "unspecified"))
      (node (ref "U17") (pin "8") (pinfunction "DB3_8") (pintype "unspecified"))
      (node (ref "U17") (pin "9") (pinfunction "DB2_9") (pintype "unspecified"))
      (node (ref "U37") (pin "2") (pinfunction "Q0_2") (pintype "unspecified"))
    )
    (net (code "51") (name "NOISE_D1") (class "Default")
      (node (ref "U12") (pin "5") (pinfunction "Q1_5") (pintype "unspecified"))
      (node (ref "U17") (pin "6") (pinfunction "DB5_6") (pintype "unspecified"))
      (node (ref "U37") (pin "5") (pinfunction "Q1_5") (pintype "unspecified"))
    )
    (net (code "52") (name "NOISE_D2") (class "Default")
      (node (ref "U12") (pin "6") (pinfunction "Q2_6") (pintype "unspecified"))
      (node (ref "U17") (pin "5") (pinfunction "DB6_5") (pintype "unspecified"))
      (node (ref "U37") (pin "6") (pinfunction "Q2_6") (pintype "unspecified"))
    )
    (net (code "53") (name "NOISE_D3") (class "Default")
      (node (ref "U12") (pin "9") (pinfunction "Q3_9") (pintype "unspecified"))
      (node (ref "U17") (pin "4") (pinfunction "DB7_4") (pintype "unspecified"))
      (node (ref "U37") (pin "9") (pinfunction "Q3_9") (pintype "unspecified"))
    )
    (net (code "54") (name "NOISE_D4") (class "Default")
      (node (ref "U12") (pin "12") (pinfunction "Q4_12") (pintype "unspecified"))
      (node (ref "U18") (pin "2") (pinfunction "S1_2") (pintype "unspecified"))
      (node (ref "U37") (pin "12") (pinfunction "Q4_12") (pintype "unspecified"))
    )
    (net (code "55") (name "NOISE_D5") (class "Default")
      (node (ref "U12") (pin "15") (pinfunction "Q5_15") (pintype "unspecified"))
      (node (ref "U18") (pin "14") (pinfunction "S0_14") (pintype "unspecified"))
      (node (ref "U37") (pin "15") (pinfunction "Q5_15") (pintype "unspecified"))
    )
    (net (code "56") (name "NOISE_D6") (class "Default")
      (node (ref "U12") (pin "16") (pinfunction "Q6_16") (pintype "unspecified"))
      (node (ref "U20") (pin "1") (pinfunction "1A_1") (pintype "unspecified"))
      (node (ref "U20") (pin "10") (pinfunction "3B_10") (pintype "unspecified"))
      (node (ref "U20") (pin "2") (pinfunction "1B_2") (pintype "unspecified"))
      (node (ref "U37") (pin "16") (pinfunction "Q6_16") (pintype "unspecified"))
    )
    (net (code "57") (name "NOISE_D7") (class "Default")
      (node (ref "U12") (pin "19") (pinfunction "Q7_19") (pintype "unspecified"))
      (node (ref "U37") (pin "19") (pinfunction "Q7_19") (pintype "unspecified"))
    )
    (net (code "58") (name "NOISE_OUT") (class "Default")
      (node (ref "U17") (pin "1") (pinfunction "OUT1_1") (pintype "unspecified"))
    )
    (net (code "59") (name "NOISE{slash}2") (class "Default")
      (node (ref "U13") (pin "14") (pinfunction "Q0_14") (pintype "unspecified"))
      (node (ref "U18") (pin "6") (pinfunction "1I0_6") (pintype "unspecified"))
    )
    (net (code "60") (name "NOISE{slash}4") (class "Default")
      (node (ref "U13") (pin "13") (pinfunction "Q1_13") (pintype "unspecified"))
      (node (ref "U18") (pin "5") (pinfunction "1I1_5") (pintype "unspecified"))
    )
    (net (code "61") (name "NOISE{slash}8") (class "Default")
      (node (ref "U13") (pin "12") (pinfunction "Q2_12") (pintype "unspecified"))
      (node (ref "U18") (pin "4") (pinfunction "1I2_4") (pintype "unspecified"))
    )
    (net (code "62") (name "NOISE{slash}16") (class "Default")
      (node (ref "U13") (pin "11") (pinfunction "Q3_11") (pintype "unspecified"))
      (node (ref "U18") (pin "3") (pinfunction "1I3_3") (pintype "unspecified"))
    )
    (net (code "63") (name "N_Start") (class "Default")
      (node (ref "U21") (pin "11") (pinfunction "4Y_11") (pintype "unspecified"))
    )
    (net (code "64") (name "Net-(U5-2D)") (class "Default")
      (node (ref "U5") (pin "12") (pinfunction "2D_12") (pintype "unspecified"))
      (node (ref "U5") (pin "8") (pinfunction "2Q#_8") (pintype "unspecified"))
    )
    (net (code "65") (name "Net-(U15-1D)") (class "Default")
      (node (ref "U15") (pin "2") (pinfunction "1D_2") (pintype "unspecified"))
      (node (ref "U15") (pin "6") (pinfunction "1Q#_6") (pintype "unspecified"))
    )
    (net (code "66") (name "Net-(U15-2D)") (class "Default")
      (node (ref "U15") (pin "12") (pinfunction "2D_12") (pintype "unspecified"))
      (node (ref "U15") (pin "8") (pinfunction "2Q#_8") (pintype "unspecified"))
    )
    (net (code "67") (name "Net-(U25-2D)") (class "Default")
      (node (ref "U25") (pin "12") (pinfunction "2D_12") (pintype "unspecified"))
      (node (ref "U25") (pin "8") (pinfunction "2Q#_8") (pintype "unspecified"))
    )
    (net (code "68") (name "Net-(U26-1D)") (class "Default")
      (node (ref "U26") (pin "2") (pinfunction "1D_2") (pintype "unspecified"))
      (node (ref "U26") (pin "6") (pinfunction "1Q#_6") (pintype "unspecified"))
    )
    (net (code "69") (name "Net-(U26-2D)") (class "Default")
      (node (ref "U26") (pin "12") (pinfunction "2D_12") (pintype "unspecified"))
      (node (ref "U26") (pin "8") (pinfunction "2Q#_8") (pintype "unspecified"))
    )
    (net (code "70") (name "Net-(U27-1D)") (class "Default")
      (node (ref "U27") (pin "2") (pinfunction "1D_2") (pintype "unspecified"))
      (node (ref "U27") (pin "6") (pinfunction "1Q#_6") (pintype "unspecified"))
    )
    (net (code "71") (name "Net-(U27-2D)") (class "Default")
      (node (ref "U27") (pin "12") (pinfunction "2D_12") (pintype "unspecified"))
      (node (ref "U27") (pin "8") (pinfunction "2Q#_8") (pintype "unspecified"))
    )
    (net (code "72") (name "Net-(U77-1D)") (class "Default")
      (node (ref "U77") (pin "2") (pinfunction "1D_2") (pintype "unspecified"))
      (node (ref "U77") (pin "6") (pinfunction "1Q#_6") (pintype "unspecified"))
    )
    (net (code "73") (name "PSG_A0") (class "Default")
      (node (ref "U34") (pin "2") (pinfunction "Q0_2") (pintype "unspecified"))
      (node (ref "U35") (pin "1") (pinfunction "1A_1") (pintype "unspecified"))
    )
    (net (code "74") (name "PSG_A1") (class "Default")
      (node (ref "U34") (pin "5") (pinfunction "Q1_5") (pintype "unspecified"))
      (node (ref "U35") (pin "4") (pinfunction "2A_4") (pintype "unspecified"))
    )
    (net (code "75") (name "PSG_A2") (class "Default")
      (node (ref "U34") (pin "6") (pinfunction "Q2_6") (pintype "unspecified"))
      (node (ref "U35") (pin "10") (pinfunction "3B_10") (pintype "unspecified"))
    )
    (net (code "76") (name "PSG_A3") (class "Default")
      (node (ref "U34") (pin "9") (pinfunction "Q3_9") (pintype "unspecified"))
      (node (ref "U35") (pin "13") (pinfunction "4B_13") (pintype "unspecified"))
    )
    (net (code "77") (name "PSG_A4") (class "Default")
      (node (ref "U34") (pin "12") (pinfunction "Q4_12") (pintype "unspecified"))
      (node (ref "U36") (pin "1") (pinfunction "1A_1") (pintype "unspecified"))
    )
    (net (code "78") (name "PSG_A5") (class "Default")
      (node (ref "U34") (pin "15") (pinfunction "Q5_15") (pintype "unspecified"))
      (node (ref "U36") (pin "4") (pinfunction "2A_4") (pintype "unspecified"))
    )
    (net (code "79") (name "PSG_A6") (class "Default")
      (node (ref "U34") (pin "16") (pinfunction "Q6_16") (pintype "unspecified"))
      (node (ref "U36") (pin "10") (pinfunction "3B_10") (pintype "unspecified"))
    )
    (net (code "80") (name "PSG_A7") (class "Default")
      (node (ref "U34") (pin "19") (pinfunction "Q7_19") (pintype "unspecified"))
      (node (ref "U36") (pin "13") (pinfunction "4B_13") (pintype "unspecified"))
    )
    (net (code "81") (name "PSG_OUT") (class "Default")
      (node (ref "U6") (pin "1") (pinfunction "OUT1_1") (pintype "unspecified"))
      (node (ref "U7") (pin "2") (pinfunction "+_2") (pintype "unspecified"))
    )
    (net (code "82") (name "Q0") (class "Default")
      (node (ref "U2") (pin "3") (pinfunction "P0_3") (pintype "unspecified"))
      (node (ref "U38") (pin "2") (pinfunction "Q0_2") (pintype "unspecified"))
      (node (ref "U8") (pin "2") (pinfunction "Q0_2") (pintype "unspecified"))
    )
    (net (code "83") (name "Q1") (class "Default")
      (node (ref "U2") (pin "4") (pinfunction "P1_4") (pintype "unspecified"))
      (node (ref "U38") (pin "5") (pinfunction "Q1_5") (pintype "unspecified"))
      (node (ref "U8") (pin "5") (pinfunction "Q1_5") (pintype "unspecified"))
    )
    (net (code "84") (name "Q2") (class "Default")
      (node (ref "U2") (pin "5") (pinfunction "P2_5") (pintype "unspecified"))
      (node (ref "U38") (pin "6") (pinfunction "Q2_6") (pintype "unspecified"))
      (node (ref "U8") (pin "6") (pinfunction "Q2_6") (pintype "unspecified"))
    )
    (net (code "85") (name "Q3") (class "Default")
      (node (ref "U2") (pin "6") (pinfunction "P3_6") (pintype "unspecified"))
      (node (ref "U38") (pin "9") (pinfunction "Q3_9") (pintype "unspecified"))
      (node (ref "U8") (pin "9") (pinfunction "Q3_9") (pintype "unspecified"))
    )
    (net (code "86") (name "Q4") (class "Default")
      (node (ref "U3") (pin "3") (pinfunction "P0_3") (pintype "unspecified"))
      (node (ref "U38") (pin "12") (pinfunction "Q4_12") (pintype "unspecified"))
      (node (ref "U8") (pin "12") (pinfunction "Q4_12") (pintype "unspecified"))
    )
    (net (code "87") (name "Q5") (class "Default")
      (node (ref "U3") (pin "4") (pinfunction "P1_4") (pintype "unspecified"))
      (node (ref "U38") (pin "15") (pinfunction "Q5_15") (pintype "unspecified"))
      (node (ref "U8") (pin "15") (pinfunction "Q5_15") (pintype "unspecified"))
    )
    (net (code "88") (name "Q6") (class "Default")
      (node (ref "U3") (pin "5") (pinfunction "P2_5") (pintype "unspecified"))
      (node (ref "U38") (pin "16") (pinfunction "Q6_16") (pintype "unspecified"))
      (node (ref "U8") (pin "16") (pinfunction "Q6_16") (pintype "unspecified"))
    )
    (net (code "89") (name "Q7") (class "Default")
      (node (ref "U3") (pin "6") (pinfunction "P3_6") (pintype "unspecified"))
      (node (ref "U38") (pin "19") (pinfunction "Q7_19") (pintype "unspecified"))
      (node (ref "U8") (pin "19") (pinfunction "Q7_19") (pintype "unspecified"))
    )
    (net (code "90") (name "RC1") (class "Default")
      (node (ref "C3") (pin "1") (pinfunction "1_1") (pintype "unspecified"))
      (node (ref "C4") (pin "1") (pinfunction "1_1") (pintype "unspecified"))
      (node (ref "U21") (pin "10") (pinfunction "3B_10") (pintype "unspecified"))
    )
    (net (code "91") (name "RC2") (class "Default")
      (node (ref "C4") (pin "2") (pinfunction "2_2") (pintype "unspecified"))
      (node (ref "U21") (pin "9") (pinfunction "3A_9") (pintype "unspecified"))
    )
    (net (code "92") (name "ROM-A0") (class "Default")
      (node (ref "U68") (pin "12") (pinfunction "A0_12") (pintype "unspecified"))
    )
    (net (code "93") (name "ROM-A1") (class "Default")
      (node (ref "U68") (pin "11") (pinfunction "A1_11") (pintype "unspecified"))
    )
    (net (code "94") (name "ROM-A2") (class "Default")
      (node (ref "U68") (pin "10") (pinfunction "A2_10") (pintype "unspecified"))
    )
    (net (code "95") (name "ROM-A3") (class "Default")
      (node (ref "U68") (pin "9") (pinfunction "A3_9") (pintype "unspecified"))
    )
    (net (code "96") (name "ROM-A4") (class "Default")
      (node (ref "U68") (pin "8") (pinfunction "A4_8") (pintype "unspecified"))
    )
    (net (code "97") (name "ROM-A5") (class "Default")
      (node (ref "U68") (pin "7") (pinfunction "A5_7") (pintype "unspecified"))
    )
    (net (code "98") (name "ROM-A6") (class "Default")
      (node (ref "U68") (pin "6") (pinfunction "A6_6") (pintype "unspecified"))
    )
    (net (code "99") (name "ROM-A7") (class "Default")
      (node (ref "U68") (pin "5") (pinfunction "A7_5") (pintype "unspecified"))
    )
    (net (code "100") (name "ROM-A12") (class "Default")
      (node (ref "U68") (pin "4") (pinfunction "A12_4") (pintype "unspecified"))
      (node (ref "U76") (pin "10") (pinfunction "3B_10") (pintype "unspecified"))
      (node (ref "U77") (pin "5") (pinfunction "1Q_5") (pintype "unspecified"))
    )
    (net (code "101") (name "SQR_REF_IN") (class "Default")
      (node (ref "U19") (pin "14") (pinfunction "AN_14") (pintype "unspecified"))
      (node (ref "U6") (pin "15") (pinfunction "REF_15") (pintype "unspecified"))
    )
    (net (code "102") (name "SQR{slash}NOISE") (class "Default")
      (node (ref "U10") (pin "16") (pinfunction "Q6_16") (pintype "unspecified"))
      (node (ref "U19") (pin "11") (pinfunction "S0_11") (pintype "unspecified"))
      (node (ref "U39") (pin "16") (pinfunction "Q6_16") (pintype "unspecified"))
    )
    (net (code "103") (name "VCC") (class "Default")
      (node (ref "U1") (pin "11") (pinfunction "LE_11") (pintype "unspecified"))
      (node (ref "U1") (pin "20") (pinfunction "VCC_20") (pintype "unspecified"))
      (node (ref "U10") (pin "20") (pinfunction "VCC_20") (pintype "unspecified"))
      (node (ref "U11") (pin "11") (pinfunction "LE_11") (pintype "unspecified"))
      (node (ref "U11") (pin "20") (pinfunction "VCC_20") (pintype "unspecified"))
      (node (ref "U12") (pin "20") (pinfunction "VCC_20") (pintype "unspecified"))
      (node (ref "U13") (pin "10") (pinfunction "TE_10") (pintype "unspecified"))
      (node (ref "U13") (pin "16") (pinfunction "VCC_16") (pintype "unspecified"))
      (node (ref "U13") (pin "7") (pinfunction "PE_7") (pintype "unspecified"))
      (node (ref "U13") (pin "9") (pinfunction "SPE#_9") (pintype "unspecified"))
      (node (ref "U14") (pin "15") (pinfunction "2E#_15") (pintype "unspecified"))
      (node (ref "U14") (pin "16") (pinfunction "VCC_16") (pintype "unspecified"))
      (node (ref "U15") (pin "10") (pinfunction "2PRE#_10") (pintype "unspecified"))
      (node (ref "U15") (pin "14") (pinfunction "VCC_14") (pintype "unspecified"))
      (node (ref "U15") (pin "4") (pinfunction "1PRE#_4") (pintype "unspecified"))
      (node (ref "U16") (pin "14") (pinfunction "VCC_14") (pintype "unspecified"))
      (node (ref "U17") (pin "14") (pinfunction "VDD_14") (pintype "unspecified"))
      (node (ref "U18") (pin "15") (pinfunction "2E#_15") (pintype "unspecified"))
      (node (ref "U18") (pin "16") (pinfunction "VCC_16") (pintype "unspecified"))
      (node (ref "U19") (pin "16") (pinfunction "VCC_16") (pintype "unspecified"))
      (node (ref "U2") (pin "10") (pinfunction "TE_10") (pintype "unspecified"))
      (node (ref "U2") (pin "16") (pinfunction "VCC_16") (pintype "unspecified"))
      (node (ref "U2") (pin "7") (pinfunction "PE_7") (pintype "unspecified"))
      (node (ref "U20") (pin "14") (pinfunction "VCC_14") (pintype "unspecified"))
      (node (ref "U21") (pin "14") (pinfunction "VCC_14") (pintype "unspecified"))
      (node (ref "U22") (pin "14") (pinfunction "VCC_14") (pintype "unspecified"))
      (node (ref "U22") (pin "2") (pinfunction "DS2_2") (pintype "unspecified"))
      (node (ref "U22") (pin "9") (pinfunction "MR#_9") (pintype "unspecified"))
      (node (ref "U23") (pin "14") (pinfunction "VCC_14") (pintype "unspecified"))
      (node (ref "U24") (pin "16") (pinfunction "VCC_16") (pintype "unspecified"))
      (node (ref "U25") (pin "10") (pinfunction "2PRE#_10") (pintype "unspecified"))
      (node (ref "U25") (pin "14") (pinfunction "VCC_14") (pintype "unspecified"))
      (node (ref "U25") (pin "4") (pinfunction "1PRE#_4") (pintype "unspecified"))
      (node (ref "U26") (pin "10") (pinfunction "2PRE#_10") (pintype "unspecified"))
      (node (ref "U26") (pin "14") (pinfunction "VCC_14") (pintype "unspecified"))
      (node (ref "U26") (pin "4") (pinfunction "1PRE#_4") (pintype "unspecified"))
      (node (ref "U27") (pin "10") (pinfunction "2PRE#_10") (pintype "unspecified"))
      (node (ref "U27") (pin "14") (pinfunction "VCC_14") (pintype "unspecified"))
      (node (ref "U27") (pin "4") (pinfunction "1PRE#_4") (pintype "unspecified"))
      (node (ref "U28") (pin "14") (pinfunction "VDD_14") (pintype "unspecified"))
      (node (ref "U28") (pin "15") (pinfunction "REF_15") (pintype "unspecified"))
      (node (ref "U3") (pin "16") (pinfunction "VCC_16") (pintype "unspecified"))
      (node (ref "U30") (pin "14") (pinfunction "VDD_14") (pintype "unspecified"))
      (node (ref "U30") (pin "15") (pinfunction "REF_15") (pintype "unspecified"))
      (node (ref "U31") (pin "14") (pinfunction "VDD_14") (pintype "unspecified"))
      (node (ref "U32") (pin "14") (pinfunction "VCC_14") (pintype "unspecified"))
      (node (ref "U33") (pin "14") (pinfunction "VCC_14") (pintype "unspecified"))
      (node (ref "U34") (pin "20") (pinfunction "VCC_20") (pintype "unspecified"))
      (node (ref "U35") (pin "14") (pinfunction "VCC_14") (pintype "unspecified"))
      (node (ref "U36") (pin "14") (pinfunction "VCC_14") (pintype "unspecified"))
      (node (ref "U37") (pin "20") (pinfunction "VCC_20") (pintype "unspecified"))
      (node (ref "U38") (pin "20") (pinfunction "VCC_20") (pintype "unspecified"))
      (node (ref "U39") (pin "20") (pinfunction "VCC_20") (pintype "unspecified"))
      (node (ref "U4") (pin "14") (pinfunction "VCC_14") (pintype "unspecified"))
      (node (ref "U40") (pin "20") (pinfunction "VCC_20") (pintype "unspecified"))
      (node (ref "U41") (pin "20") (pinfunction "VCC_20") (pintype "unspecified"))
      (node (ref "U42") (pin "20") (pinfunction "VCC_20") (pintype "unspecified"))
      (node (ref "U43") (pin "20") (pinfunction "VCC_20") (pintype "unspecified"))
      (node (ref "U44") (pin "20") (pinfunction "VCC_20") (pintype "unspecified"))
      (node (ref "U45") (pin "16") (pinfunction "VCC_16") (pintype "unspecified"))
      (node (ref "U46") (pin "10") (pinfunction "TE_10") (pintype "unspecified"))
      (node (ref "U46") (pin "16") (pinfunction "VCC_16") (pintype "unspecified"))
      (node (ref "U46") (pin "7") (pinfunction "PE_7") (pintype "unspecified"))
      (node (ref "U47") (pin "16") (pinfunction "VCC_16") (pintype "unspecified"))
      (node (ref "U48") (pin "14") (pinfunction "VCC_14") (pintype "unspecified"))
      (node (ref "U49") (pin "10") (pinfunction "TE_10") (pintype "unspecified"))
      (node (ref "U49") (pin "16") (pinfunction "VCC_16") (pintype "unspecified"))
      (node (ref "U49") (pin "7") (pinfunction "PE_7") (pintype "unspecified"))
      (node (ref "U5") (pin "10") (pinfunction "2PRE#_10") (pintype "unspecified"))
      (node (ref "U5") (pin "14") (pinfunction "VCC_14") (pintype "unspecified"))
      (node (ref "U5") (pin "4") (pinfunction "1PRE#_4") (pintype "unspecified"))
      (node (ref "U50") (pin "16") (pinfunction "VCC_16") (pintype "unspecified"))
      (node (ref "U51") (pin "20") (pinfunction "VCC_20") (pintype "unspecified"))
      (node (ref "U52") (pin "20") (pinfunction "VCC_20") (pintype "unspecified"))
      (node (ref "U53") (pin "31") (pinfunction "WE#_31") (pintype "unspecified"))
      (node (ref "U53") (pin "32") (pinfunction "VDD_32") (pintype "unspecified"))
      (node (ref "U54") (pin "16") (pinfunction "VCC_16") (pintype "unspecified"))
      (node (ref "U54") (pin "9") (pinfunction "SPE#_9") (pintype "unspecified"))
      (node (ref "U55") (pin "16") (pinfunction "VCC_16") (pintype "unspecified"))
      (node (ref "U55") (pin "9") (pinfunction "SPE#_9") (pintype "unspecified"))
      (node (ref "U56") (pin "20") (pinfunction "VCC_20") (pintype "unspecified"))
      (node (ref "U57") (pin "14") (pinfunction "VDD_14") (pintype "unspecified"))
      (node (ref "U57") (pin "15") (pinfunction "REF_15") (pintype "unspecified"))
      (node (ref "U58") (pin "14") (pinfunction "VDD_14") (pintype "unspecified"))
      (node (ref "U6") (pin "14") (pinfunction "VDD_14") (pintype "unspecified"))
      (node (ref "U61") (pin "14") (pinfunction "VDD_14") (pintype "unspecified"))
      (node (ref "U62") (pin "20") (pinfunction "VCC_20") (pintype "unspecified"))
      (node (ref "U64") (pin "14") (pinfunction "VDD_14") (pintype "unspecified"))
      (node (ref "U65") (pin "14") (pinfunction "VDD_14") (pintype "unspecified"))
      (node (ref "U65") (pin "15") (pinfunction "REF_15") (pintype "unspecified"))
      (node (ref "U66") (pin "16") (pinfunction "VCC_16") (pintype "unspecified"))
      (node (ref "U67") (pin "16") (pinfunction "VCC_16") (pintype "unspecified"))
      (node (ref "U68") (pin "31") (pinfunction "WE#_31") (pintype "unspecified"))
      (node (ref "U68") (pin "32") (pinfunction "VDD_32") (pintype "unspecified"))
      (node (ref "U69") (pin "20") (pinfunction "VCC_20") (pintype "unspecified"))
      (node (ref "U70") (pin "20") (pinfunction "VCC_20") (pintype "unspecified"))
      (node (ref "U71") (pin "16") (pinfunction "VCC_16") (pintype "unspecified"))
      (node (ref "U72") (pin "10") (pinfunction "TE_10") (pintype "unspecified"))
      (node (ref "U72") (pin "16") (pinfunction "VCC_16") (pintype "unspecified"))
      (node (ref "U72") (pin "7") (pinfunction "PE_7") (pintype "unspecified"))
      (node (ref "U73") (pin "16") (pinfunction "VCC_16") (pintype "unspecified"))
      (node (ref "U74") (pin "14") (pinfunction "VCC_14") (pintype "unspecified"))
      (node (ref "U75") (pin "16") (pinfunction "VCC_16") (pintype "unspecified"))
      (node (ref "U76") (pin "14") (pinfunction "VCC_14") (pintype "unspecified"))
      (node (ref "U77") (pin "14") (pinfunction "VCC_14") (pintype "unspecified"))
      (node (ref "U77") (pin "4") (pinfunction "1PRE#_4") (pintype "unspecified"))
      (node (ref "U78") (pin "14") (pinfunction "VCC_14") (pintype "unspecified"))
      (node (ref "U8") (pin "20") (pinfunction "VCC_20") (pintype "unspecified"))
      (node (ref "U9") (pin "2") (pinfunction "5V_2") (pintype "unspecified"))
      (node (ref "X1") (pin "14") (pinfunction "VCC_14") (pintype "unspecified"))
      (node (ref "X2") (pin "14") (pinfunction "VCC_14") (pintype "unspecified"))
      (node (ref "X3") (pin "14") (pinfunction "VCC_14") (pintype "unspecified"))
      (node (ref "X4") (pin "14") (pinfunction "VCC_14") (pintype "unspecified"))
    )
    (net (code "104") (name "VOL_Q0") (class "Default")
      (node (ref "U10") (pin "2") (pinfunction "Q0_2") (pintype "unspecified"))
      (node (ref "U39") (pin "2") (pinfunction "Q0_2") (pintype "unspecified"))
      (node (ref "U6") (pin "10") (pinfunction "DB1_10") (pintype "unspecified"))
      (node (ref "U6") (pin "11") (pinfunction "DB0_11") (pintype "unspecified"))
      (node (ref "U6") (pin "7") (pinfunction "DB4_7") (pintype "unspecified"))
      (node (ref "U6") (pin "8") (pinfunction "DB3_8") (pintype "unspecified"))
      (node (ref "U6") (pin "9") (pinfunction "DB2_9") (pintype "unspecified"))
    )
    (net (code "105") (name "VOL_Q1") (class "Default")
      (node (ref "U10") (pin "5") (pinfunction "Q1_5") (pintype "unspecified"))
      (node (ref "U39") (pin "5") (pinfunction "Q1_5") (pintype "unspecified"))
      (node (ref "U6") (pin "6") (pinfunction "DB5_6") (pintype "unspecified"))
    )
    (net (code "106") (name "VOL_Q2") (class "Default")
      (node (ref "U10") (pin "6") (pinfunction "Q2_6") (pintype "unspecified"))
      (node (ref "U39") (pin "6") (pinfunction "Q2_6") (pintype "unspecified"))
      (node (ref "U6") (pin "5") (pinfunction "DB6_5") (pintype "unspecified"))
    )
    (net (code "107") (name "VOL_Q3") (class "Default")
      (node (ref "U10") (pin "9") (pinfunction "Q3_9") (pintype "unspecified"))
      (node (ref "U39") (pin "9") (pinfunction "Q3_9") (pintype "unspecified"))
      (node (ref "U6") (pin "4") (pinfunction "DB7_4") (pintype "unspecified"))
    )
    (net (code "108") (name "WAVE") (class "Default")
      (node (ref "U19") (pin "13") (pinfunction "A1_13") (pintype "unspecified"))
      (node (ref "U3") (pin "13") (pinfunction "Q1_13") (pintype "unspecified"))
    )
    (net (code "109") (name "WAVE_OUT") (class "Default")
      (node (ref "U58") (pin "1") (pinfunction "OUT1_1") (pintype "unspecified"))
      (node (ref "U59") (pin "2") (pinfunction "+_2") (pintype "unspecified"))
      (node (ref "U60") (pin "2") (pinfunction "+_2") (pintype "unspecified"))
      (node (ref "U61") (pin "1") (pinfunction "OUT1_1") (pintype "unspecified"))
      (node (ref "U63") (pin "2") (pinfunction "+_2") (pintype "unspecified"))
      (node (ref "U64") (pin "1") (pinfunction "OUT1_1") (pintype "unspecified"))
    )
    (net (code "110") (name "WAVE_REF_IN") (class "Default")
      (node (ref "U28") (pin "1") (pinfunction "OUT1_1") (pintype "unspecified"))
      (node (ref "U30") (pin "1") (pinfunction "OUT1_1") (pintype "unspecified"))
      (node (ref "U57") (pin "1") (pinfunction "OUT1_1") (pintype "unspecified"))
      (node (ref "U58") (pin "15") (pinfunction "REF_15") (pintype "unspecified"))
      (node (ref "U61") (pin "15") (pinfunction "REF_15") (pintype "unspecified"))
      (node (ref "U64") (pin "15") (pinfunction "REF_15") (pintype "unspecified"))
      (node (ref "U65") (pin "1") (pinfunction "OUT1_1") (pintype "unspecified"))
    )
    (net (code "111") (name "WAVE_SEL") (class "Default")
      (node (ref "U10") (pin "19") (pinfunction "Q7_19") (pintype "unspecified"))
      (node (ref "U19") (pin "9") (pinfunction "S2_9") (pintype "unspecified"))
      (node (ref "U39") (pin "19") (pinfunction "Q7_19") (pintype "unspecified"))
    )
    (net (code "112") (name "addr_cp") (class "Default")
      (node (ref "U33") (pin "6") (pinfunction "2Y_6") (pintype "unspecified"))
      (node (ref "U34") (pin "11") (pinfunction "CP_11") (pintype "unspecified"))
    )
    (net (code "113") (name "at_8191") (class "Default")
      (node (ref "U76") (pin "8") (pinfunction "3Y_8") (pintype "unspecified"))
      (node (ref "U78") (pin "3") (pinfunction "2A_3") (pintype "unspecified"))
    )
    (net (code "114") (name "data_strobe") (class "Default")
      (node (ref "U33") (pin "11") (pinfunction "4Y_11") (pintype "unspecified"))
      (node (ref "U35") (pin "12") (pinfunction "4A_12") (pintype "unspecified"))
      (node (ref "U35") (pin "2") (pinfunction "1B_2") (pintype "unspecified"))
      (node (ref "U35") (pin "5") (pinfunction "2B_5") (pintype "unspecified"))
      (node (ref "U35") (pin "9") (pinfunction "3A_9") (pintype "unspecified"))
      (node (ref "U36") (pin "12") (pinfunction "4A_12") (pintype "unspecified"))
      (node (ref "U36") (pin "2") (pinfunction "1B_2") (pintype "unspecified"))
      (node (ref "U36") (pin "5") (pinfunction "2B_5") (pintype "unspecified"))
      (node (ref "U36") (pin "9") (pinfunction "3A_9") (pintype "unspecified"))
    )
    (net (code "115") (name "duty_25") (class "Default")
      (node (ref "U14") (pin "4") (pinfunction "1I2_4") (pintype "unspecified"))
      (node (ref "U16") (pin "10") (pinfunction "3B_10") (pintype "unspecified"))
      (node (ref "U16") (pin "3") (pinfunction "1Y_3") (pintype "unspecified"))
    )
    (net (code "116") (name "duty_125") (class "Default")
      (node (ref "U14") (pin "5") (pinfunction "1I1_5") (pintype "unspecified"))
      (node (ref "U16") (pin "8") (pinfunction "3Y_8") (pintype "unspecified"))
    )
    (net (code "117") (name "duty_625") (class "Default")
      (node (ref "U14") (pin "6") (pinfunction "1I0_6") (pintype "unspecified"))
      (node (ref "U16") (pin "6") (pinfunction "2Y_6") (pintype "unspecified"))
    )
    (net (code "118") (name "freq_tc") (class "Default")
      (node (ref "U76") (pin "12") (pinfunction "4A_12") (pintype "unspecified"))
    )
    (net (code "119") (name "n_ind") (class "Default")
      (node (ref "U20") (pin "12") (pinfunction "4A_12") (pintype "unspecified"))
      (node (ref "U20") (pin "6") (pinfunction "2Y_6") (pintype "unspecified"))
    )
    (net (code "120") (name "n_tc") (class "Default")
      (node (ref "U20") (pin "13") (pinfunction "4B_13") (pintype "unspecified"))
      (node (ref "U20") (pin "8") (pinfunction "3Y_8") (pintype "unspecified"))
    )
    (net (code "121") (name "noise_clk") (class "Default")
      (node (ref "U20") (pin "11") (pinfunction "4Y_11") (pintype "unspecified"))
      (node (ref "U22") (pin "8") (pinfunction "CP_8") (pintype "unspecified"))
    )
    (net (code "122") (name "noise_ind_clk") (class "Default")
      (node (ref "U18") (pin "7") (pinfunction "1Y_7") (pintype "unspecified"))
      (node (ref "U20") (pin "5") (pinfunction "2B_5") (pintype "unspecified"))
    )
    (net (code "123") (name "reg5_q0") (class "Default")
      (node (ref "U42") (pin "2") (pinfunction "Q0_2") (pintype "unspecified"))
      (node (ref "U53") (pin "27") (pinfunction "A8_27") (pintype "unspecified"))
      (node (ref "U56") (pin "2") (pinfunction "Q0_2") (pintype "unspecified"))
      (node (ref "U62") (pin "2") (pinfunction "Q0_2") (pintype "unspecified"))
      (node (ref "U68") (pin "28") (pinfunction "A13_28") (pintype "unspecified"))
    )
    (net (code "124") (name "reg5_q1") (class "Default")
      (node (ref "U42") (pin "5") (pinfunction "Q1_5") (pintype "unspecified"))
      (node (ref "U53") (pin "26") (pinfunction "A9_26") (pintype "unspecified"))
      (node (ref "U56") (pin "5") (pinfunction "Q1_5") (pintype "unspecified"))
      (node (ref "U62") (pin "5") (pinfunction "Q1_5") (pintype "unspecified"))
      (node (ref "U68") (pin "29") (pinfunction "A14_29") (pintype "unspecified"))
    )
    (net (code "125") (name "reg5_q2") (class "Default")
      (node (ref "U42") (pin "6") (pinfunction "Q2_6") (pintype "unspecified"))
      (node (ref "U53") (pin "23") (pinfunction "A10_23") (pintype "unspecified"))
      (node (ref "U56") (pin "6") (pinfunction "Q2_6") (pintype "unspecified"))
      (node (ref "U62") (pin "6") (pinfunction "Q2_6") (pintype "unspecified"))
      (node (ref "U68") (pin "3") (pinfunction "A15_3") (pintype "unspecified"))
    )
    (net (code "126") (name "reg5_q3") (class "Default")
      (node (ref "U42") (pin "9") (pinfunction "Q3_9") (pintype "unspecified"))
      (node (ref "U53") (pin "25") (pinfunction "A11_25") (pintype "unspecified"))
      (node (ref "U56") (pin "9") (pinfunction "Q3_9") (pintype "unspecified"))
      (node (ref "U62") (pin "9") (pinfunction "Q3_9") (pintype "unspecified"))
      (node (ref "U68") (pin "2") (pinfunction "A16_2") (pintype "unspecified"))
    )
    (net (code "127") (name "reg5_q4") (class "Default")
      (node (ref "U42") (pin "12") (pinfunction "Q4_12") (pintype "unspecified"))
      (node (ref "U53") (pin "4") (pinfunction "A12_4") (pintype "unspecified"))
      (node (ref "U56") (pin "12") (pinfunction "Q4_12") (pintype "unspecified"))
    )
    (net (code "128") (name "reg5_q5") (class "Default")
      (node (ref "U42") (pin "15") (pinfunction "Q5_15") (pintype "unspecified"))
      (node (ref "U53") (pin "28") (pinfunction "A13_28") (pintype "unspecified"))
      (node (ref "U56") (pin "15") (pinfunction "Q5_15") (pintype "unspecified"))
    )
    (net (code "129") (name "reg5_q6") (class "Default")
      (node (ref "U42") (pin "16") (pinfunction "Q6_16") (pintype "unspecified"))
      (node (ref "U53") (pin "29") (pinfunction "A14_29") (pintype "unspecified"))
      (node (ref "U56") (pin "16") (pinfunction "Q6_16") (pintype "unspecified"))
      (node (ref "U62") (pin "16") (pinfunction "Q6_16") (pintype "unspecified"))
    )
    (net (code "130") (name "reg5_q6_trig") (class "Default")
      (node (ref "U76") (pin "4") (pinfunction "2A_4") (pintype "unspecified"))
    )
    (net (code "131") (name "reg5_q7") (class "Default")
      (node (ref "U42") (pin "19") (pinfunction "Q7_19") (pintype "unspecified"))
      (node (ref "U53") (pin "3") (pinfunction "A15_3") (pintype "unspecified"))
      (node (ref "U56") (pin "19") (pinfunction "Q7_19") (pintype "unspecified"))
      (node (ref "U62") (pin "19") (pinfunction "Q7_19") (pintype "unspecified"))
    )
    (net (code "132") (name "reg5_q7_mode") (class "Default")
      (node (ref "U76") (pin "2") (pinfunction "1B_2") (pintype "unspecified"))
      (node (ref "U76") (pin "5") (pinfunction "2B_5") (pintype "unspecified"))
    )
    (net (code "133") (name "reg_cp[0") (class "Default")
      (node (ref "U35") (pin "3") (pinfunction "1Y_3") (pintype "unspecified"))
      (node (ref "U38") (pin "11") (pinfunction "CP_11") (pintype "unspecified"))
      (node (ref "U8") (pin "11") (pinfunction "CP_11") (pintype "unspecified"))
    )
    (net (code "134") (name "reg_cp[1") (class "Default")
      (node (ref "U10") (pin "11") (pinfunction "CP_11") (pintype "unspecified"))
      (node (ref "U35") (pin "6") (pinfunction "2Y_6") (pintype "unspecified"))
      (node (ref "U39") (pin "11") (pinfunction "CP_11") (pintype "unspecified"))
    )
    (net (code "135") (name "reg_cp[2") (class "Default")
      (node (ref "U12") (pin "11") (pinfunction "CP_11") (pintype "unspecified"))
      (node (ref "U35") (pin "8") (pinfunction "3Y_8") (pintype "unspecified"))
      (node (ref "U37") (pin "11") (pinfunction "CP_11") (pintype "unspecified"))
    )
    (net (code "136") (name "reg_cp[3") (class "Default")
      (node (ref "U35") (pin "11") (pinfunction "4Y_11") (pintype "unspecified"))
      (node (ref "U40") (pin "11") (pinfunction "CP_11") (pintype "unspecified"))
      (node (ref "U44") (pin "11") (pinfunction "CP_11") (pintype "unspecified"))
      (node (ref "U51") (pin "11") (pinfunction "CP_11") (pintype "unspecified"))
      (node (ref "U70") (pin "11") (pinfunction "CP_11") (pintype "unspecified"))
    )
    (net (code "137") (name "reg_cp[4") (class "Default")
      (node (ref "U36") (pin "3") (pinfunction "1Y_3") (pintype "unspecified"))
      (node (ref "U41") (pin "11") (pinfunction "CP_11") (pintype "unspecified"))
      (node (ref "U43") (pin "11") (pinfunction "CP_11") (pintype "unspecified"))
      (node (ref "U52") (pin "11") (pinfunction "CP_11") (pintype "unspecified"))
      (node (ref "U69") (pin "11") (pinfunction "CP_11") (pintype "unspecified"))
    )
    (net (code "138") (name "reg_cp[5") (class "Default")
      (node (ref "U36") (pin "6") (pinfunction "2Y_6") (pintype "unspecified"))
      (node (ref "U42") (pin "11") (pinfunction "CP_11") (pintype "unspecified"))
      (node (ref "U56") (pin "11") (pinfunction "CP_11") (pintype "unspecified"))
      (node (ref "U62") (pin "11") (pinfunction "CP_11") (pintype "unspecified"))
    )
    (net (code "139") (name "reg_cp[6") (class "Default")
      (node (ref "U36") (pin "8") (pinfunction "3Y_8") (pintype "unspecified"))
    )
    (net (code "140") (name "reg_cp[7") (class "Default")
      (node (ref "U36") (pin "11") (pinfunction "4Y_11") (pintype "unspecified"))
    )
    (net (code "141") (name "reload_pulse") (class "Default")
      (node (ref "U25") (pin "11") (pinfunction "2CLK_11") (pintype "unspecified"))
      (node (ref "U25") (pin "5") (pinfunction "1Q_5") (pintype "unspecified"))
      (node (ref "U5") (pin "11") (pinfunction "2CLK_11") (pintype "unspecified"))
      (node (ref "U5") (pin "5") (pinfunction "1Q_5") (pintype "unspecified"))
    )
    (net (code "142") (name "rom_tc_hi") (class "Default")
      (node (ref "U54") (pin "10") (pinfunction "TE_10") (pintype "unspecified"))
      (node (ref "U54") (pin "7") (pinfunction "PE_7") (pintype "unspecified"))
      (node (ref "U55") (pin "15") (pinfunction "TC_15") (pintype "unspecified"))
    )
    (net (code "143") (name "sqr_out") (class "Default")
      (node (ref "U14") (pin "7") (pinfunction "1Y_7") (pintype "unspecified"))
      (node (ref "U19") (pin "12") (pinfunction "A0_12") (pintype "unspecified"))
    )
    (net (code "144") (name "step") (class "Default")
      (node (ref "U76") (pin "11") (pinfunction "4Y_11") (pintype "unspecified"))
    )
    (net (code "145") (name "t1") (class "Default")
      (node (ref "U33") (pin "3") (pinfunction "1Y_3") (pintype "unspecified"))
      (node (ref "U33") (pin "4") (pinfunction "2A_4") (pintype "unspecified"))
    )
    (net (code "146") (name "t2") (class "Default")
      (node (ref "U33") (pin "12") (pinfunction "4A_12") (pintype "unspecified"))
      (node (ref "U33") (pin "8") (pinfunction "3Y_8") (pintype "unspecified"))
    )
    (net (code "147") (name "tc_a03") (class "Default")
      (node (ref "U66") (pin "15") (pinfunction "TC_15") (pintype "unspecified"))
      (node (ref "U67") (pin "10") (pinfunction "TE_10") (pintype "unspecified"))
      (node (ref "U67") (pin "7") (pinfunction "PE_7") (pintype "unspecified"))
    )
    (net (code "148") (name "tc_a47") (class "Default")
      (node (ref "U67") (pin "15") (pinfunction "TC_15") (pintype "unspecified"))
      (node (ref "U76") (pin "1") (pinfunction "1A_1") (pintype "unspecified"))
    )
    (net (code "149") (name "tc_a811") (class "Default")
      (node (ref "U75") (pin "15") (pinfunction "TC_15") (pintype "unspecified"))
      (node (ref "U76") (pin "9") (pinfunction "3A_9") (pintype "unspecified"))
      (node (ref "U77") (pin "3") (pinfunction "1CLK_3") (pintype "unspecified"))
    )
    (net (code "150") (name "tc_hi") (class "Default")
      (node (ref "U19") (pin "2") (pinfunction "B0_2") (pintype "unspecified"))
      (node (ref "U21") (pin "1") (pinfunction "1A_1") (pintype "unspecified"))
      (node (ref "U21") (pin "2") (pinfunction "1B_2") (pintype "unspecified"))
      (node (ref "U23") (pin "1") (pinfunction "1A_1") (pintype "unspecified"))
      (node (ref "U23") (pin "2") (pinfunction "1B_2") (pintype "unspecified"))
      (node (ref "U24") (pin "15") (pinfunction "TC_15") (pintype "unspecified"))
      (node (ref "U25") (pin "2") (pinfunction "1D_2") (pintype "unspecified"))
      (node (ref "U3") (pin "15") (pinfunction "TC_15") (pintype "unspecified"))
      (node (ref "U4") (pin "1") (pinfunction "1A_1") (pintype "unspecified"))
      (node (ref "U4") (pin "2") (pinfunction "1B_2") (pintype "unspecified"))
      (node (ref "U47") (pin "15") (pinfunction "TC_15") (pintype "unspecified"))
      (node (ref "U48") (pin "1") (pinfunction "1A_1") (pintype "unspecified"))
      (node (ref "U48") (pin "2") (pinfunction "1B_2") (pintype "unspecified"))
      (node (ref "U55") (pin "10") (pinfunction "TE_10") (pintype "unspecified"))
      (node (ref "U55") (pin "7") (pinfunction "PE_7") (pintype "unspecified"))
      (node (ref "U66") (pin "10") (pinfunction "TE_10") (pintype "unspecified"))
      (node (ref "U66") (pin "7") (pinfunction "PE_7") (pintype "unspecified"))
      (node (ref "U73") (pin "15") (pinfunction "TC_15") (pintype "unspecified"))
      (node (ref "U74") (pin "1") (pinfunction "1A_1") (pintype "unspecified"))
      (node (ref "U74") (pin "2") (pinfunction "1B_2") (pintype "unspecified"))
    )
    (net (code "151") (name "tc_hi_1D") (class "Default")
      (node (ref "U19") (pin "15") (pinfunction "BN_15") (pintype "unspecified"))
      (node (ref "U5") (pin "2") (pinfunction "1D_2") (pintype "unspecified"))
    )
    (net (code "152") (name "tc_hi_bind") (class "Default")
      (node (ref "U20") (pin "9") (pinfunction "3A_9") (pintype "unspecified"))
      (node (ref "U21") (pin "3") (pinfunction "1Y_3") (pintype "unspecified"))
    )
    (net (code "153") (name "tc_lo") (class "Default")
      (node (ref "U2") (pin "15") (pinfunction "TC_15") (pintype "unspecified"))
      (node (ref "U3") (pin "10") (pinfunction "TE_10") (pintype "unspecified"))
      (node (ref "U3") (pin "7") (pinfunction "PE_7") (pintype "unspecified"))
      (node (ref "U45") (pin "10") (pinfunction "TE_10") (pintype "unspecified"))
      (node (ref "U45") (pin "7") (pinfunction "PE_7") (pintype "unspecified"))
      (node (ref "U46") (pin "15") (pinfunction "TC_15") (pintype "unspecified"))
      (node (ref "U49") (pin "15") (pinfunction "TC_15") (pintype "unspecified"))
      (node (ref "U50") (pin "10") (pinfunction "TE_10") (pintype "unspecified"))
      (node (ref "U50") (pin "7") (pinfunction "PE_7") (pintype "unspecified"))
      (node (ref "U71") (pin "10") (pinfunction "TE_10") (pintype "unspecified"))
      (node (ref "U71") (pin "7") (pinfunction "PE_7") (pintype "unspecified"))
      (node (ref "U72") (pin "15") (pinfunction "TC_15") (pintype "unspecified"))
    )
    (net (code "154") (name "tc_mi") (class "Default")
      (node (ref "U24") (pin "10") (pinfunction "TE_10") (pintype "unspecified"))
      (node (ref "U24") (pin "7") (pinfunction "PE_7") (pintype "unspecified"))
      (node (ref "U45") (pin "15") (pinfunction "TC_15") (pintype "unspecified"))
      (node (ref "U47") (pin "10") (pinfunction "TE_10") (pintype "unspecified"))
      (node (ref "U47") (pin "7") (pinfunction "PE_7") (pintype "unspecified"))
      (node (ref "U50") (pin "15") (pinfunction "TC_15") (pintype "unspecified"))
      (node (ref "U71") (pin "15") (pinfunction "TC_15") (pintype "unspecified"))
      (node (ref "U73") (pin "10") (pinfunction "TE_10") (pintype "unspecified"))
      (node (ref "U73") (pin "7") (pinfunction "PE_7") (pintype "unspecified"))
    )
    (net (code "155") (name "tc_pcm") (class "Default")
      (node (ref "U75") (pin "10") (pinfunction "TE_10") (pintype "unspecified"))
      (node (ref "U75") (pin "7") (pinfunction "PE_7") (pintype "unspecified"))
      (node (ref "U76") (pin "3") (pinfunction "1Y_3") (pintype "unspecified"))
    )
    (net (code "156") (name "toggle_q") (class "Default")
      (node (ref "U14") (pin "3") (pinfunction "1I3_3") (pintype "unspecified"))
      (node (ref "U15") (pin "3") (pinfunction "1CLK_3") (pintype "unspecified"))
      (node (ref "U16") (pin "1") (pinfunction "1A_1") (pintype "unspecified"))
      (node (ref "U5") (pin "9") (pinfunction "2Q_9") (pintype "unspecified"))
    )
    (net (code "157") (name "toggle_q_wave") (class "Default")
      (node (ref "U25") (pin "9") (pinfunction "2Q_9") (pintype "unspecified"))
      (node (ref "U26") (pin "3") (pinfunction "1CLK_3") (pintype "unspecified"))
      (node (ref "U28") (pin "8") (pinfunction "DB3_8") (pintype "unspecified"))
      (node (ref "U29") (pin "1") (pinfunction "1A_1") (pintype "unspecified"))
    )
    (net (code "158") (name "toggle_q{slash}2") (class "Default")
      (node (ref "U15") (pin "11") (pinfunction "2CLK_11") (pintype "unspecified"))
      (node (ref "U15") (pin "5") (pinfunction "1Q_5") (pintype "unspecified"))
      (node (ref "U16") (pin "2") (pinfunction "1B_2") (pintype "unspecified"))
      (node (ref "U16") (pin "4") (pinfunction "2A_4") (pintype "unspecified"))
    )
    (net (code "159") (name "toggle_q{slash}4") (class "Default")
      (node (ref "U15") (pin "9") (pinfunction "2Q_9") (pintype "unspecified"))
      (node (ref "U16") (pin "5") (pinfunction "2B_5") (pintype "unspecified"))
      (node (ref "U16") (pin "9") (pinfunction "3A_9") (pintype "unspecified"))
    )
    (net (code "160") (name "trig_clr") (class "Default")
      (node (ref "U76") (pin "6") (pinfunction "2Y_6") (pintype "unspecified"))
      (node (ref "U78") (pin "1") (pinfunction "1A_1") (pintype "unspecified"))
    )
    (net (code "161") (name "unconnected-(U1-5D-Pad13)") (class "Default")
      (node (ref "U1") (pin "13") (pinfunction "5D_13") (pintype "unspecified+no_connect"))
    )
    (net (code "162") (name "unconnected-(U1-5Q-Pad12)") (class "Default")
      (node (ref "U1") (pin "12") (pinfunction "5Q_12") (pintype "unspecified+no_connect"))
    )
    (net (code "163") (name "unconnected-(U1-6D-Pad14)") (class "Default")
      (node (ref "U1") (pin "14") (pinfunction "6D_14") (pintype "unspecified+no_connect"))
    )
    (net (code "164") (name "unconnected-(U1-6Q-Pad15)") (class "Default")
      (node (ref "U1") (pin "15") (pinfunction "6Q_15") (pintype "unspecified+no_connect"))
    )
    (net (code "165") (name "unconnected-(U1-7D-Pad17)") (class "Default")
      (node (ref "U1") (pin "17") (pinfunction "7D_17") (pintype "unspecified+no_connect"))
    )
    (net (code "166") (name "unconnected-(U1-7Q-Pad16)") (class "Default")
      (node (ref "U1") (pin "16") (pinfunction "7Q_16") (pintype "unspecified+no_connect"))
    )
    (net (code "167") (name "unconnected-(U1-8D-Pad18)") (class "Default")
      (node (ref "U1") (pin "18") (pinfunction "8D_18") (pintype "unspecified+no_connect"))
    )
    (net (code "168") (name "unconnected-(U1-8Q-Pad19)") (class "Default")
      (node (ref "U1") (pin "19") (pinfunction "8Q_19") (pintype "unspecified+no_connect"))
    )
    (net (code "169") (name "unconnected-(U2-Q0-Pad14)") (class "Default")
      (node (ref "U2") (pin "14") (pinfunction "Q0_14") (pintype "unspecified+no_connect"))
    )
    (net (code "170") (name "unconnected-(U2-Q1-Pad13)") (class "Default")
      (node (ref "U2") (pin "13") (pinfunction "Q1_13") (pintype "unspecified+no_connect"))
    )
    (net (code "171") (name "unconnected-(U2-Q2-Pad12)") (class "Default")
      (node (ref "U2") (pin "12") (pinfunction "Q2_12") (pintype "unspecified+no_connect"))
    )
    (net (code "172") (name "unconnected-(U2-Q3-Pad11)") (class "Default")
      (node (ref "U2") (pin "11") (pinfunction "Q3_11") (pintype "unspecified+no_connect"))
    )
    (net (code "173") (name "unconnected-(U3-Q0-Pad14)") (class "Default")
      (node (ref "U3") (pin "14") (pinfunction "Q0_14") (pintype "unspecified+no_connect"))
    )
    (net (code "174") (name "unconnected-(U3-Q2-Pad12)") (class "Default")
      (node (ref "U3") (pin "12") (pinfunction "Q2_12") (pintype "unspecified+no_connect"))
    )
    (net (code "175") (name "unconnected-(U3-Q3-Pad11)") (class "Default")
      (node (ref "U3") (pin "11") (pinfunction "Q3_11") (pintype "unspecified+no_connect"))
    )
    (net (code "176") (name "unconnected-(U4-2A-Pad4)") (class "Default")
      (node (ref "U4") (pin "4") (pinfunction "2A_4") (pintype "unspecified+no_connect"))
    )
    (net (code "177") (name "unconnected-(U4-2B-Pad5)") (class "Default")
      (node (ref "U4") (pin "5") (pinfunction "2B_5") (pintype "unspecified+no_connect"))
    )
    (net (code "178") (name "unconnected-(U4-2Y-Pad6)") (class "Default")
      (node (ref "U4") (pin "6") (pinfunction "2Y_6") (pintype "unspecified+no_connect"))
    )
    (net (code "179") (name "unconnected-(U4-3A-Pad9)") (class "Default")
      (node (ref "U4") (pin "9") (pinfunction "3A_9") (pintype "unspecified+no_connect"))
    )
    (net (code "180") (name "unconnected-(U4-3B-Pad10)") (class "Default")
      (node (ref "U4") (pin "10") (pinfunction "3B_10") (pintype "unspecified+no_connect"))
    )
    (net (code "181") (name "unconnected-(U4-3Y-Pad8)") (class "Default")
      (node (ref "U4") (pin "8") (pinfunction "3Y_8") (pintype "unspecified+no_connect"))
    )
    (net (code "182") (name "unconnected-(U4-4A-Pad12)") (class "Default")
      (node (ref "U4") (pin "12") (pinfunction "4A_12") (pintype "unspecified+no_connect"))
    )
    (net (code "183") (name "unconnected-(U4-4B-Pad13)") (class "Default")
      (node (ref "U4") (pin "13") (pinfunction "4B_13") (pintype "unspecified+no_connect"))
    )
    (net (code "184") (name "unconnected-(U4-4Y-Pad11)") (class "Default")
      (node (ref "U4") (pin "11") (pinfunction "4Y_11") (pintype "unspecified+no_connect"))
    )
    (net (code "185") (name "unconnected-(U5-1Q#-Pad6)") (class "Default")
      (node (ref "U5") (pin "6") (pinfunction "1Q#_6") (pintype "unspecified+no_connect"))
    )
    (net (code "186") (name "unconnected-(U6-OUT2-Pad2)") (class "Default")
      (node (ref "U6") (pin "2") (pinfunction "OUT2_2") (pintype "unspecified+no_connect"))
    )
    (net (code "187") (name "unconnected-(U9-3V-Pad1)") (class "Default")
      (node (ref "U9") (pin "1") (pinfunction "3V_1") (pintype "unspecified+no_connect"))
    )
    (net (code "188") (name "unconnected-(U9-C8-Pad20)") (class "Default")
      (node (ref "U9") (pin "20") (pinfunction "C8_20") (pintype "unspecified+no_connect"))
    )
    (net (code "189") (name "unconnected-(U9-C9-Pad21)") (class "Default")
      (node (ref "U9") (pin "21") (pinfunction "C9_21") (pintype "unspecified+no_connect"))
    )
    (net (code "190") (name "unconnected-(U9-D0-Pad4)") (class "Default")
      (node (ref "U9") (pin "4") (pinfunction "D0_4") (pintype "unspecified+no_connect"))
    )
    (net (code "191") (name "unconnected-(U9-D1-Pad5)") (class "Default")
      (node (ref "U9") (pin "5") (pinfunction "D1_5") (pintype "unspecified+no_connect"))
    )
    (net (code "192") (name "unconnected-(U9-D2-Pad6)") (class "Default")
      (node (ref "U9") (pin "6") (pinfunction "D2_6") (pintype "unspecified+no_connect"))
    )
    (net (code "193") (name "unconnected-(U9-D3-Pad7)") (class "Default")
      (node (ref "U9") (pin "7") (pinfunction "D3_7") (pintype "unspecified+no_connect"))
    )
    (net (code "194") (name "unconnected-(U13-TC-Pad15)") (class "Default")
      (node (ref "U13") (pin "15") (pinfunction "TC_15") (pintype "unspecified+no_connect"))
    )
    (net (code "195") (name "unconnected-(U14-2I0-Pad10)") (class "Default")
      (node (ref "U14") (pin "10") (pinfunction "2I0_10") (pintype "unspecified+no_connect"))
    )
    (net (code "196") (name "unconnected-(U14-2I1-Pad11)") (class "Default")
      (node (ref "U14") (pin "11") (pinfunction "2I1_11") (pintype "unspecified+no_connect"))
    )
    (net (code "197") (name "unconnected-(U14-2I2-Pad12)") (class "Default")
      (node (ref "U14") (pin "12") (pinfunction "2I2_12") (pintype "unspecified+no_connect"))
    )
    (net (code "198") (name "unconnected-(U14-2I3-Pad13)") (class "Default")
      (node (ref "U14") (pin "13") (pinfunction "2I3_13") (pintype "unspecified+no_connect"))
    )
    (net (code "199") (name "unconnected-(U14-2Y-Pad9)") (class "Default")
      (node (ref "U14") (pin "9") (pinfunction "2Y_9") (pintype "unspecified+no_connect"))
    )
    (net (code "200") (name "unconnected-(U16-4A-Pad12)") (class "Default")
      (node (ref "U16") (pin "12") (pinfunction "4A_12") (pintype "unspecified+no_connect"))
    )
    (net (code "201") (name "unconnected-(U16-4B-Pad13)") (class "Default")
      (node (ref "U16") (pin "13") (pinfunction "4B_13") (pintype "unspecified+no_connect"))
    )
    (net (code "202") (name "unconnected-(U16-4Y-Pad11)") (class "Default")
      (node (ref "U16") (pin "11") (pinfunction "4Y_11") (pintype "unspecified+no_connect"))
    )
    (net (code "203") (name "unconnected-(U17-OUT2-Pad2)") (class "Default")
      (node (ref "U17") (pin "2") (pinfunction "OUT2_2") (pintype "unspecified+no_connect"))
    )
    (net (code "204") (name "unconnected-(U18-2I0-Pad10)") (class "Default")
      (node (ref "U18") (pin "10") (pinfunction "2I0_10") (pintype "unspecified+no_connect"))
    )
    (net (code "205") (name "unconnected-(U18-2I1-Pad11)") (class "Default")
      (node (ref "U18") (pin "11") (pinfunction "2I1_11") (pintype "unspecified+no_connect"))
    )
    (net (code "206") (name "unconnected-(U18-2I2-Pad12)") (class "Default")
      (node (ref "U18") (pin "12") (pinfunction "2I2_12") (pintype "unspecified+no_connect"))
    )
    (net (code "207") (name "unconnected-(U18-2I3-Pad13)") (class "Default")
      (node (ref "U18") (pin "13") (pinfunction "2I3_13") (pintype "unspecified+no_connect"))
    )
    (net (code "208") (name "unconnected-(U18-2Y-Pad9)") (class "Default")
      (node (ref "U18") (pin "9") (pinfunction "2Y_9") (pintype "unspecified+no_connect"))
    )
    (net (code "209") (name "unconnected-(U19-C0-Pad5)") (class "Default")
      (node (ref "U19") (pin "5") (pinfunction "C0_5") (pintype "unspecified+no_connect"))
    )
    (net (code "210") (name "unconnected-(U19-C1-Pad3)") (class "Default")
      (node (ref "U19") (pin "3") (pinfunction "C1_3") (pintype "unspecified+no_connect"))
    )
    (net (code "211") (name "unconnected-(U19-CN-Pad4)") (class "Default")
      (node (ref "U19") (pin "4") (pinfunction "CN_4") (pintype "unspecified+no_connect"))
    )
    (net (code "212") (name "unconnected-(U19-S1-Pad10)") (class "Default")
      (node (ref "U19") (pin "10") (pinfunction "S1_10") (pintype "unspecified+no_connect"))
    )
    (net (code "213") (name "unconnected-(U22-Q1-Pad4)") (class "Default")
      (node (ref "U22") (pin "4") (pinfunction "Q1_4") (pintype "unspecified+no_connect"))
    )
    (net (code "214") (name "unconnected-(U22-Q3-Pad6)") (class "Default")
      (node (ref "U22") (pin "6") (pinfunction "Q3_6") (pintype "unspecified+no_connect"))
    )
    (net (code "215") (name "unconnected-(U22-Q4-Pad10)") (class "Default")
      (node (ref "U22") (pin "10") (pinfunction "Q4_10") (pintype "unspecified"))
    )
    (net (code "216") (name "unconnected-(U22-Q5-Pad11)") (class "Default")
      (node (ref "U22") (pin "11") (pinfunction "Q5_11") (pintype "unspecified"))
    )
    (net (code "217") (name "unconnected-(U23-2A-Pad4)") (class "Default")
      (node (ref "U23") (pin "4") (pinfunction "2A_4") (pintype "unspecified+no_connect"))
    )
    (net (code "218") (name "unconnected-(U23-2B-Pad5)") (class "Default")
      (node (ref "U23") (pin "5") (pinfunction "2B_5") (pintype "unspecified+no_connect"))
    )
    (net (code "219") (name "unconnected-(U23-2Y-Pad6)") (class "Default")
      (node (ref "U23") (pin "6") (pinfunction "2Y_6") (pintype "unspecified+no_connect"))
    )
    (net (code "220") (name "unconnected-(U23-3A-Pad9)") (class "Default")
      (node (ref "U23") (pin "9") (pinfunction "3A_9") (pintype "unspecified+no_connect"))
    )
    (net (code "221") (name "unconnected-(U23-3B-Pad10)") (class "Default")
      (node (ref "U23") (pin "10") (pinfunction "3B_10") (pintype "unspecified+no_connect"))
    )
    (net (code "222") (name "unconnected-(U23-3Y-Pad8)") (class "Default")
      (node (ref "U23") (pin "8") (pinfunction "3Y_8") (pintype "unspecified+no_connect"))
    )
    (net (code "223") (name "unconnected-(U23-4A-Pad12)") (class "Default")
      (node (ref "U23") (pin "12") (pinfunction "4A_12") (pintype "unspecified+no_connect"))
    )
    (net (code "224") (name "unconnected-(U23-4B-Pad13)") (class "Default")
      (node (ref "U23") (pin "13") (pinfunction "4B_13") (pintype "unspecified+no_connect"))
    )
    (net (code "225") (name "unconnected-(U23-4Y-Pad11)") (class "Default")
      (node (ref "U23") (pin "11") (pinfunction "4Y_11") (pintype "unspecified+no_connect"))
    )
    (net (code "226") (name "unconnected-(U24-Q0-Pad14)") (class "Default")
      (node (ref "U24") (pin "14") (pinfunction "Q0_14") (pintype "unspecified+no_connect"))
    )
    (net (code "227") (name "unconnected-(U24-Q1-Pad13)") (class "Default")
      (node (ref "U24") (pin "13") (pinfunction "Q1_13") (pintype "unspecified+no_connect"))
    )
    (net (code "228") (name "unconnected-(U24-Q2-Pad12)") (class "Default")
      (node (ref "U24") (pin "12") (pinfunction "Q2_12") (pintype "unspecified+no_connect"))
    )
    (net (code "229") (name "unconnected-(U24-Q3-Pad11)") (class "Default")
      (node (ref "U24") (pin "11") (pinfunction "Q3_11") (pintype "unspecified+no_connect"))
    )
    (net (code "230") (name "unconnected-(U25-1Q#-Pad6)") (class "Default")
      (node (ref "U25") (pin "6") (pinfunction "1Q#_6") (pintype "unspecified+no_connect"))
    )
    (net (code "231") (name "unconnected-(U28-OUT2-Pad2)") (class "Default")
      (node (ref "U28") (pin "2") (pinfunction "OUT2_2") (pintype "unspecified+no_connect"))
    )
    (net (code "232") (name "unconnected-(U29-VCC-Pad14)") (class "Default")
      (node (ref "U29") (pin "14") (pinfunction "VCC_14") (pintype "unspecified"))
    )
    (net (code "233") (name "unconnected-(U30-OUT2-Pad2)") (class "Default")
      (node (ref "U30") (pin "2") (pinfunction "OUT2_2") (pintype "unspecified+no_connect"))
    )
    (net (code "234") (name "unconnected-(U31-G-Pad12)") (class "Default")
      (node (ref "U31") (pin "12") (pinfunction "G_12") (pintype "unspecified+no_connect"))
    )
    (net (code "235") (name "unconnected-(U31-H-Pad13)") (class "Default")
      (node (ref "U31") (pin "13") (pinfunction "H_13") (pintype "unspecified+no_connect"))
    )
    (net (code "236") (name "unconnected-(U31-M=G⊕H-Pad11)") (class "Default")
      (node (ref "U31") (pin "11") (pinfunction "M=G⊕H_11") (pintype "unspecified+no_connect"))
    )
    (net (code "237") (name "unconnected-(U32-3A-Pad5)") (class "Default")
      (node (ref "U32") (pin "5") (pinfunction "3A_5") (pintype "unspecified+no_connect"))
    )
    (net (code "238") (name "unconnected-(U32-3Y#-Pad6)") (class "Default")
      (node (ref "U32") (pin "6") (pinfunction "3Y#_6") (pintype "unspecified+no_connect"))
    )
    (net (code "239") (name "unconnected-(U32-4A-Pad9)") (class "Default")
      (node (ref "U32") (pin "9") (pinfunction "4A_9") (pintype "unspecified+no_connect"))
    )
    (net (code "240") (name "unconnected-(U32-4Y#-Pad8)") (class "Default")
      (node (ref "U32") (pin "8") (pinfunction "4Y#_8") (pintype "unspecified+no_connect"))
    )
    (net (code "241") (name "unconnected-(U32-5A-Pad11)") (class "Default")
      (node (ref "U32") (pin "11") (pinfunction "5A_11") (pintype "unspecified+no_connect"))
    )
    (net (code "242") (name "unconnected-(U32-5Y#-Pad10)") (class "Default")
      (node (ref "U32") (pin "10") (pinfunction "5Y#_10") (pintype "unspecified+no_connect"))
    )
    (net (code "243") (name "unconnected-(U32-6A-Pad13)") (class "Default")
      (node (ref "U32") (pin "13") (pinfunction "6A_13") (pintype "unspecified+no_connect"))
    )
    (net (code "244") (name "unconnected-(U32-6Y#-Pad12)") (class "Default")
      (node (ref "U32") (pin "12") (pinfunction "6Y#_12") (pintype "unspecified+no_connect"))
    )
    (net (code "245") (name "unconnected-(U45-Q0-Pad14)") (class "Default")
      (node (ref "U45") (pin "14") (pinfunction "Q0_14") (pintype "unspecified+no_connect"))
    )
    (net (code "246") (name "unconnected-(U45-Q1-Pad13)") (class "Default")
      (node (ref "U45") (pin "13") (pinfunction "Q1_13") (pintype "unspecified+no_connect"))
    )
    (net (code "247") (name "unconnected-(U45-Q2-Pad12)") (class "Default")
      (node (ref "U45") (pin "12") (pinfunction "Q2_12") (pintype "unspecified+no_connect"))
    )
    (net (code "248") (name "unconnected-(U45-Q3-Pad11)") (class "Default")
      (node (ref "U45") (pin "11") (pinfunction "Q3_11") (pintype "unspecified+no_connect"))
    )
    (net (code "249") (name "unconnected-(U46-Q0-Pad14)") (class "Default")
      (node (ref "U46") (pin "14") (pinfunction "Q0_14") (pintype "unspecified+no_connect"))
    )
    (net (code "250") (name "unconnected-(U46-Q1-Pad13)") (class "Default")
      (node (ref "U46") (pin "13") (pinfunction "Q1_13") (pintype "unspecified+no_connect"))
    )
    (net (code "251") (name "unconnected-(U46-Q2-Pad12)") (class "Default")
      (node (ref "U46") (pin "12") (pinfunction "Q2_12") (pintype "unspecified+no_connect"))
    )
    (net (code "252") (name "unconnected-(U46-Q3-Pad11)") (class "Default")
      (node (ref "U46") (pin "11") (pinfunction "Q3_11") (pintype "unspecified+no_connect"))
    )
    (net (code "253") (name "unconnected-(U47-Q0-Pad14)") (class "Default")
      (node (ref "U47") (pin "14") (pinfunction "Q0_14") (pintype "unspecified+no_connect"))
    )
    (net (code "254") (name "unconnected-(U47-Q1-Pad13)") (class "Default")
      (node (ref "U47") (pin "13") (pinfunction "Q1_13") (pintype "unspecified+no_connect"))
    )
    (net (code "255") (name "unconnected-(U47-Q2-Pad12)") (class "Default")
      (node (ref "U47") (pin "12") (pinfunction "Q2_12") (pintype "unspecified+no_connect"))
    )
    (net (code "256") (name "unconnected-(U47-Q3-Pad11)") (class "Default")
      (node (ref "U47") (pin "11") (pinfunction "Q3_11") (pintype "unspecified+no_connect"))
    )
    (net (code "257") (name "unconnected-(U48-2A-Pad4)") (class "Default")
      (node (ref "U48") (pin "4") (pinfunction "2A_4") (pintype "unspecified+no_connect"))
    )
    (net (code "258") (name "unconnected-(U48-2B-Pad5)") (class "Default")
      (node (ref "U48") (pin "5") (pinfunction "2B_5") (pintype "unspecified+no_connect"))
    )
    (net (code "259") (name "unconnected-(U48-2Y-Pad6)") (class "Default")
      (node (ref "U48") (pin "6") (pinfunction "2Y_6") (pintype "unspecified+no_connect"))
    )
    (net (code "260") (name "unconnected-(U48-3A-Pad9)") (class "Default")
      (node (ref "U48") (pin "9") (pinfunction "3A_9") (pintype "unspecified+no_connect"))
    )
    (net (code "261") (name "unconnected-(U48-3B-Pad10)") (class "Default")
      (node (ref "U48") (pin "10") (pinfunction "3B_10") (pintype "unspecified+no_connect"))
    )
    (net (code "262") (name "unconnected-(U48-3Y-Pad8)") (class "Default")
      (node (ref "U48") (pin "8") (pinfunction "3Y_8") (pintype "unspecified+no_connect"))
    )
    (net (code "263") (name "unconnected-(U48-4A-Pad12)") (class "Default")
      (node (ref "U48") (pin "12") (pinfunction "4A_12") (pintype "unspecified+no_connect"))
    )
    (net (code "264") (name "unconnected-(U48-4B-Pad13)") (class "Default")
      (node (ref "U48") (pin "13") (pinfunction "4B_13") (pintype "unspecified+no_connect"))
    )
    (net (code "265") (name "unconnected-(U48-4Y-Pad11)") (class "Default")
      (node (ref "U48") (pin "11") (pinfunction "4Y_11") (pintype "unspecified+no_connect"))
    )
    (net (code "266") (name "unconnected-(U49-Q0-Pad14)") (class "Default")
      (node (ref "U49") (pin "14") (pinfunction "Q0_14") (pintype "unspecified+no_connect"))
    )
    (net (code "267") (name "unconnected-(U49-Q1-Pad13)") (class "Default")
      (node (ref "U49") (pin "13") (pinfunction "Q1_13") (pintype "unspecified+no_connect"))
    )
    (net (code "268") (name "unconnected-(U49-Q2-Pad12)") (class "Default")
      (node (ref "U49") (pin "12") (pinfunction "Q2_12") (pintype "unspecified+no_connect"))
    )
    (net (code "269") (name "unconnected-(U49-Q3-Pad11)") (class "Default")
      (node (ref "U49") (pin "11") (pinfunction "Q3_11") (pintype "unspecified+no_connect"))
    )
    (net (code "270") (name "unconnected-(U50-Q0-Pad14)") (class "Default")
      (node (ref "U50") (pin "14") (pinfunction "Q0_14") (pintype "unspecified+no_connect"))
    )
    (net (code "271") (name "unconnected-(U50-Q1-Pad13)") (class "Default")
      (node (ref "U50") (pin "13") (pinfunction "Q1_13") (pintype "unspecified+no_connect"))
    )
    (net (code "272") (name "unconnected-(U50-Q2-Pad12)") (class "Default")
      (node (ref "U50") (pin "12") (pinfunction "Q2_12") (pintype "unspecified+no_connect"))
    )
    (net (code "273") (name "unconnected-(U50-Q3-Pad11)") (class "Default")
      (node (ref "U50") (pin "11") (pinfunction "Q3_11") (pintype "unspecified+no_connect"))
    )
    (net (code "274") (name "unconnected-(U54-TC-Pad15)") (class "Default")
      (node (ref "U54") (pin "15") (pinfunction "TC_15") (pintype "unspecified+no_connect"))
    )
    (net (code "275") (name "unconnected-(U57-OUT2-Pad2)") (class "Default")
      (node (ref "U57") (pin "2") (pinfunction "OUT2_2") (pintype "unspecified+no_connect"))
    )
    (net (code "276") (name "unconnected-(U58-OUT2-Pad2)") (class "Default")
      (node (ref "U58") (pin "2") (pinfunction "OUT2_2") (pintype "unspecified+no_connect"))
    )
    (net (code "277") (name "unconnected-(U61-OUT2-Pad2)") (class "Default")
      (node (ref "U61") (pin "2") (pinfunction "OUT2_2") (pintype "unspecified+no_connect"))
    )
    (net (code "278") (name "unconnected-(U62-Q4-Pad12)") (class "Default")
      (node (ref "U62") (pin "12") (pinfunction "Q4_12") (pintype "unspecified+no_connect"))
    )
    (net (code "279") (name "unconnected-(U62-Q5-Pad15)") (class "Default")
      (node (ref "U62") (pin "15") (pinfunction "Q5_15") (pintype "unspecified+no_connect"))
    )
    (net (code "280") (name "unconnected-(U64-OUT2-Pad2)") (class "Default")
      (node (ref "U64") (pin "2") (pinfunction "OUT2_2") (pintype "unspecified+no_connect"))
    )
    (net (code "281") (name "unconnected-(U65-OUT2-Pad2)") (class "Default")
      (node (ref "U65") (pin "2") (pinfunction "OUT2_2") (pintype "unspecified+no_connect"))
    )
    (net (code "282") (name "unconnected-(U71-Q0-Pad14)") (class "Default")
      (node (ref "U71") (pin "14") (pinfunction "Q0_14") (pintype "unspecified+no_connect"))
    )
    (net (code "283") (name "unconnected-(U71-Q1-Pad13)") (class "Default")
      (node (ref "U71") (pin "13") (pinfunction "Q1_13") (pintype "unspecified+no_connect"))
    )
    (net (code "284") (name "unconnected-(U71-Q2-Pad12)") (class "Default")
      (node (ref "U71") (pin "12") (pinfunction "Q2_12") (pintype "unspecified+no_connect"))
    )
    (net (code "285") (name "unconnected-(U71-Q3-Pad11)") (class "Default")
      (node (ref "U71") (pin "11") (pinfunction "Q3_11") (pintype "unspecified+no_connect"))
    )
    (net (code "286") (name "unconnected-(U72-Q0-Pad14)") (class "Default")
      (node (ref "U72") (pin "14") (pinfunction "Q0_14") (pintype "unspecified+no_connect"))
    )
    (net (code "287") (name "unconnected-(U72-Q1-Pad13)") (class "Default")
      (node (ref "U72") (pin "13") (pinfunction "Q1_13") (pintype "unspecified+no_connect"))
    )
    (net (code "288") (name "unconnected-(U72-Q2-Pad12)") (class "Default")
      (node (ref "U72") (pin "12") (pinfunction "Q2_12") (pintype "unspecified+no_connect"))
    )
    (net (code "289") (name "unconnected-(U72-Q3-Pad11)") (class "Default")
      (node (ref "U72") (pin "11") (pinfunction "Q3_11") (pintype "unspecified+no_connect"))
    )
    (net (code "290") (name "unconnected-(U73-Q0-Pad14)") (class "Default")
      (node (ref "U73") (pin "14") (pinfunction "Q0_14") (pintype "unspecified+no_connect"))
    )
    (net (code "291") (name "unconnected-(U73-Q1-Pad13)") (class "Default")
      (node (ref "U73") (pin "13") (pinfunction "Q1_13") (pintype "unspecified+no_connect"))
    )
    (net (code "292") (name "unconnected-(U73-Q2-Pad12)") (class "Default")
      (node (ref "U73") (pin "12") (pinfunction "Q2_12") (pintype "unspecified+no_connect"))
    )
    (net (code "293") (name "unconnected-(U73-Q3-Pad11)") (class "Default")
      (node (ref "U73") (pin "11") (pinfunction "Q3_11") (pintype "unspecified+no_connect"))
    )
    (net (code "294") (name "unconnected-(U74-2A-Pad4)") (class "Default")
      (node (ref "U74") (pin "4") (pinfunction "2A_4") (pintype "unspecified+no_connect"))
    )
    (net (code "295") (name "unconnected-(U74-2B-Pad5)") (class "Default")
      (node (ref "U74") (pin "5") (pinfunction "2B_5") (pintype "unspecified+no_connect"))
    )
    (net (code "296") (name "unconnected-(U74-2Y-Pad6)") (class "Default")
      (node (ref "U74") (pin "6") (pinfunction "2Y_6") (pintype "unspecified+no_connect"))
    )
    (net (code "297") (name "unconnected-(U74-3A-Pad9)") (class "Default")
      (node (ref "U74") (pin "9") (pinfunction "3A_9") (pintype "unspecified+no_connect"))
    )
    (net (code "298") (name "unconnected-(U74-3B-Pad10)") (class "Default")
      (node (ref "U74") (pin "10") (pinfunction "3B_10") (pintype "unspecified+no_connect"))
    )
    (net (code "299") (name "unconnected-(U74-3Y-Pad8)") (class "Default")
      (node (ref "U74") (pin "8") (pinfunction "3Y_8") (pintype "unspecified+no_connect"))
    )
    (net (code "300") (name "unconnected-(U74-4A-Pad12)") (class "Default")
      (node (ref "U74") (pin "12") (pinfunction "4A_12") (pintype "unspecified+no_connect"))
    )
    (net (code "301") (name "unconnected-(U74-4B-Pad13)") (class "Default")
      (node (ref "U74") (pin "13") (pinfunction "4B_13") (pintype "unspecified+no_connect"))
    )
    (net (code "302") (name "unconnected-(U74-4Y-Pad11)") (class "Default")
      (node (ref "U74") (pin "11") (pinfunction "4Y_11") (pintype "unspecified+no_connect"))
    )
    (net (code "303") (name "unconnected-(U77-2CLK-Pad11)") (class "Default")
      (node (ref "U77") (pin "11") (pinfunction "2CLK_11") (pintype "unspecified+no_connect"))
    )
    (net (code "304") (name "unconnected-(U77-2CLR#-Pad13)") (class "Default")
      (node (ref "U77") (pin "13") (pinfunction "2CLR#_13") (pintype "unspecified+no_connect"))
    )
    (net (code "305") (name "unconnected-(U77-2D-Pad12)") (class "Default")
      (node (ref "U77") (pin "12") (pinfunction "2D_12") (pintype "unspecified+no_connect"))
    )
    (net (code "306") (name "unconnected-(U77-2PRE#-Pad10)") (class "Default")
      (node (ref "U77") (pin "10") (pinfunction "2PRE#_10") (pintype "unspecified+no_connect"))
    )
    (net (code "307") (name "unconnected-(U77-2Q#-Pad8)") (class "Default")
      (node (ref "U77") (pin "8") (pinfunction "2Q#_8") (pintype "unspecified+no_connect"))
    )
    (net (code "308") (name "unconnected-(U77-2Q-Pad9)") (class "Default")
      (node (ref "U77") (pin "9") (pinfunction "2Q_9") (pintype "unspecified+no_connect"))
    )
    (net (code "309") (name "unconnected-(U78-3A-Pad5)") (class "Default")
      (node (ref "U78") (pin "5") (pinfunction "3A_5") (pintype "unspecified+no_connect"))
    )
    (net (code "310") (name "unconnected-(U78-3Y-Pad6)") (class "Default")
      (node (ref "U78") (pin "6") (pinfunction "3Y_6") (pintype "unspecified+no_connect"))
    )
    (net (code "311") (name "unconnected-(U78-4A-Pad9)") (class "Default")
      (node (ref "U78") (pin "9") (pinfunction "4A_9") (pintype "unspecified+no_connect"))
    )
    (net (code "312") (name "unconnected-(U78-4Y-Pad8)") (class "Default")
      (node (ref "U78") (pin "8") (pinfunction "4Y_8") (pintype "unspecified+no_connect"))
    )
    (net (code "313") (name "unconnected-(U78-5A-Pad11)") (class "Default")
      (node (ref "U78") (pin "11") (pinfunction "5A_11") (pintype "unspecified+no_connect"))
    )
    (net (code "314") (name "unconnected-(U78-5Y-Pad10)") (class "Default")
      (node (ref "U78") (pin "10") (pinfunction "5Y_10") (pintype "unspecified+no_connect"))
    )
    (net (code "315") (name "unconnected-(U78-6A-Pad13)") (class "Default")
      (node (ref "U78") (pin "13") (pinfunction "6A_13") (pintype "unspecified+no_connect"))
    )
    (net (code "316") (name "unconnected-(U78-6Y-Pad12)") (class "Default")
      (node (ref "U78") (pin "12") (pinfunction "6Y_12") (pintype "unspecified+no_connect"))
    )
    (net (code "317") (name "unconnected-(X1-NC-Pad1)") (class "Default")
      (node (ref "X1") (pin "1") (pinfunction "NC_1") (pintype "unspecified+no_connect"))
    )
    (net (code "318") (name "unconnected-(X1-X-Pad2)") (class "Default")
      (node (ref "X1") (pin "2") (pinfunction "X_2") (pintype "unspecified+no_connect"))
    )
    (net (code "319") (name "unconnected-(X1-X-Pad3)") (class "Default")
      (node (ref "X1") (pin "3") (pinfunction "X_3") (pintype "unspecified+no_connect"))
    )
    (net (code "320") (name "unconnected-(X1-X-Pad5)") (class "Default")
      (node (ref "X1") (pin "5") (pinfunction "X_5") (pintype "unspecified+no_connect"))
    )
    (net (code "321") (name "unconnected-(X1-X-Pad6)") (class "Default")
      (node (ref "X1") (pin "6") (pinfunction "X_6") (pintype "unspecified+no_connect"))
    )
    (net (code "322") (name "unconnected-(X1-X-Pad9)") (class "Default")
      (node (ref "X1") (pin "9") (pinfunction "X_9") (pintype "unspecified+no_connect"))
    )
    (net (code "323") (name "unconnected-(X1-X-Pad10)") (class "Default")
      (node (ref "X1") (pin "10") (pinfunction "X_10") (pintype "unspecified+no_connect"))
    )
    (net (code "324") (name "unconnected-(X1-X-Pad12)") (class "Default")
      (node (ref "X1") (pin "12") (pinfunction "X_12") (pintype "unspecified+no_connect"))
    )
    (net (code "325") (name "unconnected-(X1-X-Pad13)") (class "Default")
      (node (ref "X1") (pin "13") (pinfunction "X_13") (pintype "unspecified+no_connect"))
    )
    (net (code "326") (name "unconnected-(X2-NC-Pad1)") (class "Default")
      (node (ref "X2") (pin "1") (pinfunction "NC_1") (pintype "unspecified+no_connect"))
    )
    (net (code "327") (name "unconnected-(X2-X-Pad2)") (class "Default")
      (node (ref "X2") (pin "2") (pinfunction "X_2") (pintype "unspecified+no_connect"))
    )
    (net (code "328") (name "unconnected-(X2-X-Pad3)") (class "Default")
      (node (ref "X2") (pin "3") (pinfunction "X_3") (pintype "unspecified+no_connect"))
    )
    (net (code "329") (name "unconnected-(X2-X-Pad5)") (class "Default")
      (node (ref "X2") (pin "5") (pinfunction "X_5") (pintype "unspecified+no_connect"))
    )
    (net (code "330") (name "unconnected-(X2-X-Pad6)") (class "Default")
      (node (ref "X2") (pin "6") (pinfunction "X_6") (pintype "unspecified+no_connect"))
    )
    (net (code "331") (name "unconnected-(X2-X-Pad9)") (class "Default")
      (node (ref "X2") (pin "9") (pinfunction "X_9") (pintype "unspecified+no_connect"))
    )
    (net (code "332") (name "unconnected-(X2-X-Pad10)") (class "Default")
      (node (ref "X2") (pin "10") (pinfunction "X_10") (pintype "unspecified+no_connect"))
    )
    (net (code "333") (name "unconnected-(X2-X-Pad12)") (class "Default")
      (node (ref "X2") (pin "12") (pinfunction "X_12") (pintype "unspecified+no_connect"))
    )
    (net (code "334") (name "unconnected-(X2-X-Pad13)") (class "Default")
      (node (ref "X2") (pin "13") (pinfunction "X_13") (pintype "unspecified+no_connect"))
    )
    (net (code "335") (name "unconnected-(X3-NC-Pad1)") (class "Default")
      (node (ref "X3") (pin "1") (pinfunction "NC_1") (pintype "unspecified+no_connect"))
    )
    (net (code "336") (name "unconnected-(X3-X-Pad2)") (class "Default")
      (node (ref "X3") (pin "2") (pinfunction "X_2") (pintype "unspecified+no_connect"))
    )
    (net (code "337") (name "unconnected-(X3-X-Pad3)") (class "Default")
      (node (ref "X3") (pin "3") (pinfunction "X_3") (pintype "unspecified+no_connect"))
    )
    (net (code "338") (name "unconnected-(X3-X-Pad5)") (class "Default")
      (node (ref "X3") (pin "5") (pinfunction "X_5") (pintype "unspecified+no_connect"))
    )
    (net (code "339") (name "unconnected-(X3-X-Pad6)") (class "Default")
      (node (ref "X3") (pin "6") (pinfunction "X_6") (pintype "unspecified+no_connect"))
    )
    (net (code "340") (name "unconnected-(X3-X-Pad9)") (class "Default")
      (node (ref "X3") (pin "9") (pinfunction "X_9") (pintype "unspecified+no_connect"))
    )
    (net (code "341") (name "unconnected-(X3-X-Pad10)") (class "Default")
      (node (ref "X3") (pin "10") (pinfunction "X_10") (pintype "unspecified+no_connect"))
    )
    (net (code "342") (name "unconnected-(X3-X-Pad12)") (class "Default")
      (node (ref "X3") (pin "12") (pinfunction "X_12") (pintype "unspecified+no_connect"))
    )
    (net (code "343") (name "unconnected-(X3-X-Pad13)") (class "Default")
      (node (ref "X3") (pin "13") (pinfunction "X_13") (pintype "unspecified+no_connect"))
    )
    (net (code "344") (name "unconnected-(X4-NC-Pad1)") (class "Default")
      (node (ref "X4") (pin "1") (pinfunction "NC_1") (pintype "unspecified+no_connect"))
    )
    (net (code "345") (name "unconnected-(X4-X-Pad2)") (class "Default")
      (node (ref "X4") (pin "2") (pinfunction "X_2") (pintype "unspecified+no_connect"))
    )
    (net (code "346") (name "unconnected-(X4-X-Pad3)") (class "Default")
      (node (ref "X4") (pin "3") (pinfunction "X_3") (pintype "unspecified+no_connect"))
    )
    (net (code "347") (name "unconnected-(X4-X-Pad5)") (class "Default")
      (node (ref "X4") (pin "5") (pinfunction "X_5") (pintype "unspecified+no_connect"))
    )
    (net (code "348") (name "unconnected-(X4-X-Pad6)") (class "Default")
      (node (ref "X4") (pin "6") (pinfunction "X_6") (pintype "unspecified+no_connect"))
    )
    (net (code "349") (name "unconnected-(X4-X-Pad9)") (class "Default")
      (node (ref "X4") (pin "9") (pinfunction "X_9") (pintype "unspecified+no_connect"))
    )
    (net (code "350") (name "unconnected-(X4-X-Pad10)") (class "Default")
      (node (ref "X4") (pin "10") (pinfunction "X_10") (pintype "unspecified+no_connect"))
    )
    (net (code "351") (name "unconnected-(X4-X-Pad12)") (class "Default")
      (node (ref "X4") (pin "12") (pinfunction "X_12") (pintype "unspecified+no_connect"))
    )
    (net (code "352") (name "unconnected-(X4-X-Pad13)") (class "Default")
      (node (ref "X4") (pin "13") (pinfunction "X_13") (pintype "unspecified+no_connect"))
    )
    (net (code "353") (name "wave-p0") (class "Default")
      (node (ref "U40") (pin "2") (pinfunction "Q0_2") (pintype "unspecified"))
      (node (ref "U44") (pin "2") (pinfunction "Q0_2") (pintype "unspecified"))
      (node (ref "U46") (pin "3") (pinfunction "P0_3") (pintype "unspecified"))
      (node (ref "U49") (pin "3") (pinfunction "P0_3") (pintype "unspecified"))
      (node (ref "U51") (pin "2") (pinfunction "Q0_2") (pintype "unspecified"))
      (node (ref "U70") (pin "2") (pinfunction "Q0_2") (pintype "unspecified"))
      (node (ref "U72") (pin "3") (pinfunction "P0_3") (pintype "unspecified"))
    )
    (net (code "354") (name "wave-p1") (class "Default")
      (node (ref "U40") (pin "5") (pinfunction "Q1_5") (pintype "unspecified"))
      (node (ref "U44") (pin "5") (pinfunction "Q1_5") (pintype "unspecified"))
      (node (ref "U46") (pin "4") (pinfunction "P1_4") (pintype "unspecified"))
      (node (ref "U49") (pin "4") (pinfunction "P1_4") (pintype "unspecified"))
      (node (ref "U51") (pin "5") (pinfunction "Q1_5") (pintype "unspecified"))
      (node (ref "U70") (pin "5") (pinfunction "Q1_5") (pintype "unspecified"))
      (node (ref "U72") (pin "4") (pinfunction "P1_4") (pintype "unspecified"))
    )
    (net (code "355") (name "wave-p2") (class "Default")
      (node (ref "U40") (pin "6") (pinfunction "Q2_6") (pintype "unspecified"))
      (node (ref "U44") (pin "6") (pinfunction "Q2_6") (pintype "unspecified"))
      (node (ref "U46") (pin "5") (pinfunction "P2_5") (pintype "unspecified"))
      (node (ref "U49") (pin "5") (pinfunction "P2_5") (pintype "unspecified"))
      (node (ref "U51") (pin "6") (pinfunction "Q2_6") (pintype "unspecified"))
      (node (ref "U70") (pin "6") (pinfunction "Q2_6") (pintype "unspecified"))
      (node (ref "U72") (pin "5") (pinfunction "P2_5") (pintype "unspecified"))
    )
    (net (code "356") (name "wave-p3") (class "Default")
      (node (ref "U40") (pin "9") (pinfunction "Q3_9") (pintype "unspecified"))
      (node (ref "U44") (pin "9") (pinfunction "Q3_9") (pintype "unspecified"))
      (node (ref "U46") (pin "6") (pinfunction "P3_6") (pintype "unspecified"))
      (node (ref "U49") (pin "6") (pinfunction "P3_6") (pintype "unspecified"))
      (node (ref "U51") (pin "9") (pinfunction "Q3_9") (pintype "unspecified"))
      (node (ref "U70") (pin "9") (pinfunction "Q3_9") (pintype "unspecified"))
      (node (ref "U72") (pin "6") (pinfunction "P3_6") (pintype "unspecified"))
    )
    (net (code "357") (name "wave-p4") (class "Default")
      (node (ref "U40") (pin "12") (pinfunction "Q4_12") (pintype "unspecified"))
      (node (ref "U44") (pin "12") (pinfunction "Q4_12") (pintype "unspecified"))
      (node (ref "U45") (pin "3") (pinfunction "P0_3") (pintype "unspecified"))
      (node (ref "U50") (pin "3") (pinfunction "P0_3") (pintype "unspecified"))
      (node (ref "U51") (pin "12") (pinfunction "Q4_12") (pintype "unspecified"))
      (node (ref "U70") (pin "12") (pinfunction "Q4_12") (pintype "unspecified"))
      (node (ref "U71") (pin "3") (pinfunction "P0_3") (pintype "unspecified"))
    )
    (net (code "358") (name "wave-p5") (class "Default")
      (node (ref "U40") (pin "15") (pinfunction "Q5_15") (pintype "unspecified"))
      (node (ref "U44") (pin "15") (pinfunction "Q5_15") (pintype "unspecified"))
      (node (ref "U45") (pin "4") (pinfunction "P1_4") (pintype "unspecified"))
      (node (ref "U50") (pin "4") (pinfunction "P1_4") (pintype "unspecified"))
      (node (ref "U51") (pin "15") (pinfunction "Q5_15") (pintype "unspecified"))
      (node (ref "U70") (pin "15") (pinfunction "Q5_15") (pintype "unspecified"))
      (node (ref "U71") (pin "4") (pinfunction "P1_4") (pintype "unspecified"))
    )
    (net (code "359") (name "wave-p6") (class "Default")
      (node (ref "U40") (pin "16") (pinfunction "Q6_16") (pintype "unspecified"))
      (node (ref "U44") (pin "16") (pinfunction "Q6_16") (pintype "unspecified"))
      (node (ref "U45") (pin "5") (pinfunction "P2_5") (pintype "unspecified"))
      (node (ref "U50") (pin "5") (pinfunction "P2_5") (pintype "unspecified"))
      (node (ref "U51") (pin "16") (pinfunction "Q6_16") (pintype "unspecified"))
      (node (ref "U70") (pin "16") (pinfunction "Q6_16") (pintype "unspecified"))
      (node (ref "U71") (pin "5") (pinfunction "P2_5") (pintype "unspecified"))
    )
    (net (code "360") (name "wave-p7") (class "Default")
      (node (ref "U40") (pin "19") (pinfunction "Q7_19") (pintype "unspecified"))
      (node (ref "U44") (pin "19") (pinfunction "Q7_19") (pintype "unspecified"))
      (node (ref "U45") (pin "6") (pinfunction "P3_6") (pintype "unspecified"))
      (node (ref "U50") (pin "6") (pinfunction "P3_6") (pintype "unspecified"))
      (node (ref "U51") (pin "19") (pinfunction "Q7_19") (pintype "unspecified"))
      (node (ref "U70") (pin "19") (pinfunction "Q7_19") (pintype "unspecified"))
      (node (ref "U71") (pin "6") (pinfunction "P3_6") (pintype "unspecified"))
    )
    (net (code "361") (name "wave-p8") (class "Default")
      (node (ref "U24") (pin "3") (pinfunction "P0_3") (pintype "unspecified"))
      (node (ref "U41") (pin "12") (pinfunction "Q4_12") (pintype "unspecified"))
      (node (ref "U43") (pin "12") (pinfunction "Q4_12") (pintype "unspecified"))
      (node (ref "U47") (pin "3") (pinfunction "P0_3") (pintype "unspecified"))
      (node (ref "U52") (pin "12") (pinfunction "Q4_12") (pintype "unspecified"))
      (node (ref "U69") (pin "12") (pinfunction "Q4_12") (pintype "unspecified"))
      (node (ref "U73") (pin "3") (pinfunction "P0_3") (pintype "unspecified"))
    )
    (net (code "362") (name "wave-p9") (class "Default")
      (node (ref "U24") (pin "4") (pinfunction "P1_4") (pintype "unspecified"))
      (node (ref "U41") (pin "15") (pinfunction "Q5_15") (pintype "unspecified"))
      (node (ref "U43") (pin "15") (pinfunction "Q5_15") (pintype "unspecified"))
      (node (ref "U47") (pin "4") (pinfunction "P1_4") (pintype "unspecified"))
      (node (ref "U52") (pin "15") (pinfunction "Q5_15") (pintype "unspecified"))
      (node (ref "U69") (pin "15") (pinfunction "Q5_15") (pintype "unspecified"))
      (node (ref "U73") (pin "4") (pinfunction "P1_4") (pintype "unspecified"))
    )
    (net (code "363") (name "wave-p10") (class "Default")
      (node (ref "U24") (pin "5") (pinfunction "P2_5") (pintype "unspecified"))
      (node (ref "U41") (pin "16") (pinfunction "Q6_16") (pintype "unspecified"))
      (node (ref "U43") (pin "16") (pinfunction "Q6_16") (pintype "unspecified"))
      (node (ref "U47") (pin "5") (pinfunction "P2_5") (pintype "unspecified"))
      (node (ref "U52") (pin "16") (pinfunction "Q6_16") (pintype "unspecified"))
      (node (ref "U69") (pin "16") (pinfunction "Q6_16") (pintype "unspecified"))
      (node (ref "U73") (pin "5") (pinfunction "P2_5") (pintype "unspecified"))
    )
    (net (code "364") (name "wave-p11") (class "Default")
      (node (ref "U24") (pin "6") (pinfunction "P3_6") (pintype "unspecified"))
      (node (ref "U41") (pin "19") (pinfunction "Q7_19") (pintype "unspecified"))
      (node (ref "U43") (pin "19") (pinfunction "Q7_19") (pintype "unspecified"))
      (node (ref "U47") (pin "6") (pinfunction "P3_6") (pintype "unspecified"))
      (node (ref "U52") (pin "19") (pinfunction "Q7_19") (pintype "unspecified"))
      (node (ref "U69") (pin "19") (pinfunction "Q7_19") (pintype "unspecified"))
      (node (ref "U73") (pin "6") (pinfunction "P3_6") (pintype "unspecified"))
    )
    (net (code "365") (name "wave-vol0") (class "Default")
      (node (ref "U41") (pin "2") (pinfunction "Q0_2") (pintype "unspecified"))
      (node (ref "U43") (pin "2") (pinfunction "Q0_2") (pintype "unspecified"))
      (node (ref "U52") (pin "2") (pinfunction "Q0_2") (pintype "unspecified"))
      (node (ref "U58") (pin "10") (pinfunction "DB1_10") (pintype "unspecified"))
      (node (ref "U58") (pin "11") (pinfunction "DB0_11") (pintype "unspecified"))
      (node (ref "U58") (pin "7") (pinfunction "DB4_7") (pintype "unspecified"))
      (node (ref "U58") (pin "8") (pinfunction "DB3_8") (pintype "unspecified"))
      (node (ref "U58") (pin "9") (pinfunction "DB2_9") (pintype "unspecified"))
      (node (ref "U61") (pin "10") (pinfunction "DB1_10") (pintype "unspecified"))
      (node (ref "U61") (pin "11") (pinfunction "DB0_11") (pintype "unspecified"))
      (node (ref "U61") (pin "7") (pinfunction "DB4_7") (pintype "unspecified"))
      (node (ref "U61") (pin "8") (pinfunction "DB3_8") (pintype "unspecified"))
      (node (ref "U61") (pin "9") (pinfunction "DB2_9") (pintype "unspecified"))
      (node (ref "U64") (pin "10") (pinfunction "DB1_10") (pintype "unspecified"))
      (node (ref "U64") (pin "11") (pinfunction "DB0_11") (pintype "unspecified"))
      (node (ref "U64") (pin "7") (pinfunction "DB4_7") (pintype "unspecified"))
      (node (ref "U64") (pin "8") (pinfunction "DB3_8") (pintype "unspecified"))
      (node (ref "U64") (pin "9") (pinfunction "DB2_9") (pintype "unspecified"))
      (node (ref "U69") (pin "2") (pinfunction "Q0_2") (pintype "unspecified"))
    )
    (net (code "366") (name "wave-vol1") (class "Default")
      (node (ref "U41") (pin "5") (pinfunction "Q1_5") (pintype "unspecified"))
      (node (ref "U43") (pin "5") (pinfunction "Q1_5") (pintype "unspecified"))
      (node (ref "U52") (pin "5") (pinfunction "Q1_5") (pintype "unspecified"))
      (node (ref "U58") (pin "6") (pinfunction "DB5_6") (pintype "unspecified"))
      (node (ref "U61") (pin "6") (pinfunction "DB5_6") (pintype "unspecified"))
      (node (ref "U64") (pin "6") (pinfunction "DB5_6") (pintype "unspecified"))
      (node (ref "U69") (pin "5") (pinfunction "Q1_5") (pintype "unspecified"))
    )
    (net (code "367") (name "wave-vol2") (class "Default")
      (node (ref "U41") (pin "6") (pinfunction "Q2_6") (pintype "unspecified"))
      (node (ref "U43") (pin "6") (pinfunction "Q2_6") (pintype "unspecified"))
      (node (ref "U52") (pin "6") (pinfunction "Q2_6") (pintype "unspecified"))
      (node (ref "U58") (pin "5") (pinfunction "DB6_5") (pintype "unspecified"))
      (node (ref "U61") (pin "5") (pinfunction "DB6_5") (pintype "unspecified"))
      (node (ref "U64") (pin "5") (pinfunction "DB6_5") (pintype "unspecified"))
      (node (ref "U69") (pin "6") (pinfunction "Q2_6") (pintype "unspecified"))
    )
    (net (code "368") (name "wave-vol3") (class "Default")
      (node (ref "U41") (pin "9") (pinfunction "Q3_9") (pintype "unspecified"))
      (node (ref "U43") (pin "9") (pinfunction "Q3_9") (pintype "unspecified"))
      (node (ref "U52") (pin "9") (pinfunction "Q3_9") (pintype "unspecified"))
      (node (ref "U58") (pin "4") (pinfunction "DB7_4") (pintype "unspecified"))
      (node (ref "U61") (pin "4") (pinfunction "DB7_4") (pintype "unspecified"))
      (node (ref "U64") (pin "4") (pinfunction "DB7_4") (pintype "unspecified"))
      (node (ref "U69") (pin "9") (pinfunction "Q3_9") (pintype "unspecified"))
    )
    (net (code "369") (name "w{slash}2") (class "Default")
      (node (ref "U26") (pin "11") (pinfunction "2CLK_11") (pintype "unspecified"))
      (node (ref "U26") (pin "5") (pinfunction "1Q_5") (pintype "unspecified"))
      (node (ref "U28") (pin "7") (pinfunction "DB4_7") (pintype "unspecified"))
      (node (ref "U29") (pin "4") (pinfunction "2A_4") (pintype "unspecified"))
    )
    (net (code "370") (name "w{slash}4") (class "Default")
      (node (ref "U26") (pin "9") (pinfunction "2Q_9") (pintype "unspecified"))
      (node (ref "U27") (pin "3") (pinfunction "1CLK_3") (pintype "unspecified"))
      (node (ref "U28") (pin "6") (pinfunction "DB5_6") (pintype "unspecified"))
      (node (ref "U29") (pin "9") (pinfunction "3A_9") (pintype "unspecified"))
    )
    (net (code "371") (name "w{slash}8") (class "Default")
      (node (ref "U27") (pin "11") (pinfunction "2CLK_11") (pintype "unspecified"))
      (node (ref "U27") (pin "5") (pinfunction "1Q_5") (pintype "unspecified"))
      (node (ref "U28") (pin "5") (pinfunction "DB6_5") (pintype "unspecified"))
      (node (ref "U29") (pin "12") (pinfunction "4A_12") (pintype "unspecified"))
    )
    (net (code "372") (name "w{slash}16") (class "Default")
      (node (ref "U27") (pin "9") (pinfunction "2Q_9") (pintype "unspecified"))
      (node (ref "U28") (pin "4") (pinfunction "DB7_4") (pintype "unspecified"))
      (node (ref "U29") (pin "10") (pinfunction "3B_10") (pintype "unspecified"))
      (node (ref "U29") (pin "13") (pinfunction "4B_13") (pintype "unspecified"))
      (node (ref "U29") (pin "2") (pinfunction "1B_2") (pintype "unspecified"))
      (node (ref "U29") (pin "5") (pinfunction "2B_5") (pintype "unspecified"))
    )
    (net (code "373") (name "xor_a") (class "Default")
      (node (ref "U31") (pin "3") (pinfunction "J=A⊕B_3") (pintype "unspecified"))
      (node (ref "U31") (pin "8") (pinfunction "E_8") (pintype "unspecified"))
    )
    (net (code "374") (name "xor_b") (class "Default")
      (node (ref "U31") (pin "4") (pinfunction "K=C⊕D_4") (pintype "unspecified"))
      (node (ref "U31") (pin "9") (pinfunction "F_9") (pintype "unspecified"))
    )
    (net (code "375") (name "xor_fb") (class "Default")
      (node (ref "U21") (pin "4") (pinfunction "2A_4") (pintype "unspecified"))
      (node (ref "U21") (pin "5") (pinfunction "2B_5") (pintype "unspecified"))
      (node (ref "U22") (pin "1") (pinfunction "DS1_1") (pintype "unspecified"))
      (node (ref "U31") (pin "10") (pinfunction "L=E⊕F_10") (pintype "unspecified"))
    )
    (net (code "376") (name "{slash}A0") (class "Default")
      (node (ref "U32") (pin "4") (pinfunction "2Y#_4") (pintype "unspecified"))
      (node (ref "U33") (pin "2") (pinfunction "1B_2") (pintype "unspecified"))
    )
    (net (code "377") (name "{slash}CS") (class "Default")
      (node (ref "U1") (pin "9") (pinfunction "4Q_9") (pintype "unspecified"))
      (node (ref "U32") (pin "1") (pinfunction "1A_1") (pintype "unspecified"))
    )
    (net (code "378") (name "{slash}PE") (class "Default")
      (node (ref "U19") (pin "1") (pinfunction "B1_1") (pintype "unspecified"))
      (node (ref "U2") (pin "9") (pinfunction "SPE#_9") (pintype "unspecified"))
      (node (ref "U23") (pin "3") (pinfunction "1Y_3") (pintype "unspecified"))
      (node (ref "U24") (pin "9") (pinfunction "SPE#_9") (pintype "unspecified"))
      (node (ref "U3") (pin "9") (pinfunction "SPE#_9") (pintype "unspecified"))
      (node (ref "U4") (pin "3") (pinfunction "1Y_3") (pintype "unspecified"))
      (node (ref "U45") (pin "9") (pinfunction "SPE#_9") (pintype "unspecified"))
      (node (ref "U46") (pin "9") (pinfunction "SPE#_9") (pintype "unspecified"))
      (node (ref "U47") (pin "9") (pinfunction "SPE#_9") (pintype "unspecified"))
      (node (ref "U48") (pin "3") (pinfunction "1Y_3") (pintype "unspecified"))
      (node (ref "U49") (pin "9") (pinfunction "SPE#_9") (pintype "unspecified"))
      (node (ref "U50") (pin "9") (pinfunction "SPE#_9") (pintype "unspecified"))
      (node (ref "U71") (pin "9") (pinfunction "SPE#_9") (pintype "unspecified"))
      (node (ref "U72") (pin "9") (pinfunction "SPE#_9") (pintype "unspecified"))
      (node (ref "U73") (pin "9") (pinfunction "SPE#_9") (pintype "unspecified"))
      (node (ref "U74") (pin "3") (pinfunction "1Y_3") (pintype "unspecified"))
    )
    (net (code "379") (name "{slash}RC") (class "Default")
      (node (ref "C3") (pin "2") (pinfunction "2_2") (pintype "unspecified"))
      (node (ref "U21") (pin "13") (pinfunction "4B_13") (pintype "unspecified"))
      (node (ref "U21") (pin "8") (pinfunction "3Y_8") (pintype "unspecified"))
    )
    (net (code "380") (name "{slash}RST") (class "Default")
      (node (ref "U1") (pin "6") (pinfunction "3Q_6") (pintype "unspecified"))
      (node (ref "U13") (pin "1") (pinfunction "MR#_1") (pintype "unspecified"))
      (node (ref "U15") (pin "1") (pinfunction "1CLR#_1") (pintype "unspecified"))
      (node (ref "U15") (pin "13") (pinfunction "2CLR#_13") (pintype "unspecified"))
      (node (ref "U2") (pin "1") (pinfunction "MR#_1") (pintype "unspecified"))
      (node (ref "U24") (pin "1") (pinfunction "MR#_1") (pintype "unspecified"))
      (node (ref "U25") (pin "1") (pinfunction "1CLR#_1") (pintype "unspecified"))
      (node (ref "U25") (pin "13") (pinfunction "2CLR#_13") (pintype "unspecified"))
      (node (ref "U26") (pin "1") (pinfunction "1CLR#_1") (pintype "unspecified"))
      (node (ref "U26") (pin "13") (pinfunction "2CLR#_13") (pintype "unspecified"))
      (node (ref "U27") (pin "1") (pinfunction "1CLR#_1") (pintype "unspecified"))
      (node (ref "U27") (pin "13") (pinfunction "2CLR#_13") (pintype "unspecified"))
      (node (ref "U3") (pin "1") (pinfunction "MR#_1") (pintype "unspecified"))
      (node (ref "U45") (pin "1") (pinfunction "MR#_1") (pintype "unspecified"))
      (node (ref "U46") (pin "1") (pinfunction "MR#_1") (pintype "unspecified"))
      (node (ref "U47") (pin "1") (pinfunction "MR#_1") (pintype "unspecified"))
      (node (ref "U49") (pin "1") (pinfunction "MR#_1") (pintype "unspecified"))
      (node (ref "U5") (pin "1") (pinfunction "1CLR#_1") (pintype "unspecified"))
      (node (ref "U5") (pin "13") (pinfunction "2CLR#_13") (pintype "unspecified"))
      (node (ref "U50") (pin "1") (pinfunction "MR#_1") (pintype "unspecified"))
      (node (ref "U54") (pin "1") (pinfunction "MR#_1") (pintype "unspecified"))
      (node (ref "U55") (pin "1") (pinfunction "MR#_1") (pintype "unspecified"))
      (node (ref "U66") (pin "1") (pinfunction "MR#_1") (pintype "unspecified"))
      (node (ref "U67") (pin "1") (pinfunction "MR#_1") (pintype "unspecified"))
      (node (ref "U71") (pin "1") (pinfunction "MR#_1") (pintype "unspecified"))
      (node (ref "U72") (pin "1") (pinfunction "MR#_1") (pintype "unspecified"))
      (node (ref "U73") (pin "1") (pinfunction "MR#_1") (pintype "unspecified"))
      (node (ref "U75") (pin "1") (pinfunction "MR#_1") (pintype "unspecified"))
      (node (ref "U77") (pin "1") (pinfunction "1CLR#_1") (pintype "unspecified"))
    )
    (net (code "381") (name "{slash}WR") (class "Default")
      (node (ref "U1") (pin "5") (pinfunction "2Q_5") (pintype "unspecified"))
      (node (ref "U33") (pin "13") (pinfunction "4B_13") (pintype "unspecified"))
      (node (ref "U33") (pin "5") (pinfunction "2B_5") (pintype "unspecified"))
    )
    (net (code "382") (name "{slash}at8191") (class "Default")
      (node (ref "U78") (pin "4") (pinfunction "2Y_4") (pintype "unspecified"))
    )
    (net (code "383") (name "{slash}at_8191") (class "Default")
      (node (ref "U76") (pin "13") (pinfunction "4B_13") (pintype "unspecified"))
    )
    (net (code "384") (name "{slash}bind") (class "Default")
      (node (ref "U20") (pin "3") (pinfunction "1Y_3") (pintype "unspecified"))
      (node (ref "U20") (pin "4") (pinfunction "2A_4") (pintype "unspecified"))
    )
    (net (code "385") (name "{slash}trig_clr") (class "Default")
      (node (ref "U66") (pin "9") (pinfunction "SPE#_9") (pintype "unspecified"))
      (node (ref "U67") (pin "9") (pinfunction "SPE#_9") (pintype "unspecified"))
      (node (ref "U75") (pin "9") (pinfunction "SPE#_9") (pintype "unspecified"))
      (node (ref "U78") (pin "2") (pinfunction "1Y_2") (pintype "unspecified"))
    )
    (net (code "386") (name "{slash}xor_fb") (class "Default")
      (node (ref "U21") (pin "12") (pinfunction "4A_12") (pintype "unspecified"))
      (node (ref "U21") (pin "6") (pinfunction "2Y_6") (pintype "unspecified"))
    )
  )
)
